# Ascii_of_Main_Board_V1_1.net
KiCad netlist of a schematic drawn in Altium Designer
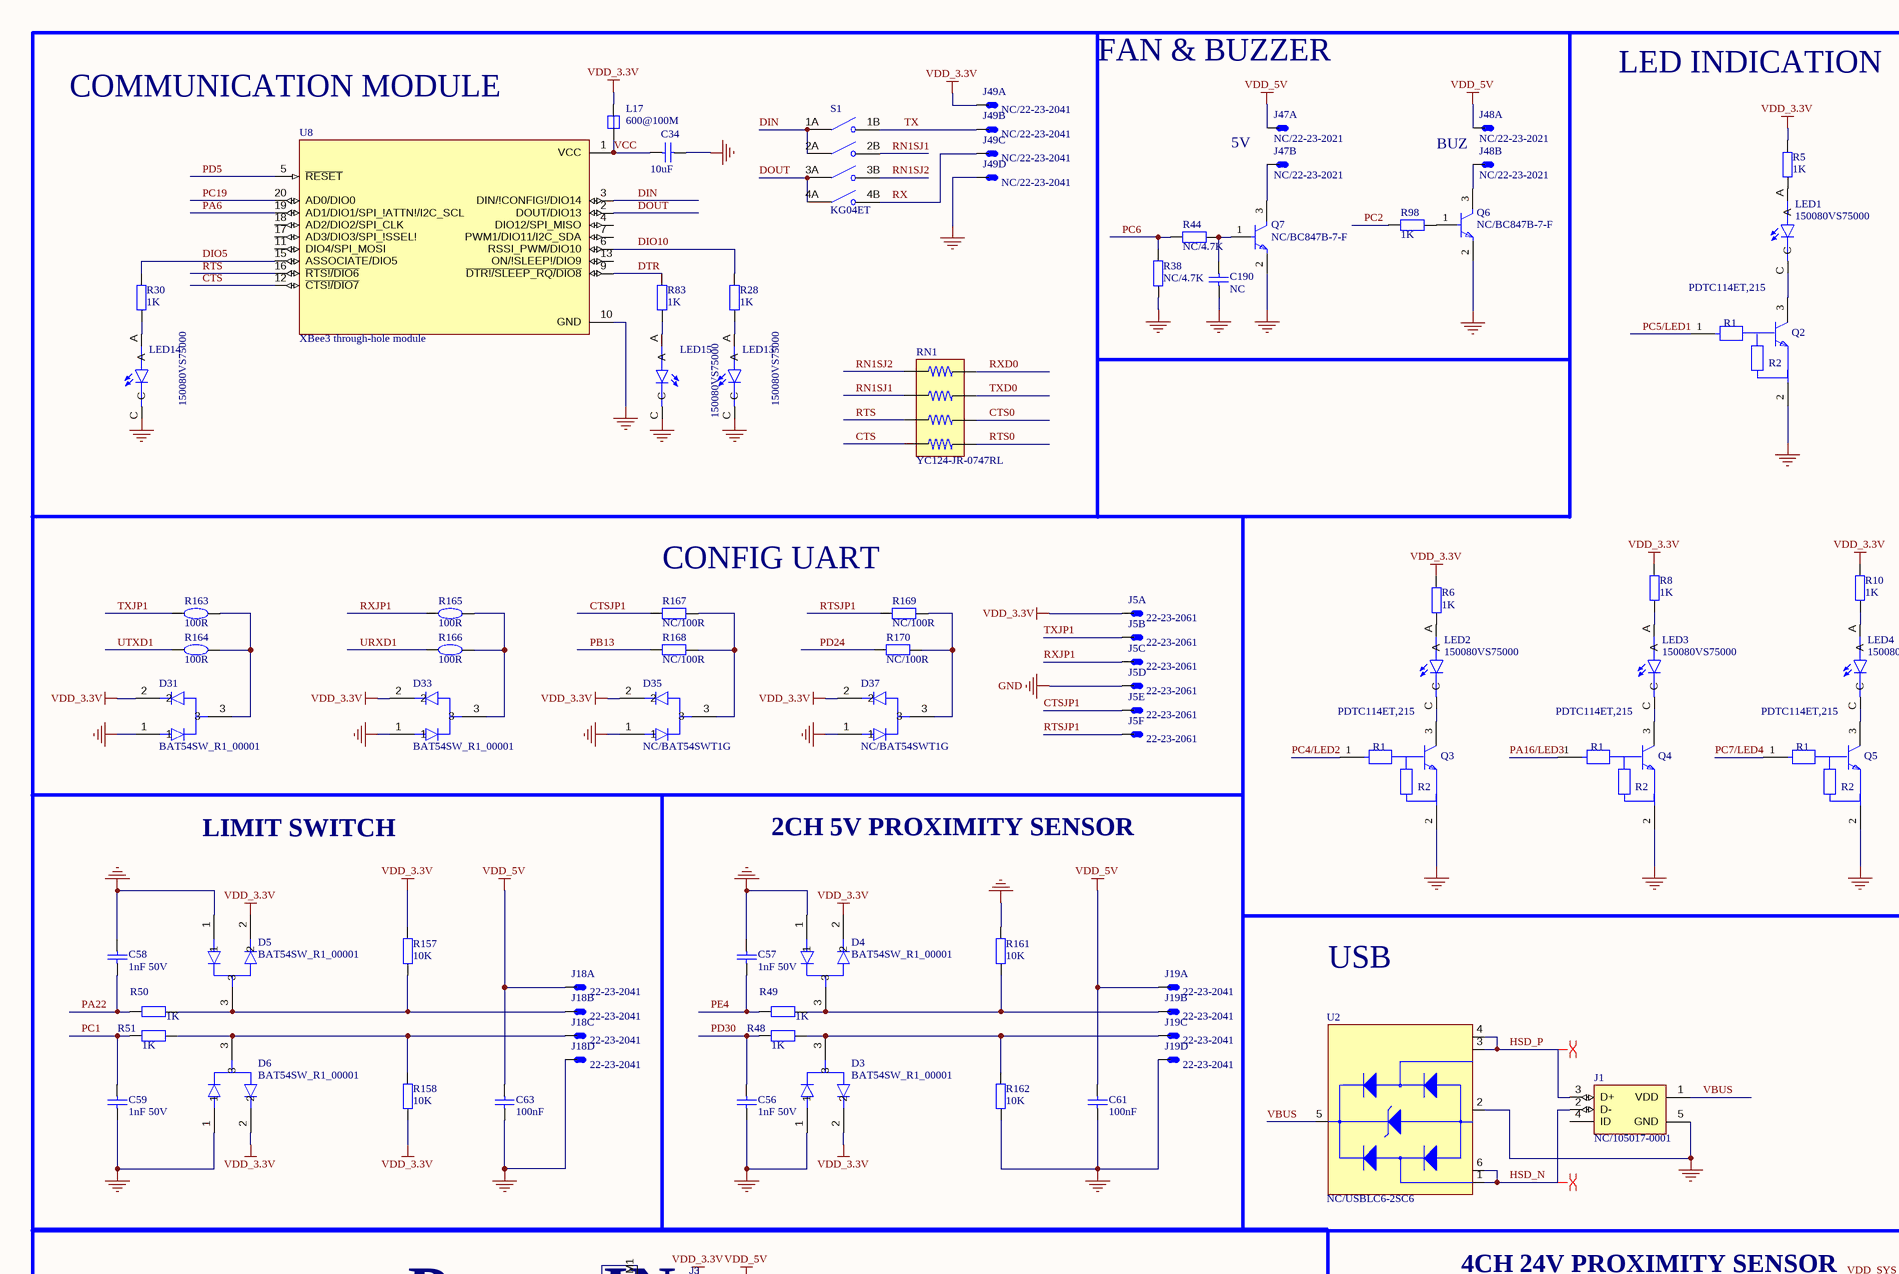
[diagram p0: Ascii of Main Board V1.1.SchDoc, top left]
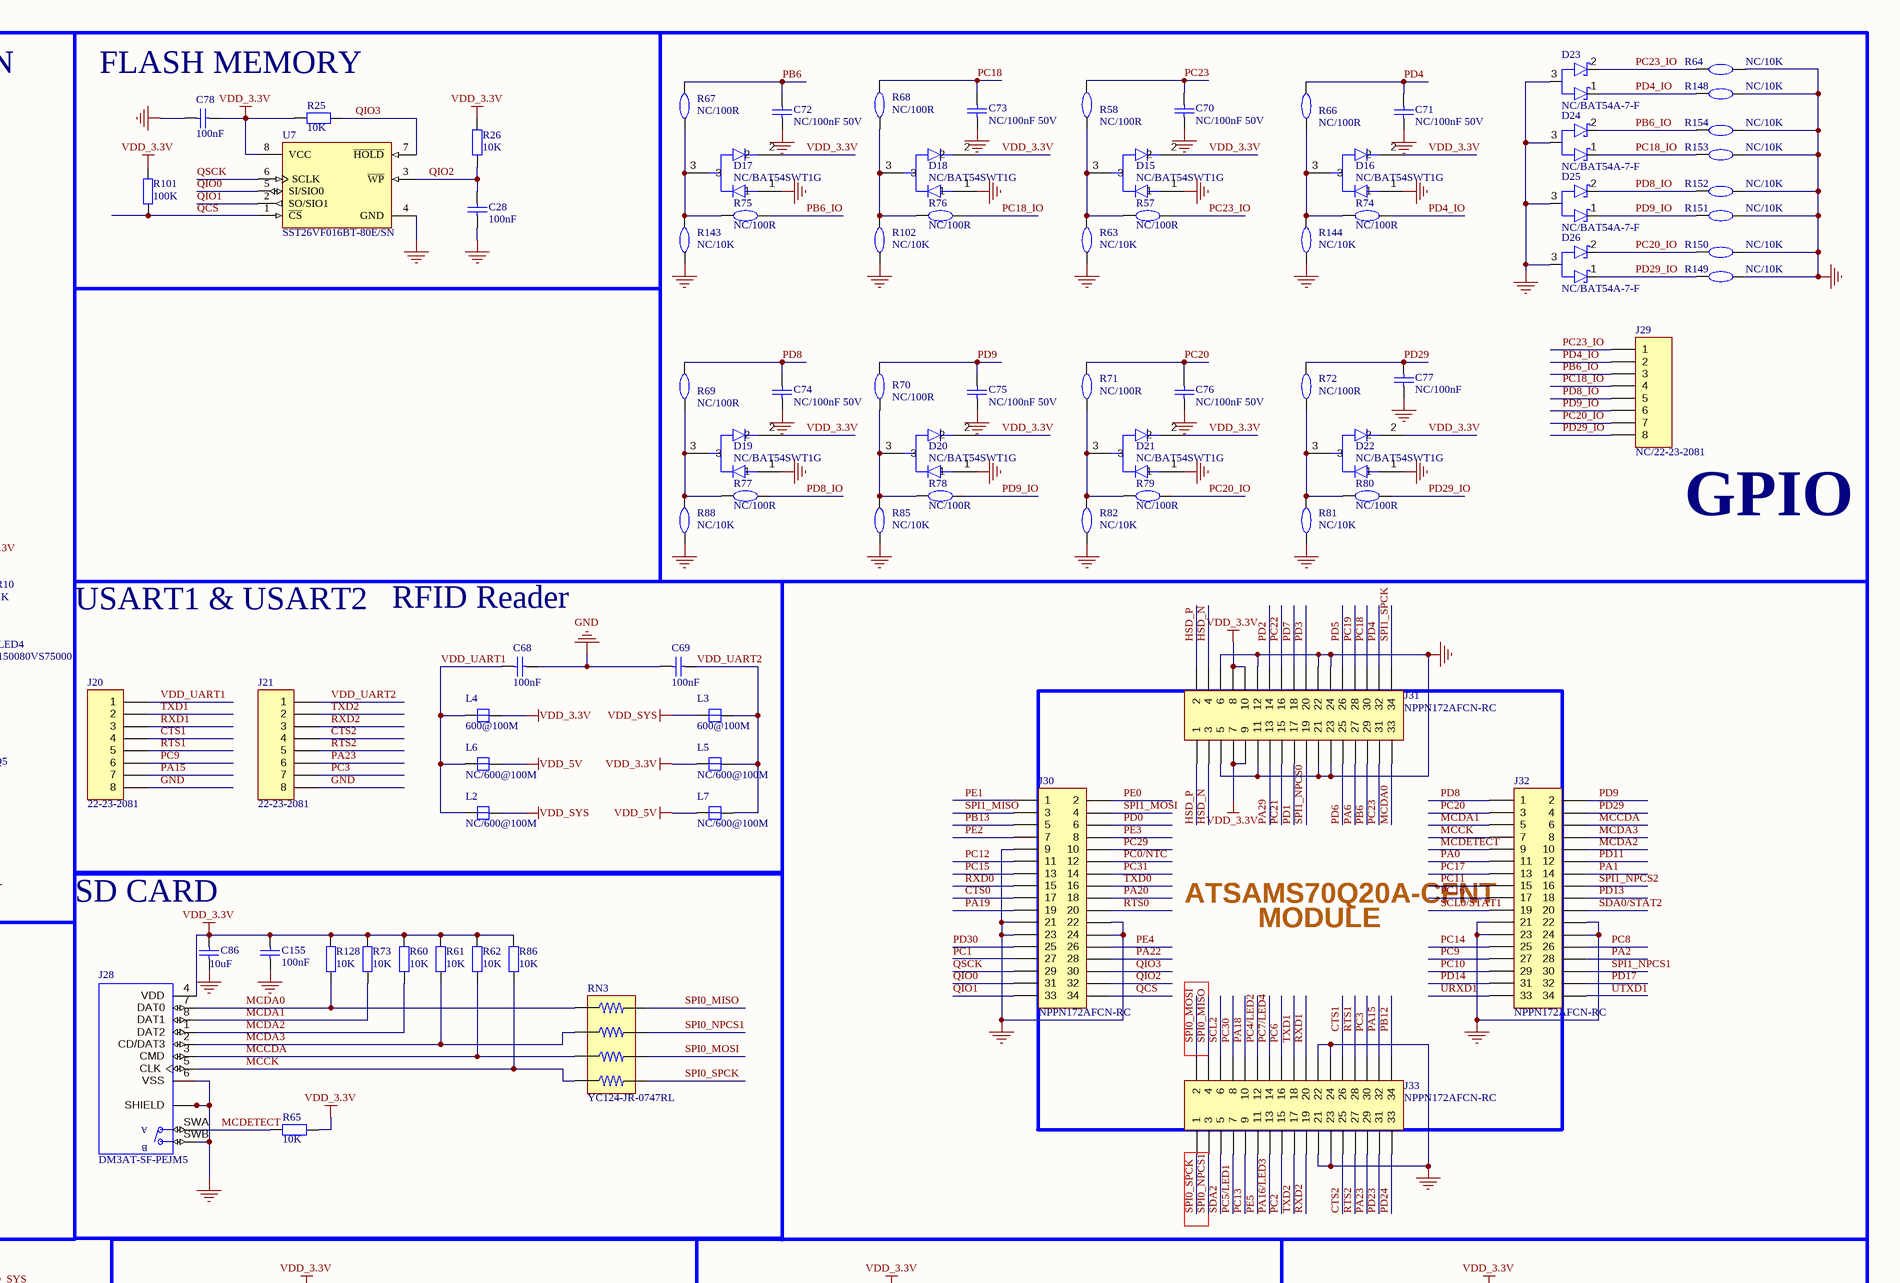
[diagram p1: Ascii of Main Board V1.1.SchDoc, top right]
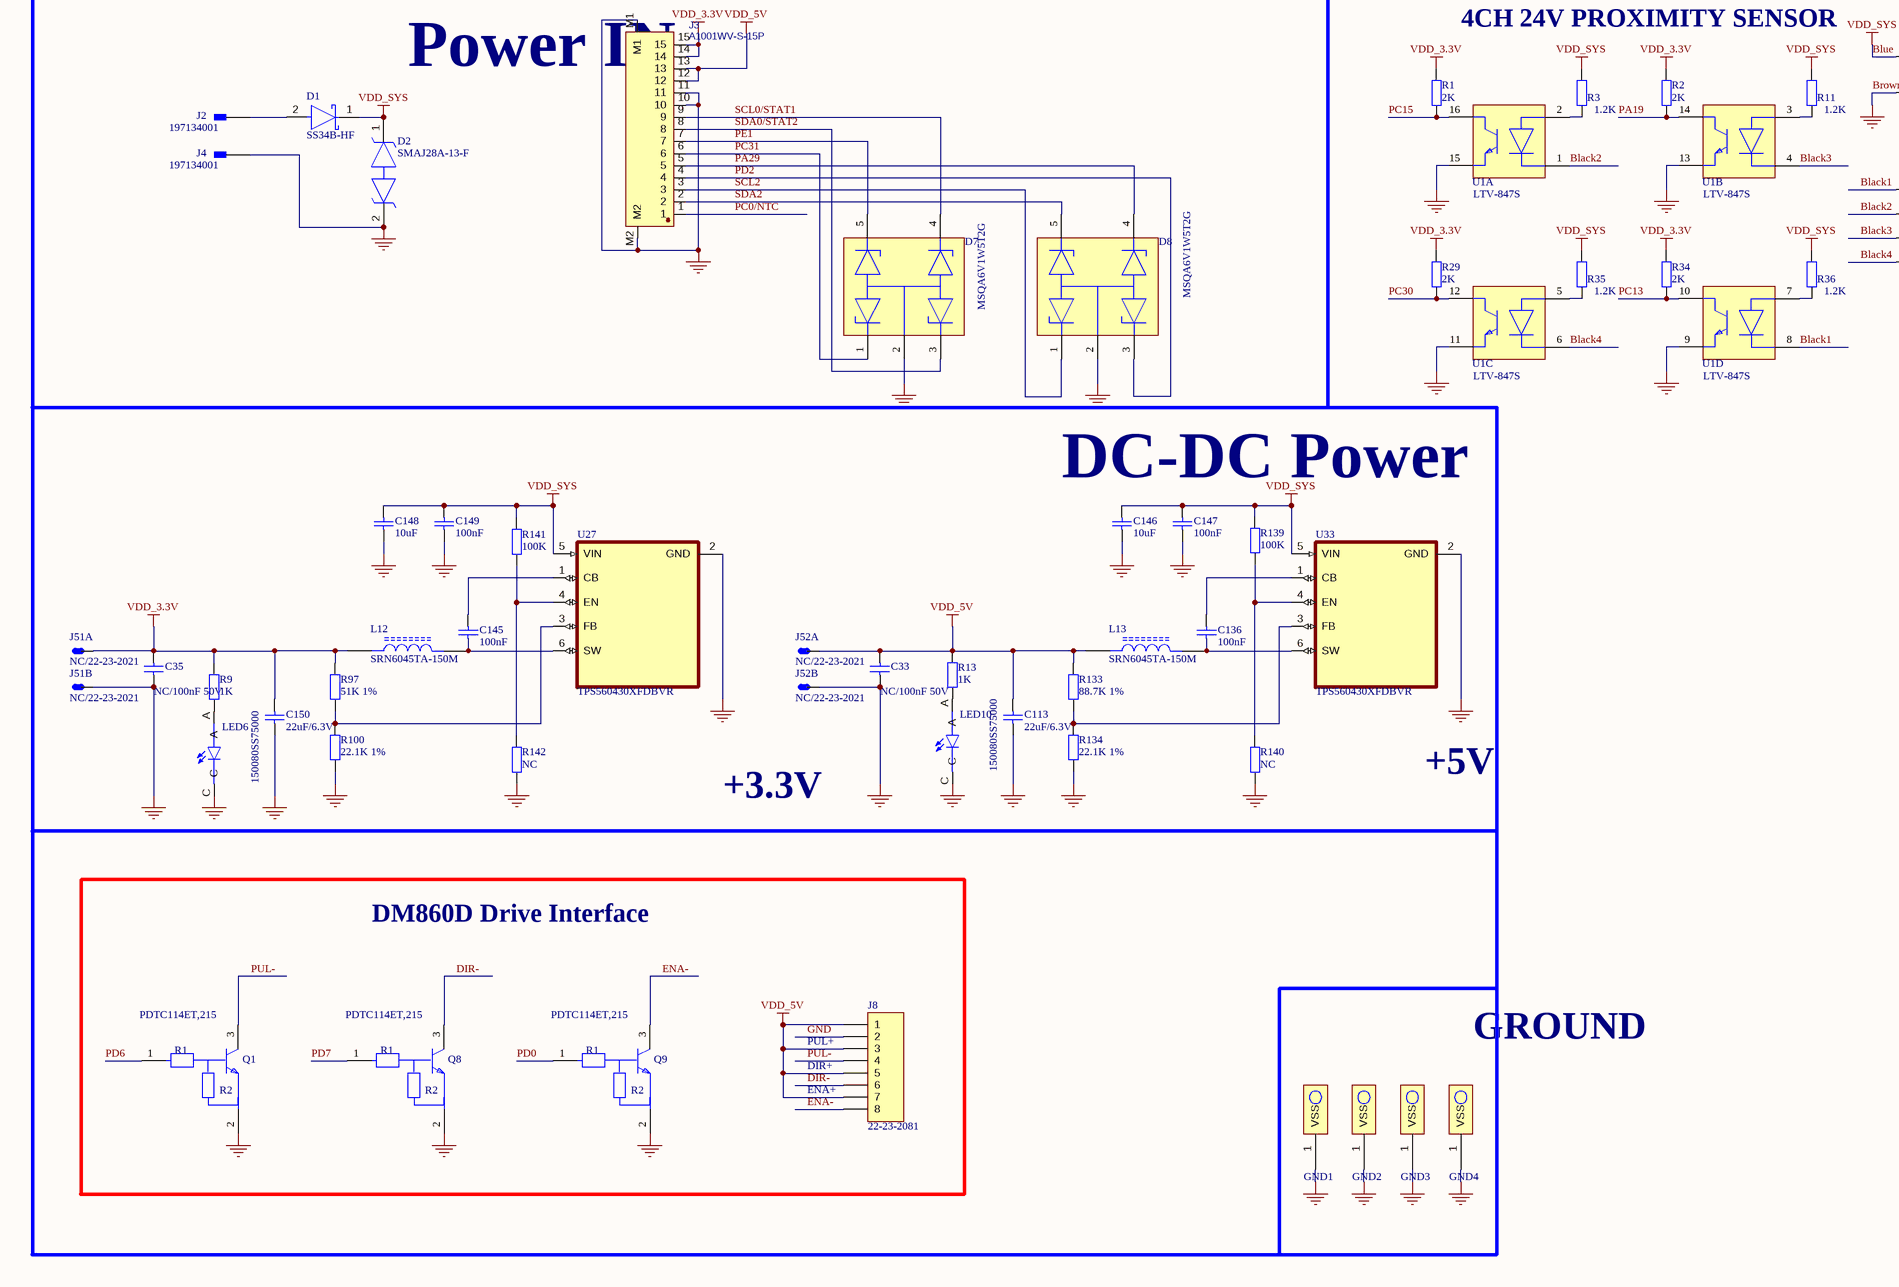
[diagram p2: Ascii of Main Board V1.1.SchDoc, bottom left]
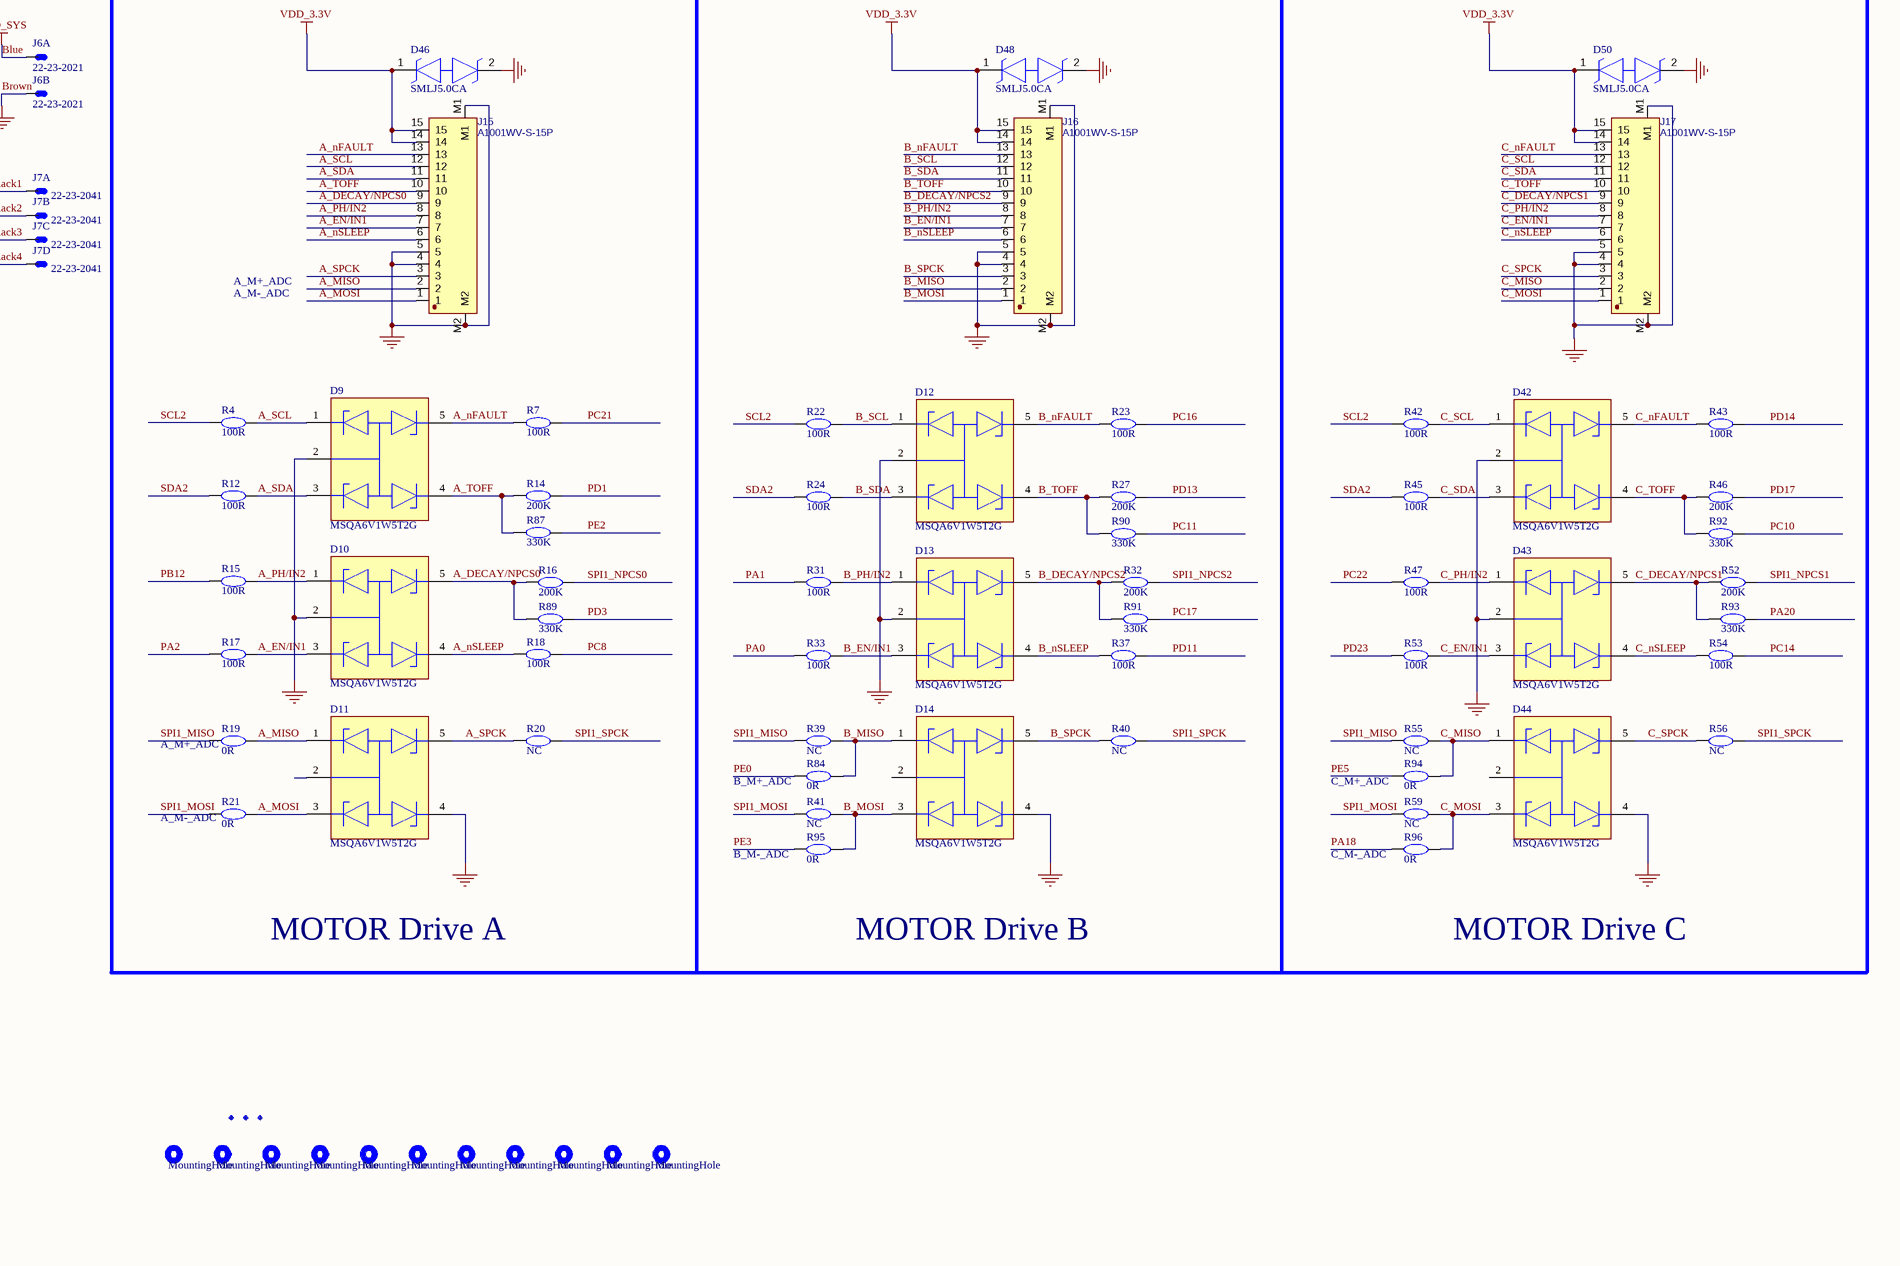
[diagram p3: Ascii of Main Board V1.1.SchDoc, bottom right]

(export (version "E")
  (design (tool "Eeschema 10.0.6"))
  (components
    (comp (ref "C28")
      (value "100nF")
      (footprint "C_0603_1608Metric")
      (description "CAP CER 0.1UF 50V X7R 0603")
      (fields (field (name "PUBLISHER") "Altium Limited"))
      (libsource (lib "Miscellaneous Devices") (part "Cap Semi"))
    )
    (comp (ref "C33")
      (value "NC/100nF 50V")
      (footprint "C_0603_1608Metric")
      (description "08055C103KAT2A")
      (fields (field (name "PUBLISHER") "Altium Limited"))
      (libsource (lib "Miscellaneous Devices") (part "Cap Semi"))
    )
    (comp (ref "C34")
      (value "10uF")
      (footprint "C_1206_3216Metric")
      (description "CAP CER 10UF 50V X5R 1206")
      (fields (field (name "PUBLISHER") "Altium Limited"))
      (libsource (lib "Miscellaneous Devices") (part "Cap Semi"))
    )
    (comp (ref "C35")
      (value "NC/100nF 50V")
      (footprint "C_0603_1608Metric")
      (description "08055C103KAT2A")
      (fields (field (name "PUBLISHER") "Altium Limited"))
      (libsource (lib "Miscellaneous Devices") (part "Cap Semi"))
    )
    (comp (ref "C56")
      (value "1nF 50V")
      (footprint "C_0603_1608Metric")
      (description "CAP CER 1000PF 50V X7R 0603")
      (fields (field (name "PUBLISHER") "Altium Limited"))
      (libsource (lib "Miscellaneous Devices") (part "Cap Semi"))
    )
    (comp (ref "C57")
      (value "1nF 50V")
      (footprint "C_0603_1608Metric")
      (description "CAP CER 1000PF 50V X7R 0603")
      (fields (field (name "PUBLISHER") "Altium Limited"))
      (libsource (lib "Miscellaneous Devices") (part "Cap Semi"))
    )
    (comp (ref "C58")
      (value "1nF 50V")
      (footprint "C_0603_1608Metric")
      (description "CAP CER 1000PF 50V X7R 0603")
      (fields (field (name "PUBLISHER") "Altium Limited"))
      (libsource (lib "Miscellaneous Devices") (part "Cap Semi"))
    )
    (comp (ref "C59")
      (value "1nF 50V")
      (footprint "C_0603_1608Metric")
      (description "CAP CER 1000PF 50V X7R 0603")
      (fields (field (name "PUBLISHER") "Altium Limited"))
      (libsource (lib "Miscellaneous Devices") (part "Cap Semi"))
    )
    (comp (ref "C61")
      (value "100nF")
      (footprint "C_0603_1608Metric")
      (description "CAP CER 0.1UF 50V X7R 0603")
      (fields (field (name "PUBLISHER") "Altium Limited"))
      (libsource (lib "Miscellaneous Devices") (part "Cap Semi"))
    )
    (comp (ref "C63")
      (value "100nF")
      (footprint "C_0603_1608Metric")
      (description "CAP CER 0.1UF 50V X7R 0603")
      (fields (field (name "PUBLISHER") "Altium Limited"))
      (libsource (lib "Miscellaneous Devices") (part "Cap Semi"))
    )
    (comp (ref "C68")
      (value "100nF")
      (footprint "C_0603_1608Metric")
      (description "CAP CER 0.1UF 50V X7R 0603")
      (fields (field (name "PUBLISHER") "Altium Limited"))
      (libsource (lib "Miscellaneous Devices") (part "Cap Semi"))
    )
    (comp (ref "C69")
      (value "100nF")
      (footprint "C_0603_1608Metric")
      (description "CAP CER 0.1UF 50V X7R 0603")
      (fields (field (name "PUBLISHER") "Altium Limited"))
      (libsource (lib "Miscellaneous Devices") (part "Cap Semi"))
    )
    (comp (ref "C70")
      (value "NC/100nF 50V")
      (footprint "C_0603_1608Metric")
      (description "0805J0500104KXT")
      (fields (field (name "PUBLISHER") "Altium Limited"))
      (libsource (lib "Miscellaneous Devices") (part "Cap Semi"))
    )
    (comp (ref "C71")
      (value "NC/100nF 50V")
      (footprint "C_0603_1608Metric")
      (description "0805J0500104KXT")
      (fields (field (name "PUBLISHER") "Altium Limited"))
      (libsource (lib "Miscellaneous Devices") (part "Cap Semi"))
    )
    (comp (ref "C72")
      (value "NC/100nF 50V")
      (footprint "C_0603_1608Metric")
      (description "0805J0500104KXT")
      (fields (field (name "PUBLISHER") "Altium Limited"))
      (libsource (lib "Miscellaneous Devices") (part "Cap Semi"))
    )
    (comp (ref "C73")
      (value "NC/100nF 50V")
      (footprint "C_0603_1608Metric")
      (description "0805J0500104KXT")
      (fields (field (name "PUBLISHER") "Altium Limited"))
      (libsource (lib "Miscellaneous Devices") (part "Cap Semi"))
    )
    (comp (ref "C74")
      (value "NC/100nF 50V")
      (footprint "C_0603_1608Metric")
      (description "0805J0500104KXT")
      (fields (field (name "PUBLISHER") "Altium Limited"))
      (libsource (lib "Miscellaneous Devices") (part "Cap Semi"))
    )
    (comp (ref "C75")
      (value "NC/100nF 50V")
      (footprint "C_0603_1608Metric")
      (description "0805J0500104KXT")
      (fields (field (name "PUBLISHER") "Altium Limited"))
      (libsource (lib "Miscellaneous Devices") (part "Cap Semi"))
    )
    (comp (ref "C76")
      (value "NC/100nF 50V")
      (footprint "C_0603_1608Metric")
      (description "0805J0500104KXT")
      (fields (field (name "PUBLISHER") "Altium Limited"))
      (libsource (lib "Miscellaneous Devices") (part "Cap Semi"))
    )
    (comp (ref "C77")
      (value "NC/100nF")
      (footprint "C_0603_1608Metric")
      (description "0805J0500104KXT")
      (fields (field (name "PUBLISHER") "Altium Limited"))
      (libsource (lib "Miscellaneous Devices") (part "Cap Semi"))
    )
    (comp (ref "C78")
      (value "100nF")
      (footprint "C_0603_1608Metric")
      (description "CAP CER 0.1UF 50V X7R 0603")
      (fields (field (name "PUBLISHER") "Altium Limited"))
      (libsource (lib "Miscellaneous Devices") (part "Cap Semi"))
    )
    (comp (ref "C86")
      (value "10uF")
      (footprint "C_1206_3216Metric")
      (description "CAP CER 10UF 50V X5R 1206")
      (fields (field (name "PUBLISHER") "Altium Limited"))
      (libsource (lib "Miscellaneous Devices") (part "Cap Semi"))
    )
    (comp (ref "C113")
      (value "22uF/6.3V")
      (footprint "C_0805_2012Metric")
      (description "CAP CER 22UF 16V X5R 0805")
      (fields (field (name "PUBLISHER") "Altium Limited"))
      (libsource (lib "Miscellaneous Devices") (part "Cap Semi"))
    )
    (comp (ref "C136")
      (value "100nF")
      (footprint "C_0603_1608Metric")
      (description "CAP CER 0.1UF 50V X7R 0603")
      (fields (field (name "PUBLISHER") "Altium Limited"))
      (libsource (lib "Miscellaneous Devices") (part "Cap Semi"))
    )
    (comp (ref "C145")
      (value "100nF")
      (footprint "C_0603_1608Metric")
      (description "CAP CER 0.1UF 50V X7R 0603")
      (fields (field (name "PUBLISHER") "Altium Limited"))
      (libsource (lib "Miscellaneous Devices") (part "Cap Semi"))
    )
    (comp (ref "C146")
      (value "10uF")
      (footprint "C_1206_3216Metric")
      (description "CAP CER 10UF 50V X5R 1206")
      (fields (field (name "PUBLISHER") "Altium Limited"))
      (libsource (lib "Miscellaneous Devices") (part "Cap Semi"))
    )
    (comp (ref "C147")
      (value "100nF")
      (footprint "C_0603_1608Metric")
      (description "CAP CER 0.1UF 50V X7R 0603")
      (fields (field (name "PUBLISHER") "Altium Limited"))
      (libsource (lib "Miscellaneous Devices") (part "Cap Semi"))
    )
    (comp (ref "C148")
      (value "10uF")
      (footprint "C_1206_3216Metric")
      (description "CAP CER 10UF 50V X5R 1206")
      (fields (field (name "PUBLISHER") "Altium Limited"))
      (libsource (lib "Miscellaneous Devices") (part "Cap Semi"))
    )
    (comp (ref "C149")
      (value "100nF")
      (footprint "C_0603_1608Metric")
      (description "CAP CER 0.1UF 50V X7R 0603")
      (fields (field (name "PUBLISHER") "Altium Limited"))
      (libsource (lib "Miscellaneous Devices") (part "Cap Semi"))
    )
    (comp (ref "C150")
      (value "22uF/6.3V")
      (footprint "C_0805_2012Metric")
      (description "CAP CER 22UF 16V X5R 0805")
      (fields (field (name "PUBLISHER") "Altium Limited"))
      (libsource (lib "Miscellaneous Devices") (part "Cap Semi"))
    )
    (comp (ref "C155")
      (value "100nF")
      (footprint "C_0603_1608Metric")
      (description "CAP CER 0.1UF 50V X7R 0603")
      (fields (field (name "PUBLISHER") "Altium Limited"))
      (libsource (lib "Miscellaneous Devices") (part "Cap Semi"))
    )
    (comp (ref "C190")
      (value "NC")
      (footprint "C_0603_1608Metric")
      (description "DUMMY")
      (fields (field (name "PUBLISHER") "Altium Limited"))
      (libsource (lib "Miscellaneous Devices") (part "Cap Semi"))
    )
    (comp (ref "D1")
      (value "SS34B-HF")
      (footprint "FP-95402-MFG")
      (description "DIODE SCHOTTKY 40V 3A DO214AB")
      (libsource (lib "Altium lib") (part "1d6ec82d83fb6aee721767c19dac4b9"))
    )
    (comp (ref "D2")
      (value "SMAJ28A-13-F")
      (footprint "DIONM7959X262N")
      (description "TVS Diode (Bi-directional)")
      (fields
        (field (name "MANUFACTURER_PART_NUMBER") "SMLJ43CA")
        (field (name "MOUSER PART NUMBER") "652-SMLJ43CA")
      )
      (libsource (lib "SamacSys") (part "SMLJ43CA"))
    )
    (comp (ref "D3")
      (value "BAT54SW_R1_00001")
      (footprint "ONSC-SOT-323-3-419-04_V")
      (description "Diode Array 1 Pair Series Connection Schottky 30V 200mA Surface Mount TO-236-3, SC-59, SOT-23-3")
      (fields (field (name "MF") "ON Semiconductor") (field (name "MP") "BAT54S"))
      (libsource (lib "SamacSys") (part "BAT54S"))
    )
    (comp (ref "D4")
      (value "BAT54SW_R1_00001")
      (footprint "ONSC-SOT-323-3-419-04_V")
      (description "Diode Array 1 Pair Series Connection Schottky 30V 200mA Surface Mount TO-236-3, SC-59, SOT-23-3")
      (fields (field (name "MF") "ON Semiconductor") (field (name "MP") "BAT54S"))
      (libsource (lib "SamacSys") (part "BAT54S"))
    )
    (comp (ref "D5")
      (value "BAT54SW_R1_00001")
      (footprint "ONSC-SOT-323-3-419-04_V")
      (description "Diode Array 1 Pair Series Connection Schottky 30V 200mA Surface Mount TO-236-3, SC-59, SOT-23-3")
      (fields (field (name "MF") "ON Semiconductor") (field (name "MP") "BAT54S"))
      (libsource (lib "SamacSys") (part "BAT54S"))
    )
    (comp (ref "D6")
      (value "BAT54SW_R1_00001")
      (footprint "ONSC-SOT-323-3-419-04_V")
      (description "Diode Array 1 Pair Series Connection Schottky 30V 200mA Surface Mount TO-236-3, SC-59, SOT-23-3")
      (fields (field (name "MF") "ON Semiconductor") (field (name "MP") "BAT54S"))
      (libsource (lib "SamacSys") (part "BAT54S"))
    )
    (comp (ref "D7")
      (value "MSQA6V1W5T2G")
      (footprint "SOT95P280X145-5N")
      (description "Low capacitance unidirectional quadruple ESD protection diode arrays")
      (libsource (lib "") (part "PESD3V3L4UW_1"))
    )
    (comp (ref "D8")
      (value "MSQA6V1W5T2G")
      (footprint "SOT95P280X145-5N")
      (description "Low capacitance unidirectional quadruple ESD protection diode arrays")
      (libsource (lib "") (part "PESD3V3L4UW_1"))
    )
    (comp (ref "D9")
      (value "MSQA6V1W5T2G")
      (footprint "SOT95P280X145-5N")
      (description "Low capacitance unidirectional quadruple ESD protection diode arrays")
      (libsource (lib "SamacSys") (part "PESD3V3L4UW"))
    )
    (comp (ref "D10")
      (value "MSQA6V1W5T2G")
      (footprint "SOT95P280X145-5N")
      (description "Low capacitance unidirectional quadruple ESD protection diode arrays")
      (libsource (lib "SamacSys") (part "PESD3V3L4UW"))
    )
    (comp (ref "D11")
      (value "MSQA6V1W5T2G")
      (footprint "SOT95P280X145-5N")
      (description "Low capacitance unidirectional quadruple ESD protection diode arrays")
      (libsource (lib "SamacSys") (part "PESD3V3L4UW"))
    )
    (comp (ref "D12")
      (value "MSQA6V1W5T2G")
      (footprint "SOT95P280X145-5N")
      (description "Low capacitance unidirectional quadruple ESD protection diode arrays")
      (libsource (lib "SamacSys") (part "PESD3V3L4UW"))
    )
    (comp (ref "D13")
      (value "MSQA6V1W5T2G")
      (footprint "SOT95P280X145-5N")
      (description "Low capacitance unidirectional quadruple ESD protection diode arrays")
      (libsource (lib "SamacSys") (part "PESD3V3L4UW"))
    )
    (comp (ref "D14")
      (value "MSQA6V1W5T2G")
      (footprint "SOT95P280X145-5N")
      (description "Low capacitance unidirectional quadruple ESD protection diode arrays")
      (libsource (lib "SamacSys") (part "PESD3V3L4UW"))
    )
    (comp (ref "D15")
      (value "NC/BAT54SWT1G")
      (footprint "ONSC-SOT-323-3-419-04_V")
      (description "Diode Array 1 Pair Series Connection Schottky 30V 200mA Surface Mount TO-236-3, SC-59, SOT-23-3")
      (fields (field (name "MF") "ON Semiconductor") (field (name "MP") "BAT54S"))
      (libsource (lib "BAT54S") (part "BAT54S"))
    )
    (comp (ref "D16")
      (value "NC/BAT54SWT1G")
      (footprint "ONSC-SOT-323-3-419-04_V")
      (description "Diode Array 1 Pair Series Connection Schottky 30V 200mA Surface Mount TO-236-3, SC-59, SOT-23-3")
      (fields (field (name "MF") "ON Semiconductor") (field (name "MP") "BAT54S"))
      (libsource (lib "BAT54S") (part "BAT54S"))
    )
    (comp (ref "D17")
      (value "NC/BAT54SWT1G")
      (footprint "ONSC-SOT-323-3-419-04_V")
      (description "Diode Array 1 Pair Series Connection Schottky 30V 200mA Surface Mount TO-236-3, SC-59, SOT-23-3")
      (fields (field (name "MF") "ON Semiconductor") (field (name "MP") "BAT54S"))
      (libsource (lib "BAT54S") (part "BAT54S"))
    )
    (comp (ref "D18")
      (value "NC/BAT54SWT1G")
      (footprint "ONSC-SOT-323-3-419-04_V")
      (description "Diode Array 1 Pair Series Connection Schottky 30V 200mA Surface Mount TO-236-3, SC-59, SOT-23-3")
      (fields (field (name "MF") "ON Semiconductor") (field (name "MP") "BAT54S"))
      (libsource (lib "BAT54S") (part "BAT54S"))
    )
    (comp (ref "D19")
      (value "NC/BAT54SWT1G")
      (footprint "ONSC-SOT-323-3-419-04_V")
      (description "Diode Array 1 Pair Series Connection Schottky 30V 200mA Surface Mount TO-236-3, SC-59, SOT-23-3")
      (fields (field (name "MF") "ON Semiconductor") (field (name "MP") "BAT54S"))
      (libsource (lib "BAT54S") (part "BAT54S"))
    )
    (comp (ref "D20")
      (value "NC/BAT54SWT1G")
      (footprint "ONSC-SOT-323-3-419-04_V")
      (description "Diode Array 1 Pair Series Connection Schottky 30V 200mA Surface Mount TO-236-3, SC-59, SOT-23-3")
      (fields (field (name "MF") "ON Semiconductor") (field (name "MP") "BAT54S"))
      (libsource (lib "BAT54S") (part "BAT54S"))
    )
    (comp (ref "D21")
      (value "NC/BAT54SWT1G")
      (footprint "ONSC-SOT-323-3-419-04_V")
      (description "Diode Array 1 Pair Series Connection Schottky 30V 200mA Surface Mount TO-236-3, SC-59, SOT-23-3")
      (fields (field (name "MF") "ON Semiconductor") (field (name "MP") "BAT54S"))
      (libsource (lib "BAT54S") (part "BAT54S"))
    )
    (comp (ref "D22")
      (value "NC/BAT54SWT1G")
      (footprint "ONSC-SOT-323-3-419-04_V")
      (description "Diode Array 1 Pair Series Connection Schottky 30V 200mA Surface Mount TO-236-3, SC-59, SOT-23-3")
      (fields (field (name "MF") "ON Semiconductor") (field (name "MP") "BAT54S"))
      (libsource (lib "BAT54S") (part "BAT54S"))
    )
    (comp (ref "D23")
      (value "NC/BAT54A-7-F")
      (footprint "ONSC-SOT-323-3-419-04_V")
      (description "Diode Array 1 Pair Common Anode Schottky 30V 200mA (DC) Surface Mount TO-236-3, SC-59, SOT-23-3")
      (fields (field (name "MP") "BAT54A-7-F") (field (name "MF") "Diodes Inc."))
      (libsource (lib "SamacSys") (part "BAT54A-7-F"))
    )
    (comp (ref "D24")
      (value "NC/BAT54A-7-F")
      (footprint "ONSC-SOT-323-3-419-04_V")
      (description "Diode Array 1 Pair Common Anode Schottky 30V 200mA (DC) Surface Mount TO-236-3, SC-59, SOT-23-3")
      (fields (field (name "MP") "BAT54A-7-F") (field (name "MF") "Diodes Inc."))
      (libsource (lib "SamacSys") (part "BAT54A-7-F"))
    )
    (comp (ref "D25")
      (value "NC/BAT54A-7-F")
      (footprint "ONSC-SOT-323-3-419-04_V")
      (description "Diode Array 1 Pair Common Anode Schottky 30V 200mA (DC) Surface Mount TO-236-3, SC-59, SOT-23-3")
      (fields (field (name "MP") "BAT54A-7-F") (field (name "MF") "Diodes Inc."))
      (libsource (lib "SamacSys") (part "BAT54A-7-F"))
    )
    (comp (ref "D26")
      (value "NC/BAT54A-7-F")
      (footprint "ONSC-SOT-323-3-419-04_V")
      (description "Diode Array 1 Pair Common Anode Schottky 30V 200mA (DC) Surface Mount TO-236-3, SC-59, SOT-23-3")
      (fields (field (name "MP") "BAT54A-7-F") (field (name "MF") "Diodes Inc."))
      (libsource (lib "SamacSys") (part "BAT54A-7-F"))
    )
    (comp (ref "D31")
      (value "BAT54SW_R1_00001")
      (footprint "ONSC-SOT-323-3-419-04_V")
      (description "Diode Array 1 Pair Series Connection Schottky 30V 200mA Surface Mount TO-236-3, SC-59, SOT-23-3")
      (fields (field (name "MF") "ON Semiconductor") (field (name "MP") "BAT54S"))
      (libsource (lib "SamacSys") (part "BAT54S"))
    )
    (comp (ref "D33")
      (value "BAT54SW_R1_00001")
      (footprint "ONSC-SOT-323-3-419-04_V")
      (description "Diode Array 1 Pair Series Connection Schottky 30V 200mA Surface Mount TO-236-3, SC-59, SOT-23-3")
      (fields (field (name "MF") "ON Semiconductor") (field (name "MP") "BAT54S"))
      (libsource (lib "SamacSys") (part "BAT54S"))
    )
    (comp (ref "D35")
      (value "NC/BAT54SWT1G")
      (footprint "ONSC-SOT-323-3-419-04_V")
      (fields
        (field (name "DIGI-KEY_PART_NUMBER") "BAT54SCT-ND")
        (field (name "MP") "BAT54STA")
        (field (name "MF") "Diodes Inc.")
      )
      (libsource (lib "Zigbee Sch Lib_SJCH") (part "BAT54STA"))
    )
    (comp (ref "D37")
      (value "NC/BAT54SWT1G")
      (footprint "ONSC-SOT-323-3-419-04_V")
      (fields
        (field (name "DIGI-KEY_PART_NUMBER") "BAT54SCT-ND")
        (field (name "MP") "BAT54STA")
        (field (name "MF") "Diodes Inc.")
      )
      (libsource (lib "Zigbee Sch Lib_SJCH") (part "BAT54STA"))
    )
    (comp (ref "D42")
      (value "MSQA6V1W5T2G")
      (footprint "SOT95P280X145-5N")
      (description "Low capacitance unidirectional quadruple ESD protection diode arrays")
      (libsource (lib "SamacSys") (part "PESD3V3L4UW"))
    )
    (comp (ref "D43")
      (value "MSQA6V1W5T2G")
      (footprint "SOT95P280X145-5N")
      (description "Low capacitance unidirectional quadruple ESD protection diode arrays")
      (libsource (lib "SamacSys") (part "PESD3V3L4UW"))
    )
    (comp (ref "D44")
      (value "MSQA6V1W5T2G")
      (footprint "SOT95P280X145-5N")
      (description "Low capacitance unidirectional quadruple ESD protection diode arrays")
      (libsource (lib "SamacSys") (part "PESD3V3L4UW"))
    )
    (comp (ref "D46")
      (value "SMLJ5.0CA")
      (footprint "DIONM7959X262N")
      (description "TVS Diode (Bi-directional)")
      (fields
        (field (name "MANUFACTURER_PART_NUMBER") "SMLJ43CA")
        (field (name "MOUSER PART NUMBER") "652-SMLJ43CA")
      )
      (libsource (lib "SamacSys") (part "SMLJ43CA"))
    )
    (comp (ref "D48")
      (value "SMLJ5.0CA")
      (footprint "DIONM7959X262N")
      (description "TVS Diode (Bi-directional)")
      (fields
        (field (name "MANUFACTURER_PART_NUMBER") "SMLJ43CA")
        (field (name "MOUSER PART NUMBER") "652-SMLJ43CA")
      )
      (libsource (lib "SamacSys") (part "SMLJ43CA"))
    )
    (comp (ref "D50")
      (value "SMLJ5.0CA")
      (footprint "DIONM7959X262N")
      (description "TVS Diode (Bi-directional)")
      (fields
        (field (name "MANUFACTURER_PART_NUMBER") "SMLJ43CA")
        (field (name "MOUSER PART NUMBER") "652-SMLJ43CA")
      )
      (libsource (lib "SamacSys") (part "SMLJ43CA"))
    )
    (comp (ref "Fid1")
      (value "Fiducial mark")
      (footprint "Fiducial_1mm_Mask2mm")
      (description "Fiducial Mark")
      (fields (field (name "PART NUMBER") "Fid-Mark") (field (name "PUBLISHER") "Nordic Semiconductor"))
      (libsource (lib "Altium lib") (part "Fiducial"))
    )
    (comp (ref "Fid2")
      (value "Fiducial mark")
      (footprint "Fiducial_1mm_Mask2mm")
      (description "Fiducial Mark")
      (fields (field (name "PART NUMBER") "Fid-Mark") (field (name "PUBLISHER") "Nordic Semiconductor"))
      (libsource (lib "Altium lib") (part "Fiducial"))
    )
    (comp (ref "Fid3")
      (value "Fiducial mark")
      (footprint "Fiducial_1mm_Mask2mm")
      (description "Fiducial Mark")
      (fields (field (name "PART NUMBER") "Fid-Mark") (field (name "PUBLISHER") "Nordic Semiconductor"))
      (libsource (lib "Altium lib") (part "Fiducial"))
    )
    (comp (ref "GND1")
      (value "Ground Mark")
      (footprint "1X01")
      (libsource (lib "Zigbee Sch Lib_SJCH") (part "Ground Mark"))
    )
    (comp (ref "GND2")
      (value "Ground Mark")
      (footprint "1X01")
      (libsource (lib "Zigbee Sch Lib_SJCH") (part "Ground Mark"))
    )
    (comp (ref "GND3")
      (value "Ground Mark")
      (footprint "1X01")
      (libsource (lib "Zigbee Sch Lib_SJCH") (part "Ground Mark"))
    )
    (comp (ref "GND4")
      (value "Ground Mark")
      (footprint "1X01")
      (libsource (lib "Zigbee Sch Lib_SJCH") (part "Ground Mark"))
    )
    (comp (ref "H1")
      (value "MountingHole")
      (footprint "3,0-PAD")
      (libsource (lib "SamacSys") (part "MountingHole"))
    )
    (comp (ref "H2")
      (value "MountingHole")
      (footprint "3,0-PAD")
      (libsource (lib "SamacSys") (part "MountingHole"))
    )
    (comp (ref "H3")
      (value "MountingHole")
      (footprint "3,0-PAD")
      (libsource (lib "SamacSys") (part "MountingHole"))
    )
    (comp (ref "H4")
      (value "MountingHole")
      (footprint "3,0-PAD")
      (libsource (lib "SamacSys") (part "MountingHole"))
    )
    (comp (ref "H5")
      (value "MountingHole")
      (footprint "3,0-PAD")
      (libsource (lib "SamacSys") (part "MountingHole"))
    )
    (comp (ref "H6")
      (value "MountingHole")
      (footprint "3,0-PAD")
      (libsource (lib "SamacSys") (part "MountingHole"))
    )
    (comp (ref "H7")
      (value "MountingHole")
      (footprint "3,0-PAD")
      (libsource (lib "SamacSys") (part "MountingHole"))
    )
    (comp (ref "H8")
      (value "MountingHole")
      (footprint "3,0-PAD")
      (libsource (lib "SamacSys") (part "MountingHole"))
    )
    (comp (ref "H9")
      (value "MountingHole")
      (footprint "3,0-PAD")
      (libsource (lib "SamacSys") (part "MountingHole"))
    )
    (comp (ref "H10")
      (value "MountingHole")
      (footprint "3,0-PAD")
      (libsource (lib "SamacSys") (part "MountingHole"))
    )
    (comp (ref "H11")
      (value "MountingHole")
      (footprint "3,0-PAD")
      (libsource (lib "SamacSys") (part "MountingHole"))
    )
    (comp (ref "J1")
      (value "NC/105017-0001")
      (footprint "MOLEX_105017-0001")
      (fields (field (name "MP") "105017-0001") (field (name "MF") "Molex"))
      (libsource (lib "SnapEDAsch") (part "105017-0001"))
    )
    (comp (ref "J2")
      (value "197134001")
      (footprint "Crimp male 90 degree 0.25(6.35mm)")
      (description "Flachstecker Typ tyco/Electronics/AMP   Printed Circuit Board Tabs Source: http://www.buerklin.com")
      (fields (field (name "MF") "MF") (field (name "MPN") "MPN") (field (name "LIBRARYNAME") "con-faston"))
      (libsource (lib "SamacSys") (part "PIN3F061.120"))
    )
    (comp (ref "J3")
      (value "A1001WV-S-15P")
      (footprint "SH1.0 1X15P SMT VERTICAL")
      (fields
        (field (name "BOM_SUPPLIER PART") "C519176")
        (field (name "BOM_MANUFACTURER PART") "X2016WRS-10-9TSW")
        (field (name "CONTRIBUTOR") "LCSC")
      )
      (libsource (lib "") (part "1x15P SMT Connector_1"))
    )
    (comp (ref "J4")
      (value "197134001")
      (footprint "Crimp male 90 degree 0.25(6.35mm)")
      (description "Flachstecker Typ tyco/Electronics/AMP   Printed Circuit Board Tabs Source: http://www.buerklin.com")
      (fields (field (name "MF") "MF") (field (name "MPN") "MPN") (field (name "LIBRARYNAME") "con-faston"))
      (libsource (lib "SamacSys") (part "PIN3F061.120"))
    )
    (comp (ref "J5")
      (value "22-23-2061")
      (footprint "22-23-2061:22-23-2061")
      (description "Connector Header Through Hole 6 position 0.100 (2.54mm)")
      (fields (field (name "MF") "Molex"))
      (libsource (lib "SamacSys") (part "22-23-2061"))
    )
    (comp (ref "J6")
      (value "22-23-2021")
      (footprint "22-23-2021")
      (description "Connector Header Through Hole 2 position 0.100 (2.54mm)")
      (fields (field (name "MP") "22232021") (field (name "MF") "Molex"))
      (libsource (lib "SamacSys") (part "22-23-2021"))
    )
    (comp (ref "J7")
      (value "22-23-2041")
      (footprint "22-23-2041")
      (description "Connector Header Through Hole 4 position 0.100 (2.54mm)")
      (fields (field (name "MF") "Molex"))
      (libsource (lib "SamacSys") (part "22-23-2041"))
    )
    (comp (ref "J8")
      (value "22-23-2081")
      (footprint "22-23-2081")
      (description "Header, 8-Pin")
      (fields (field (name "PUBLISHER") "Altium Limited"))
      (libsource (lib "") (part "Header 8_1"))
    )
    (comp (ref "J15")
      (value "A1001WV-S-15P")
      (footprint "SH1.0 1X15P SMT VERTICAL")
      (fields
        (field (name "BOM_SUPPLIER PART") "C519176")
        (field (name "BOM_MANUFACTURER PART") "X2016WRS-10-9TSW")
        (field (name "CONTRIBUTOR") "LCSC")
      )
      (libsource (lib "Altium lib") (part "1x15P SMT Connector"))
    )
    (comp (ref "J16")
      (value "A1001WV-S-15P")
      (footprint "SH1.0 1X15P SMT VERTICAL")
      (fields
        (field (name "BOM_SUPPLIER PART") "C519176")
        (field (name "BOM_MANUFACTURER PART") "X2016WRS-10-9TSW")
        (field (name "CONTRIBUTOR") "LCSC")
      )
      (libsource (lib "Altium lib") (part "1x15P SMT Connector"))
    )
    (comp (ref "J17")
      (value "A1001WV-S-15P")
      (footprint "SH1.0 1X15P SMT VERTICAL")
      (fields
        (field (name "BOM_SUPPLIER PART") "C519176")
        (field (name "BOM_MANUFACTURER PART") "X2016WRS-10-9TSW")
        (field (name "CONTRIBUTOR") "LCSC")
      )
      (libsource (lib "Altium lib") (part "1x15P SMT Connector"))
    )
    (comp (ref "J18")
      (value "22-23-2041")
      (footprint "22-23-2041:22-23-2041")
      (description "Connector Header Through Hole 4 position 0.100 (2.54mm)")
      (fields (field (name "MF") "Molex"))
      (libsource (lib "SamacSys") (part "22-23-2041"))
    )
    (comp (ref "J19")
      (value "22-23-2041")
      (footprint "22-23-2041:22-23-2041")
      (description "Connector Header Through Hole 4 position 0.100 (2.54mm)")
      (fields (field (name "MF") "Molex"))
      (libsource (lib "SamacSys") (part "22-23-2041"))
    )
    (comp (ref "J20")
      (value "22-23-2081")
      (footprint "22-23-2081")
      (description "Header, 8-Pin")
      (fields (field (name "PUBLISHER") "Altium Limited"))
      (libsource (lib "Miscellaneous Connectors") (part "Header 8"))
    )
    (comp (ref "J21")
      (value "22-23-2081")
      (footprint "22-23-2081")
      (description "Header, 8-Pin")
      (fields (field (name "PUBLISHER") "Altium Limited"))
      (libsource (lib "Miscellaneous Connectors") (part "Header 8"))
    )
    (comp (ref "J28")
      (value "DM3AT-SF-PEJM5")
      (footprint "HRS_DM3AT-SF-PEJM5")
      (description "CONN MICRO SD CARD PUSH-PUSH R/A")
      (fields (field (name "MF") "Hirose"))
      (libsource (lib "Zigbee Sch Lib_SJCH") (part "DM3AT-SF-PEJM5"))
    )
    (comp (ref "J29")
      (value "NC/22-23-2081")
      (footprint "22-23-2081")
      (description "Header, 8-Pin")
      (fields (field (name "PUBLISHER") "Altium Limited"))
      (libsource (lib "") (part "Header 8_1"))
    )
    (comp (ref "J30")
      (value "NPPN172AFCN-RC")
      (footprint "HDR-TH_34P-P2.00-V-M-R2-C17-S2.00")
      (description "Header, 17-Pin, Dual row")
      (fields (field (name "PUBLISHER") "Altium Limited"))
      (libsource (lib "") (part "Header 17X2_1"))
    )
    (comp (ref "J31")
      (value "NPPN172AFCN-RC")
      (footprint "HDR-TH_34P-P2.00-V-M-R2-C17-S2.00")
      (description "Header, 17-Pin, Dual row")
      (fields (field (name "PUBLISHER") "Altium Limited"))
      (libsource (lib "Miscellaneous Connectors") (part "Header 17X2"))
    )
    (comp (ref "J32")
      (value "NPPN172AFCN-RC")
      (footprint "HDR-TH_34P-P2.00-V-M-R2-C17-S2.00")
      (description "Header, 17-Pin, Dual row")
      (fields (field (name "PUBLISHER") "Altium Limited"))
      (libsource (lib "") (part "Header 17X2_1"))
    )
    (comp (ref "J33")
      (value "NPPN172AFCN-RC")
      (footprint "HDR-TH_34P-P2.00-V-M-R2-C17-S2.00")
      (description "Header, 17-Pin, Dual row")
      (fields (field (name "PUBLISHER") "Altium Limited"))
      (libsource (lib "Miscellaneous Connectors") (part "Header 17X2"))
    )
    (comp (ref "J47")
      (value "NC/22-23-2021")
      (footprint "22-23-2021:22-23-2021")
      (description "Connector Header Through Hole 2 position 0.100 (2.54mm)")
      (fields (field (name "MP") "22232021") (field (name "MF") "Molex"))
      (libsource (lib "SamacSys") (part "22-23-2021"))
    )
    (comp (ref "J48")
      (value "NC/22-23-2021")
      (footprint "22-23-2021:22-23-2021")
      (description "Connector Header Through Hole 2 position 0.100 (2.54mm)")
      (fields (field (name "MP") "22232021") (field (name "MF") "Molex"))
      (libsource (lib "SamacSys") (part "22-23-2021"))
    )
    (comp (ref "J49")
      (value "NC/22-23-2041")
      (footprint "22-23-2041:22-23-2041")
      (description "Connector Header Through Hole 4 position 0.100 (2.54mm)")
      (fields (field (name "MF") "Molex") (field (name "MP") "22-23-2041"))
      (libsource (lib "SamacSys") (part "22-23-2041"))
    )
    (comp (ref "J51")
      (value "NC/22-23-2021")
      (footprint "22-23-2021:22-23-2021")
      (description "Connector Header Through Hole 2 position 0.100 (2.54mm)")
      (fields (field (name "MP") "22232021") (field (name "MF") "Molex"))
      (libsource (lib "SamacSys") (part "22-23-2021"))
    )
    (comp (ref "J52")
      (value "NC/22-23-2021")
      (footprint "22-23-2021:22-23-2021")
      (description "Connector Header Through Hole 2 position 0.100 (2.54mm)")
      (fields (field (name "MP") "22232021") (field (name "MF") "Molex"))
      (libsource (lib "SamacSys") (part "22-23-2021"))
    )
    (comp (ref "L2")
      (value "NC/600@100M")
      (footprint "L_0603_1608Metric")
      (description "CIM10J601NC")
      (fields (field (name "LIBRARYNAME") "inductors-jwmiller"))
      (libsource (lib "SamacSys") (part "FB-M1331"))
    )
    (comp (ref "L3")
      (value "600@100M")
      (footprint "L_0603_1608Metric")
      (description "BBPY00160808601Y00")
      (fields (field (name "LIBRARYNAME") "inductors-jwmiller"))
      (libsource (lib "SamacSys") (part "FB-M1331"))
    )
    (comp (ref "L4")
      (value "600@100M")
      (footprint "L_0603_1608Metric")
      (description "BBPY00160808601Y00")
      (fields (field (name "LIBRARYNAME") "inductors-jwmiller"))
      (libsource (lib "SamacSys") (part "FB-M1331"))
    )
    (comp (ref "L5")
      (value "NC/600@100M")
      (footprint "L_0603_1608Metric")
      (description "BBPY00160808601Y00")
      (fields (field (name "LIBRARYNAME") "inductors-jwmiller"))
      (libsource (lib "SamacSys") (part "FB-M1331"))
    )
    (comp (ref "L6")
      (value "NC/600@100M")
      (footprint "L_0603_1608Metric")
      (description "BBPY00160808601Y00")
      (fields (field (name "LIBRARYNAME") "inductors-jwmiller"))
      (libsource (lib "SamacSys") (part "FB-M1331"))
    )
    (comp (ref "L7")
      (value "NC/600@100M")
      (footprint "L_0603_1608Metric")
      (description "BBPY00160808601Y00")
      (fields (field (name "LIBRARYNAME") "inductors-jwmiller"))
      (libsource (lib "SamacSys") (part "FB-M1331"))
    )
    (comp (ref "L12")
      (value "SRN6045TA-150M")
      (footprint "IND_SRN6045TA-150M")
      (description "FIXED IND 47UH 1.6A 200 MOHM SMD")
      (libsource (lib "SRN6045TA-150M") (part "SRN6045TA-150M"))
    )
    (comp (ref "L13")
      (value "SRN6045TA-150M")
      (footprint "IND_SRN6045TA-150M")
      (description "FIXED IND 47UH 1.6A 200 MOHM SMD")
      (libsource (lib "SRN6045TA-150M") (part "SRN6045TA-150M"))
    )
    (comp (ref "L17")
      (value "600@100M")
      (footprint "L_0603_1608Metric")
      (description "BBPY00160808601Y00")
      (fields (field (name "LIBRARYNAME") "inductors-jwmiller"))
      (libsource (lib "SamacSys") (part "FB-M1331"))
    )
    (comp (ref "LED1")
      (value "150080VS75000")
      (footprint "LEDC2012X120N")
      (description "LED GREEN CLEAR 0805 SMD")
      (fields (field (name "MF") "Lumex Opto/Components") (field (name "MP") "SML-LXT0805IW-TR"))
      (libsource (lib "SamacSys") (part "SML-LXT0805IW-TR"))
    )
    (comp (ref "LED2")
      (value "150080VS75000")
      (footprint "LEDC2012X120N")
      (description "LED GREEN CLEAR 0805 SMD")
      (fields (field (name "MF") "Lumex Opto/Components") (field (name "MP") "SML-LXT0805IW-TR"))
      (libsource (lib "SamacSys") (part "SML-LXT0805IW-TR"))
    )
    (comp (ref "LED3")
      (value "150080VS75000")
      (footprint "LEDC2012X120N")
      (description "LED GREEN CLEAR 0805 SMD")
      (fields (field (name "MF") "Lumex Opto/Components") (field (name "MP") "SML-LXT0805IW-TR"))
      (libsource (lib "SamacSys") (part "SML-LXT0805IW-TR"))
    )
    (comp (ref "LED4")
      (value "150080VS75000")
      (footprint "LEDC2012X120N")
      (description "LED GREEN CLEAR 0805 SMD")
      (fields (field (name "MF") "Lumex Opto/Components") (field (name "MP") "SML-LXT0805IW-TR"))
      (libsource (lib "SamacSys") (part "SML-LXT0805IW-TR"))
    )
    (comp (ref "LED6")
      (value "150080SS75000")
      (footprint "LEDC2012X120N")
      (description "LED RED CLEAR 0805 SMD")
      (fields (field (name "MF") "Lumex Opto/Components") (field (name "MP") "SML-LXT0805IW-TR"))
      (libsource (lib "SamacSys") (part "SML-LXT0805IW-TR"))
    )
    (comp (ref "LED10")
      (value "150080SS75000")
      (footprint "LEDC2012X120N")
      (description "LED RED CLEAR 0805 SMD")
      (fields (field (name "MF") "Lumex Opto/Components") (field (name "MP") "SML-LXT0805IW-TR"))
      (libsource (lib "SamacSys") (part "SML-LXT0805IW-TR"))
    )
    (comp (ref "LED13")
      (value "150080VS75000")
      (footprint "LEDC2012X120N")
      (description "LED GREEN CLEAR 0805 SMD")
      (fields (field (name "MF") "Lumex Opto/Components") (field (name "MP") "SML-LXT0805IW-TR"))
      (libsource (lib "SamacSys") (part "SML-LXT0805IW-TR"))
    )
    (comp (ref "LED14")
      (value "150080VS75000")
      (footprint "LEDC2012X120N")
      (description "LED GREEN CLEAR 0805 SMD")
      (fields (field (name "MF") "Lumex Opto/Components") (field (name "MP") "SML-LXT0805IW-TR"))
      (libsource (lib "SamacSys") (part "SML-LXT0805IW-TR"))
    )
    (comp (ref "LED15")
      (value "150080VS75000")
      (footprint "LEDC2012X120N")
      (description "LED GREEN CLEAR 0805 SMD")
      (fields (field (name "MF") "Lumex Opto/Components") (field (name "MP") "SML-LXT0805IW-TR"))
      (libsource (lib "SamacSys") (part "SML-LXT0805IW-TR"))
    )
    (comp (ref "Q1")
      (value "PDTC114ET,215")
      (footprint "SOT95P230X110-3N")
      (description "TRANS PREBIAS NPN 250MW TO236AB")
      (libsource (lib "SamacSys") (part "PDTC114ET,215"))
    )
    (comp (ref "Q2")
      (value "PDTC114ET,215")
      (footprint "SOT95P230X110-3N")
      (description "TRANS PREBIAS NPN 250MW TO236AB")
      (libsource (lib "SamacSys") (part "PDTC114ET,215"))
    )
    (comp (ref "Q3")
      (value "PDTC114ET,215")
      (footprint "SOT95P230X110-3N")
      (description "TRANS PREBIAS NPN 250MW TO236AB")
      (libsource (lib "SamacSys") (part "PDTC114ET,215"))
    )
    (comp (ref "Q4")
      (value "PDTC114ET,215")
      (footprint "SOT95P230X110-3N")
      (description "TRANS PREBIAS NPN 250MW TO236AB")
      (libsource (lib "SamacSys") (part "PDTC114ET,215"))
    )
    (comp (ref "Q5")
      (value "PDTC114ET,215")
      (footprint "SOT95P230X110-3N")
      (description "TRANS PREBIAS NPN 250MW TO236AB")
      (libsource (lib "SamacSys") (part "PDTC114ET,215"))
    )
    (comp (ref "Q6")
      (value "NC/BC847B-7-F")
      (footprint "SOT95P230X110-3N")
      (libsource (lib "SamacSys") (part "BC847B-7-F"))
    )
    (comp (ref "Q7")
      (value "NC/BC847B-7-F")
      (footprint "SOT95P230X110-3N")
      (libsource (lib "SamacSys") (part "BC847B-7-F"))
    )
    (comp (ref "Q8")
      (value "PDTC114ET,215")
      (footprint "SOT95P230X110-3N")
      (description "TRANS PREBIAS NPN 250MW TO236AB")
      (libsource (lib "SamacSys") (part "PDTC114ET,215"))
    )
    (comp (ref "Q9")
      (value "PDTC114ET,215")
      (footprint "SOT95P230X110-3N")
      (description "TRANS PREBIAS NPN 250MW TO236AB")
      (libsource (lib "SamacSys") (part "PDTC114ET,215"))
    )
    (comp (ref "R1")
      (value "2K")
      (footprint "R_0603_1608Metric")
      (description "RES SMD 2K OHM 5% 1/10W 0603")
      (fields (field (name "PUBLISHER") "Altium Limited"))
      (libsource (lib "Miscellaneous Devices") (part "Res2"))
    )
    (comp (ref "R2")
      (value "2K")
      (footprint "R_0603_1608Metric")
      (description "RES SMD 2K OHM 5% 1/10W 0603")
      (fields (field (name "PUBLISHER") "Altium Limited"))
      (libsource (lib "Miscellaneous Devices") (part "Res2"))
    )
    (comp (ref "R3")
      (value "1.2K")
      (footprint "R_0603_1608Metric")
      (description "RES 1.2K OHM 5% 1/10W 0603")
      (fields (field (name "PUBLISHER") "Altium Limited"))
      (libsource (lib "Miscellaneous Devices") (part "Res2"))
    )
    (comp (ref "R4")
      (value "100R")
      (footprint "R_0603_1608Metric")
      (description "RES 100 OHM 5% 1/10W 0603")
      (libsource (lib "AT") (part "RES"))
    )
    (comp (ref "R5")
      (value "1K")
      (footprint "R_0603_1608Metric")
      (description "RES 1K OHM 5% 1/10W 0603")
      (fields (field (name "PUBLISHER") "Altium Limited"))
      (libsource (lib "Miscellaneous Devices") (part "Res2"))
    )
    (comp (ref "R6")
      (value "1K")
      (footprint "R_0603_1608Metric")
      (description "RES 1K OHM 5% 1/10W 0603")
      (fields (field (name "PUBLISHER") "Altium Limited"))
      (libsource (lib "Miscellaneous Devices") (part "Res2"))
    )
    (comp (ref "R7")
      (value "100R")
      (footprint "R_0603_1608Metric")
      (description "RES 100 OHM 5% 1/10W 0603")
      (libsource (lib "AT") (part "RES"))
    )
    (comp (ref "R8")
      (value "1K")
      (footprint "R_0603_1608Metric")
      (description "RES 1K OHM 5% 1/10W 0603")
      (fields (field (name "PUBLISHER") "Altium Limited"))
      (libsource (lib "Miscellaneous Devices") (part "Res2"))
    )
    (comp (ref "R9")
      (value "1K")
      (footprint "R_0603_1608Metric")
      (description "RES 1K OHM 5% 1/10W 0603")
      (fields (field (name "PUBLISHER") "Altium Limited"))
      (libsource (lib "Miscellaneous Devices") (part "Res2"))
    )
    (comp (ref "R10")
      (value "1K")
      (footprint "R_0603_1608Metric")
      (description "RES 1K OHM 5% 1/10W 0603")
      (fields (field (name "PUBLISHER") "Altium Limited"))
      (libsource (lib "Miscellaneous Devices") (part "Res2"))
    )
    (comp (ref "R11")
      (value "1.2K")
      (footprint "R_0603_1608Metric")
      (description "RES 1.2K OHM 5% 1/10W 0603")
      (fields (field (name "PUBLISHER") "Altium Limited"))
      (libsource (lib "Miscellaneous Devices") (part "Res2"))
    )
    (comp (ref "R12")
      (value "100R")
      (footprint "R_0603_1608Metric")
      (description "RES 100 OHM 5% 1/10W 0603")
      (libsource (lib "AT") (part "RES"))
    )
    (comp (ref "R13")
      (value "1K")
      (footprint "R_0603_1608Metric")
      (description "RES 1K OHM 5% 1/10W 0603")
      (fields (field (name "PUBLISHER") "Altium Limited"))
      (libsource (lib "Miscellaneous Devices") (part "Res2"))
    )
    (comp (ref "R14")
      (value "200K")
      (footprint "R_0603_1608Metric")
      (description "RES 100 OHM 5% 1/10W 0603")
      (libsource (lib "AT") (part "RES"))
    )
    (comp (ref "R15")
      (value "100R")
      (footprint "R_0603_1608Metric")
      (description "RES 100 OHM 5% 1/10W 0603")
      (libsource (lib "AT") (part "RES"))
    )
    (comp (ref "R16")
      (value "200K")
      (footprint "R_0603_1608Metric")
      (description "RES 100 OHM 5% 1/10W 0603")
      (libsource (lib "AT") (part "RES"))
    )
    (comp (ref "R17")
      (value "100R")
      (footprint "R_0603_1608Metric")
      (description "RES 100 OHM 5% 1/10W 0603")
      (libsource (lib "AT") (part "RES"))
    )
    (comp (ref "R18")
      (value "100R")
      (footprint "R_0603_1608Metric")
      (description "RES 100 OHM 5% 1/10W 0603")
      (libsource (lib "AT") (part "RES"))
    )
    (comp (ref "R19")
      (value "0R")
      (footprint "R_0603_1608Metric")
      (description "RES 0 OHM JUMPER 1/10W 0603")
      (libsource (lib "AT") (part "RES"))
    )
    (comp (ref "R20")
      (value "NC")
      (footprint "R_0603_1608Metric")
      (description "RES 100 OHM 5% 1/10W 0603")
      (libsource (lib "AT") (part "RES"))
    )
    (comp (ref "R21")
      (value "0R")
      (footprint "R_0603_1608Metric")
      (description "RES 0 OHM JUMPER 1/10W 0603")
      (libsource (lib "AT") (part "RES"))
    )
    (comp (ref "R22")
      (value "100R")
      (footprint "R_0603_1608Metric")
      (description "RES 100 OHM 5% 1/10W 0603")
      (libsource (lib "AT") (part "RES"))
    )
    (comp (ref "R23")
      (value "100R")
      (footprint "R_0603_1608Metric")
      (description "RES 100 OHM 5% 1/10W 0603")
      (libsource (lib "AT") (part "RES"))
    )
    (comp (ref "R24")
      (value "100R")
      (footprint "R_0603_1608Metric")
      (description "RES 100 OHM 5% 1/10W 0603")
      (libsource (lib "AT") (part "RES"))
    )
    (comp (ref "R25")
      (value "10K")
      (footprint "R_0603_1608Metric")
      (description "RES 10K OHM 5% 1/10W 0603")
      (fields (field (name "PUBLISHER") "Altium Limited"))
      (libsource (lib "") (part "Res2_3"))
    )
    (comp (ref "R26")
      (value "10K")
      (footprint "R_0603_1608Metric")
      (description "RES 10K OHM 5% 1/10W 0603")
      (fields (field (name "PUBLISHER") "Altium Limited"))
      (libsource (lib "Miscellaneous Devices") (part "Res2"))
    )
    (comp (ref "R27")
      (value "200K")
      (footprint "R_0603_1608Metric")
      (description "RES 100 OHM 5% 1/10W 0603")
      (libsource (lib "AT") (part "RES"))
    )
    (comp (ref "R28")
      (value "1K")
      (footprint "R_0603_1608Metric")
      (description "RES 1K OHM 5% 1/10W 0603")
      (fields (field (name "PUBLISHER") "Altium Limited"))
      (libsource (lib "") (part "Res2_2"))
    )
    (comp (ref "R29")
      (value "2K")
      (footprint "R_0603_1608Metric")
      (description "RES SMD 2K OHM 5% 1/10W 0603")
      (fields (field (name "PUBLISHER") "Altium Limited"))
      (libsource (lib "Miscellaneous Devices") (part "Res2"))
    )
    (comp (ref "R30")
      (value "1K")
      (footprint "R_0603_1608Metric")
      (description "RES 1K OHM 5% 1/10W 0603")
      (fields (field (name "PUBLISHER") "Altium Limited"))
      (libsource (lib "") (part "Res2_2"))
    )
    (comp (ref "R31")
      (value "100R")
      (footprint "R_0603_1608Metric")
      (description "RES 100 OHM 5% 1/10W 0603")
      (libsource (lib "AT") (part "RES"))
    )
    (comp (ref "R32")
      (value "200K")
      (footprint "R_0603_1608Metric")
      (description "RES 100 OHM 5% 1/10W 0603")
      (libsource (lib "AT") (part "RES"))
    )
    (comp (ref "R33")
      (value "100R")
      (footprint "R_0603_1608Metric")
      (description "RES 100 OHM 5% 1/10W 0603")
      (libsource (lib "AT") (part "RES"))
    )
    (comp (ref "R34")
      (value "2K")
      (footprint "R_0603_1608Metric")
      (description "RES SMD 2K OHM 5% 1/10W 0603")
      (fields (field (name "PUBLISHER") "Altium Limited"))
      (libsource (lib "Miscellaneous Devices") (part "Res2"))
    )
    (comp (ref "R35")
      (value "1.2K")
      (footprint "R_0603_1608Metric")
      (description "RES 1.2K OHM 5% 1/10W 0603")
      (fields (field (name "PUBLISHER") "Altium Limited"))
      (libsource (lib "Miscellaneous Devices") (part "Res2"))
    )
    (comp (ref "R36")
      (value "1.2K")
      (footprint "R_0603_1608Metric")
      (description "RES 1.2K OHM 5% 1/10W 0603")
      (fields (field (name "PUBLISHER") "Altium Limited"))
      (libsource (lib "Miscellaneous Devices") (part "Res2"))
    )
    (comp (ref "R37")
      (value "100R")
      (footprint "R_0603_1608Metric")
      (description "RES 100 OHM 5% 1/10W 0603")
      (libsource (lib "AT") (part "RES"))
    )
    (comp (ref "R38")
      (value "NC/4.7K")
      (footprint "R_0603_1608Metric")
      (description "CRCW08054K70FKEA")
      (fields (field (name "PUBLISHER") "Altium Limited"))
      (libsource (lib "Miscellaneous Devices") (part "Res2"))
    )
    (comp (ref "R39")
      (value "NC")
      (footprint "R_0603_1608Metric")
      (description "RES 100 OHM 5% 1/10W 0603")
      (libsource (lib "AT") (part "RES"))
    )
    (comp (ref "R40")
      (value "NC")
      (footprint "R_0603_1608Metric")
      (description "RES 100 OHM 5% 1/10W 0603")
      (libsource (lib "AT") (part "RES"))
    )
    (comp (ref "R41")
      (value "NC")
      (footprint "R_0603_1608Metric")
      (description "RES 100 OHM 5% 1/10W 0603")
      (libsource (lib "AT") (part "RES"))
    )
    (comp (ref "R42")
      (value "100R")
      (footprint "R_0603_1608Metric")
      (description "RES 100 OHM 5% 1/10W 0603")
      (libsource (lib "AT") (part "RES"))
    )
    (comp (ref "R43")
      (value "100R")
      (footprint "R_0603_1608Metric")
      (description "RES 100 OHM 5% 1/10W 0603")
      (libsource (lib "AT") (part "RES"))
    )
    (comp (ref "R44")
      (value "NC/4.7K")
      (footprint "R_0603_1608Metric")
      (description "CRCW08054K70FKEA")
      (fields (field (name "PUBLISHER") "Altium Limited"))
      (libsource (lib "") (part "Res2_3"))
    )
    (comp (ref "R45")
      (value "100R")
      (footprint "R_0603_1608Metric")
      (description "RES 100 OHM 5% 1/10W 0603")
      (libsource (lib "AT") (part "RES"))
    )
    (comp (ref "R46")
      (value "200K")
      (footprint "R_0603_1608Metric")
      (description "RES 100 OHM 5% 1/10W 0603")
      (libsource (lib "AT") (part "RES"))
    )
    (comp (ref "R47")
      (value "100R")
      (footprint "R_0603_1608Metric")
      (description "RES 100 OHM 5% 1/10W 0603")
      (libsource (lib "AT") (part "RES"))
    )
    (comp (ref "R48")
      (value "1K")
      (footprint "R_0603_1608Metric")
      (description "RES 1K OHM 5% 1/10W 0603")
      (fields (field (name "PUBLISHER") "Altium Limited"))
      (libsource (lib "") (part "Res2_1"))
    )
    (comp (ref "R49")
      (value "1K")
      (footprint "R_0603_1608Metric")
      (description "RES 1K OHM 5% 1/10W 0603")
      (fields (field (name "PUBLISHER") "Altium Limited"))
      (libsource (lib "") (part "Res2_1"))
    )
    (comp (ref "R50")
      (value "1K")
      (footprint "R_0603_1608Metric")
      (description "RES 1K OHM 5% 1/10W 0603")
      (fields (field (name "PUBLISHER") "Altium Limited"))
      (libsource (lib "") (part "Res2_1"))
    )
    (comp (ref "R51")
      (value "1K")
      (footprint "R_0603_1608Metric")
      (description "RES 1K OHM 5% 1/10W 0603")
      (fields (field (name "PUBLISHER") "Altium Limited"))
      (libsource (lib "") (part "Res2_1"))
    )
    (comp (ref "R52")
      (value "200K")
      (footprint "R_0603_1608Metric")
      (description "RES 100 OHM 5% 1/10W 0603")
      (libsource (lib "AT") (part "RES"))
    )
    (comp (ref "R53")
      (value "100R")
      (footprint "R_0603_1608Metric")
      (description "RES 100 OHM 5% 1/10W 0603")
      (libsource (lib "AT") (part "RES"))
    )
    (comp (ref "R54")
      (value "100R")
      (footprint "R_0603_1608Metric")
      (description "RES 100 OHM 5% 1/10W 0603")
      (libsource (lib "AT") (part "RES"))
    )
    (comp (ref "R55")
      (value "NC")
      (footprint "R_0603_1608Metric")
      (description "RES 100 OHM 5% 1/10W 0603")
      (libsource (lib "AT") (part "RES"))
    )
    (comp (ref "R56")
      (value "NC")
      (footprint "R_0603_1608Metric")
      (description "RES 100 OHM 5% 1/10W 0603")
      (libsource (lib "AT") (part "RES"))
    )
    (comp (ref "R57")
      (value "NC/100R")
      (footprint "R_0603_1608Metric")
      (description "RES 100 OHM 5% 1/10W 0603")
      (libsource (lib "AT") (part "RES"))
    )
    (comp (ref "R58")
      (value "NC/100R")
      (footprint "R_0603_1608Metric")
      (description "RES 100 OHM 5% 1/10W 0603")
      (libsource (lib "AT") (part "RES"))
    )
    (comp (ref "R59")
      (value "NC")
      (footprint "R_0603_1608Metric")
      (description "RES 100 OHM 5% 1/10W 0603")
      (libsource (lib "AT") (part "RES"))
    )
    (comp (ref "R60")
      (value "10K")
      (footprint "R_0603_1608Metric")
      (description "RES 10K OHM 5% 1/10W 0603")
      (fields (field (name "PUBLISHER") "Altium Limited"))
      (libsource (lib "") (part "Res2_2"))
    )
    (comp (ref "R61")
      (value "10K")
      (footprint "R_0603_1608Metric")
      (description "RES 10K OHM 5% 1/10W 0603")
      (fields (field (name "PUBLISHER") "Altium Limited"))
      (libsource (lib "") (part "Res2_2"))
    )
    (comp (ref "R62")
      (value "10K")
      (footprint "R_0603_1608Metric")
      (description "RES 10K OHM 5% 1/10W 0603")
      (fields (field (name "PUBLISHER") "Altium Limited"))
      (libsource (lib "") (part "Res2_2"))
    )
    (comp (ref "R63")
      (value "NC/10K")
      (footprint "R_0603_1608Metric")
      (description "RC0805FR-071KL")
      (libsource (lib "AT") (part "RES"))
    )
    (comp (ref "R64")
      (value "NC/10K")
      (footprint "R_0603_1608Metric")
      (description "RC0805FR-071KL")
      (libsource (lib "AT") (part "RES"))
    )
    (comp (ref "R65")
      (value "10K")
      (footprint "R_0603_1608Metric")
      (description "RES 10K OHM 5% 1/10W 0603")
      (fields (field (name "PUBLISHER") "Altium Limited"))
      (libsource (lib "") (part "Res2_3"))
    )
    (comp (ref "R66")
      (value "NC/100R")
      (footprint "R_0603_1608Metric")
      (description "RES 100 OHM 5% 1/10W 0603")
      (libsource (lib "AT") (part "RES"))
    )
    (comp (ref "R67")
      (value "NC/100R")
      (footprint "R_0603_1608Metric")
      (description "RES 100 OHM 5% 1/10W 0603")
      (libsource (lib "AT") (part "RES"))
    )
    (comp (ref "R68")
      (value "NC/100R")
      (footprint "R_0603_1608Metric")
      (description "RES 100 OHM 5% 1/10W 0603")
      (libsource (lib "AT") (part "RES"))
    )
    (comp (ref "R69")
      (value "NC/100R")
      (footprint "R_0603_1608Metric")
      (description "RES 100 OHM 5% 1/10W 0603")
      (libsource (lib "AT") (part "RES"))
    )
    (comp (ref "R70")
      (value "NC/100R")
      (footprint "R_0603_1608Metric")
      (description "RES 100 OHM 5% 1/10W 0603")
      (libsource (lib "AT") (part "RES"))
    )
    (comp (ref "R71")
      (value "NC/100R")
      (footprint "R_0603_1608Metric")
      (description "RES 100 OHM 5% 1/10W 0603")
      (libsource (lib "AT") (part "RES"))
    )
    (comp (ref "R72")
      (value "NC/100R")
      (footprint "R_0603_1608Metric")
      (description "RES 100 OHM 5% 1/10W 0603")
      (libsource (lib "AT") (part "RES"))
    )
    (comp (ref "R73")
      (value "10K")
      (footprint "R_0603_1608Metric")
      (description "RES 10K OHM 5% 1/10W 0603")
      (fields (field (name "PUBLISHER") "Altium Limited"))
      (libsource (lib "") (part "Res2_2"))
    )
    (comp (ref "R74")
      (value "NC/100R")
      (footprint "R_0603_1608Metric")
      (description "RES 100 OHM 5% 1/10W 0603")
      (libsource (lib "AT") (part "RES"))
    )
    (comp (ref "R75")
      (value "NC/100R")
      (footprint "R_0603_1608Metric")
      (description "RES 100 OHM 5% 1/10W 0603")
      (libsource (lib "AT") (part "RES"))
    )
    (comp (ref "R76")
      (value "NC/100R")
      (footprint "R_0603_1608Metric")
      (description "RES 100 OHM 5% 1/10W 0603")
      (libsource (lib "AT") (part "RES"))
    )
    (comp (ref "R77")
      (value "NC/100R")
      (footprint "R_0603_1608Metric")
      (description "RES 100 OHM 5% 1/10W 0603")
      (libsource (lib "AT") (part "RES"))
    )
    (comp (ref "R78")
      (value "NC/100R")
      (footprint "R_0603_1608Metric")
      (description "RES 100 OHM 5% 1/10W 0603")
      (libsource (lib "AT") (part "RES"))
    )
    (comp (ref "R79")
      (value "NC/100R")
      (footprint "R_0603_1608Metric")
      (description "RES 100 OHM 5% 1/10W 0603")
      (libsource (lib "AT") (part "RES"))
    )
    (comp (ref "R80")
      (value "NC/100R")
      (footprint "R_0603_1608Metric")
      (description "RES 100 OHM 5% 1/10W 0603")
      (libsource (lib "AT") (part "RES"))
    )
    (comp (ref "R81")
      (value "NC/10K")
      (footprint "R_0603_1608Metric")
      (description "RC0805FR-071KL")
      (libsource (lib "AT") (part "RES"))
    )
    (comp (ref "R82")
      (value "NC/10K")
      (footprint "R_0603_1608Metric")
      (description "RC0805FR-071KL")
      (libsource (lib "AT") (part "RES"))
    )
    (comp (ref "R83")
      (value "1K")
      (footprint "R_0603_1608Metric")
      (description "RES 1K OHM 5% 1/10W 0603")
      (fields (field (name "PUBLISHER") "Altium Limited"))
      (libsource (lib "") (part "Res2_3"))
    )
    (comp (ref "R84")
      (value "0R")
      (footprint "R_0603_1608Metric")
      (description "RES 0 OHM JUMPER 1/10W 0603")
      (libsource (lib "AT") (part "RES"))
    )
    (comp (ref "R85")
      (value "NC/10K")
      (footprint "R_0603_1608Metric")
      (description "RC0805FR-071KL")
      (libsource (lib "AT") (part "RES"))
    )
    (comp (ref "R86")
      (value "10K")
      (footprint "R_0603_1608Metric")
      (description "RES 10K OHM 5% 1/10W 0603")
      (fields (field (name "PUBLISHER") "Altium Limited"))
      (libsource (lib "") (part "Res2_2"))
    )
    (comp (ref "R87")
      (value "330K")
      (footprint "R_0603_1608Metric")
      (description "RES 330K OHM 5% 1/10W 0603")
      (libsource (lib "AT") (part "RES"))
    )
    (comp (ref "R88")
      (value "NC/10K")
      (footprint "R_0603_1608Metric")
      (description "RC0805FR-071KL")
      (libsource (lib "AT") (part "RES"))
    )
    (comp (ref "R89")
      (value "330K")
      (footprint "R_0603_1608Metric")
      (description "RES 330K OHM 5% 1/10W 0603")
      (libsource (lib "AT") (part "RES"))
    )
    (comp (ref "R90")
      (value "330K")
      (footprint "R_0603_1608Metric")
      (description "RES 330K OHM 5% 1/10W 0603")
      (libsource (lib "AT") (part "RES"))
    )
    (comp (ref "R91")
      (value "330K")
      (footprint "R_0603_1608Metric")
      (description "RES 330K OHM 5% 1/10W 0603")
      (libsource (lib "AT") (part "RES"))
    )
    (comp (ref "R92")
      (value "330K")
      (footprint "R_0603_1608Metric")
      (description "RES 330K OHM 5% 1/10W 0603")
      (libsource (lib "AT") (part "RES"))
    )
    (comp (ref "R93")
      (value "330K")
      (footprint "R_0603_1608Metric")
      (description "RES 330K OHM 5% 1/10W 0603")
      (libsource (lib "AT") (part "RES"))
    )
    (comp (ref "R94")
      (value "0R")
      (footprint "R_0603_1608Metric")
      (description "RES 0 OHM JUMPER 1/10W 0603")
      (libsource (lib "AT") (part "RES"))
    )
    (comp (ref "R95")
      (value "0R")
      (footprint "R_0603_1608Metric")
      (description "RES 0 OHM JUMPER 1/10W 0603")
      (libsource (lib "AT") (part "RES"))
    )
    (comp (ref "R96")
      (value "0R")
      (footprint "R_0603_1608Metric")
      (description "RES 0 OHM JUMPER 1/10W 0603")
      (libsource (lib "AT") (part "RES"))
    )
    (comp (ref "R97")
      (value "51K 1%")
      (footprint "R_0603_1608Metric")
      (description "RES 51K OHM 1% 1/10W 0603")
      (fields (field (name "PUBLISHER") "Altium Limited"))
      (libsource (lib "Miscellaneous Devices") (part "Res2"))
    )
    (comp (ref "R98")
      (value "1K")
      (footprint "R_0603_1608Metric")
      (description "RES 1K OHM 5% 1/10W 0603")
      (fields (field (name "PUBLISHER") "Altium Limited"))
      (libsource (lib "") (part "Res2_1"))
    )
    (comp (ref "R100")
      (value "22.1K 1%")
      (footprint "R_0603_1608Metric")
      (description "RES 22.1K OHM 1% 1/10W 0603")
      (fields (field (name "PUBLISHER") "Altium Limited"))
      (libsource (lib "Miscellaneous Devices") (part "Res2"))
    )
    (comp (ref "R101")
      (value "100K")
      (footprint "R_0603_1608Metric")
      (description "RES SMD 100K OHM 5% 1/10W 0603")
      (fields (field (name "PUBLISHER") "Altium Limited"))
      (libsource (lib "Miscellaneous Devices") (part "Res2"))
    )
    (comp (ref "R102")
      (value "NC/10K")
      (footprint "R_0603_1608Metric")
      (description "RC0805FR-071KL")
      (libsource (lib "AT") (part "RES"))
    )
    (comp (ref "R128")
      (value "10K")
      (footprint "R_0603_1608Metric")
      (description "RES 10K OHM 5% 1/10W 0603")
      (fields (field (name "PUBLISHER") "Altium Limited"))
      (libsource (lib "Miscellaneous Devices") (part "Res2"))
    )
    (comp (ref "R133")
      (value "88.7K 1%")
      (footprint "R_0603_1608Metric")
      (description "RES 88.7K OHM 1% 1/10W 0603")
      (fields (field (name "PUBLISHER") "Altium Limited"))
      (libsource (lib "Miscellaneous Devices") (part "Res2"))
    )
    (comp (ref "R134")
      (value "22.1K 1%")
      (footprint "R_0603_1608Metric")
      (description "RES 22.1K OHM 1% 1/10W 0603")
      (fields (field (name "PUBLISHER") "Altium Limited"))
      (libsource (lib "Miscellaneous Devices") (part "Res2"))
    )
    (comp (ref "R139")
      (value "100K")
      (footprint "R_0603_1608Metric")
      (description "RES SMD 100K OHM 5% 1/10W 0603")
      (fields (field (name "PUBLISHER") "Altium Limited"))
      (libsource (lib "Miscellaneous Devices") (part "Res2"))
    )
    (comp (ref "R140")
      (value "NC")
      (footprint "R_0603_1608Metric")
      (description "CRCW0805100KFKEAC")
      (fields (field (name "PUBLISHER") "Altium Limited"))
      (libsource (lib "Miscellaneous Devices") (part "Res2"))
    )
    (comp (ref "R141")
      (value "100K")
      (footprint "R_0603_1608Metric")
      (description "RES SMD 100K OHM 5% 1/10W 0603")
      (fields (field (name "PUBLISHER") "Altium Limited"))
      (libsource (lib "Miscellaneous Devices") (part "Res2"))
    )
    (comp (ref "R142")
      (value "NC")
      (footprint "R_0603_1608Metric")
      (description "CRCW0805100KFKEAC")
      (fields (field (name "PUBLISHER") "Altium Limited"))
      (libsource (lib "Miscellaneous Devices") (part "Res2"))
    )
    (comp (ref "R143")
      (value "NC/10K")
      (footprint "R_0603_1608Metric")
      (description "RC0805FR-071KL")
      (libsource (lib "AT") (part "RES"))
    )
    (comp (ref "R144")
      (value "NC/10K")
      (footprint "R_0603_1608Metric")
      (description "RC0805FR-071KL")
      (libsource (lib "AT") (part "RES"))
    )
    (comp (ref "R148")
      (value "NC/10K")
      (footprint "R_0603_1608Metric")
      (description "RC0805FR-071KL")
      (libsource (lib "AT") (part "RES"))
    )
    (comp (ref "R149")
      (value "NC/10K")
      (footprint "R_0603_1608Metric")
      (description "RC0805FR-071KL")
      (libsource (lib "AT") (part "RES"))
    )
    (comp (ref "R150")
      (value "NC/10K")
      (footprint "R_0603_1608Metric")
      (description "RC0805FR-071KL")
      (libsource (lib "AT") (part "RES"))
    )
    (comp (ref "R151")
      (value "NC/10K")
      (footprint "R_0603_1608Metric")
      (description "RC0805FR-071KL")
      (libsource (lib "AT") (part "RES"))
    )
    (comp (ref "R152")
      (value "NC/10K")
      (footprint "R_0603_1608Metric")
      (description "RC0805FR-071KL")
      (libsource (lib "AT") (part "RES"))
    )
    (comp (ref "R153")
      (value "NC/10K")
      (footprint "R_0603_1608Metric")
      (description "RC0805FR-071KL")
      (libsource (lib "AT") (part "RES"))
    )
    (comp (ref "R154")
      (value "NC/10K")
      (footprint "R_0603_1608Metric")
      (description "RC0805FR-071KL")
      (libsource (lib "AT") (part "RES"))
    )
    (comp (ref "R157")
      (value "10K")
      (footprint "R_0603_1608Metric")
      (description "RES 10K OHM 5% 1/10W 0603")
      (fields (field (name "PUBLISHER") "Altium Limited"))
      (libsource (lib "Miscellaneous Devices") (part "Res2"))
    )
    (comp (ref "R158")
      (value "10K")
      (footprint "R_0603_1608Metric")
      (description "RES 10K OHM 5% 1/10W 0603")
      (fields (field (name "PUBLISHER") "Altium Limited"))
      (libsource (lib "Miscellaneous Devices") (part "Res2"))
    )
    (comp (ref "R161")
      (value "10K")
      (footprint "R_0603_1608Metric")
      (description "RES 10K OHM 5% 1/10W 0603")
      (fields (field (name "PUBLISHER") "Altium Limited"))
      (libsource (lib "Miscellaneous Devices") (part "Res2"))
    )
    (comp (ref "R162")
      (value "10K")
      (footprint "R_0603_1608Metric")
      (description "RES 10K OHM 5% 1/10W 0603")
      (fields (field (name "PUBLISHER") "Altium Limited"))
      (libsource (lib "Miscellaneous Devices") (part "Res2"))
    )
    (comp (ref "R163")
      (value "100R")
      (footprint "R_0603_1608Metric")
      (description "RES 100 OHM 5% 1/10W 0603")
      (libsource (lib "AT") (part "RES"))
    )
    (comp (ref "R164")
      (value "100R")
      (footprint "R_0603_1608Metric")
      (description "RES 100 OHM 5% 1/10W 0603")
      (libsource (lib "AT") (part "RES"))
    )
    (comp (ref "R165")
      (value "100R")
      (footprint "R_0603_1608Metric")
      (description "RES 100 OHM 5% 1/10W 0603")
      (libsource (lib "AT") (part "RES"))
    )
    (comp (ref "R166")
      (value "100R")
      (footprint "R_0603_1608Metric")
      (description "RES 100 OHM 5% 1/10W 0603")
      (libsource (lib "AT") (part "RES"))
    )
    (comp (ref "R167")
      (value "NC/100R")
      (footprint "R_0603_1608Metric")
      (description "RES 100 OHM 5% 1/10W 0603")
      (fields (field (name "PUBLISHER") "Altium Limited"))
      (libsource (lib "") (part "Res2_1"))
    )
    (comp (ref "R168")
      (value "NC/100R")
      (footprint "R_0603_1608Metric")
      (description "RES 100 OHM 5% 1/10W 0603")
      (fields (field (name "PUBLISHER") "Altium Limited"))
      (libsource (lib "") (part "Res2_1"))
    )
    (comp (ref "R169")
      (value "NC/100R")
      (footprint "R_0603_1608Metric")
      (description "RES 100 OHM 5% 1/10W 0603")
      (fields (field (name "PUBLISHER") "Altium Limited"))
      (libsource (lib "") (part "Res2_1"))
    )
    (comp (ref "R170")
      (value "NC/100R")
      (footprint "R_0603_1608Metric")
      (description "RES 100 OHM 5% 1/10W 0603")
      (fields (field (name "PUBLISHER") "Altium Limited"))
      (libsource (lib "") (part "Res2_1"))
    )
    (comp (ref "RN1")
      (value "YC124-JR-0747RL")
      (footprint "RESCAXS50P200X100X55-8N")
      (description "RES ARRAY 4 RES 47 OHM 0804")
      (fields (field (name "MF") "Yageo") (field (name "MP") "TC164-JR-0747RL"))
      (libsource (lib "Zigbee Sch Lib_SJCH") (part "TC164-JR-0747RL"))
    )
    (comp (ref "RN3")
      (value "YC124-JR-0747RL")
      (footprint "RESCAXS50P200X100X55-8N")
      (description "RES ARRAY 4 RES 47 OHM 0804")
      (fields (field (name "MF") "Yageo") (field (name "MP") "TC164-JR-0747RL"))
      (libsource (lib "Zigbee Sch Lib_SJCH") (part "TC164-JR-0747RL"))
    )
    (comp (ref "S1")
      (value "KG04ET")
      (footprint "SW_DS01-254-S-04BE")
      (description "STANDARD DIP SWITCH, 4 POSITIONS")
      (fields (field (name "MP") "DS01-254-S-04BE") (field (name "MF") "CUI Devices"))
      (libsource (lib "SamacSys") (part "4 Position Dip Switch"))
    )
    (comp (ref "U1")
      (value "LTV-847S")
      (footprint "SMD-16 19.84X7.62MM P2.54mm")
      (description "OPTOISOLTR 5KV 4CH TRANS 16-SMD")
      (libsource (lib "Altium lib") (part "LTV-847S"))
    )
    (comp (ref "U2")
      (value "NC/USBLC6-2SC6")
      (footprint "SOT95P280X145-6N")
      (fields (field (name "MP") "USBLC6-2SC6") (field (name "MF") "STMicroelectronics"))
      (libsource (lib "SnapEDAsch") (part "USBLC6-2SC6"))
    )
    (comp (ref "U7")
      (value "SST26VF016BT-80E/SN")
      (footprint "SOIC-8")
      (description "IC FLASH 16MBIT SPI/QUAD 8SOIC")
      (libsource (lib "SamacSys") (part "MX25L6406EM2I-12G"))
    )
    (comp (ref "U8")
      (value "XBee3 through-hole module")
      (footprint "XB3-24Z8PT-J")
      (description "RECEPTACLE STRIP 10P 2.0MM PITCH")
      (fields (field (name "MP") "XB3-24Z8PT-J") (field (name "MF") "Digi International"))
      (libsource (lib "Altium lib") (part "XB3-24Z8PT-J"))
    )
    (comp (ref "U27")
      (value "TPS560430XFDBVR")
      (footprint "SOT95P280X145-6N")
      (description "IC REG BUCK PWM 600MA SOT23-6")
      (libsource (lib "TPS560430XFDBVR") (part "TPS560430XFDBVR"))
    )
    (comp (ref "U33")
      (value "TPS560430XFDBVR")
      (footprint "SOT95P280X145-6N")
      (description "IC REG BUCK PWM 600MA SOT23-6")
      (libsource (lib "TPS560430XFDBVR") (part "TPS560430XFDBVR"))
    )
  )
  (nets
    (net (code "1") (name "/A_DECAY{slash}NPCS0") (class "Default")
      (node (ref "D10") (pin "5") (pinfunction "5_cathode_5") (pintype "passive"))
      (node (ref "J15") (pin "9") (pinfunction "9_9") (pintype "passive"))
      (node (ref "R16") (pin "1") (pinfunction "1_1") (pintype "passive"))
      (node (ref "R89") (pin "1") (pinfunction "1_1") (pintype "passive"))
    )
    (net (code "2") (name "/A_EN{slash}IN1") (class "Default")
      (node (ref "D10") (pin "3") (pinfunction "2_cathode_3") (pintype "passive"))
      (node (ref "J15") (pin "7") (pinfunction "7_7") (pintype "passive"))
      (node (ref "R17") (pin "2") (pinfunction "2_2") (pintype "passive"))
    )
    (net (code "3") (name "/A_MISO") (class "Default")
      (node (ref "D11") (pin "1") (pinfunction "1_cathode_1") (pintype "passive"))
      (node (ref "J15") (pin "2") (pinfunction "2_2") (pintype "passive"))
      (node (ref "R19") (pin "2") (pinfunction "2_2") (pintype "passive"))
    )
    (net (code "4") (name "/A_MOSI") (class "Default")
      (node (ref "D11") (pin "3") (pinfunction "2_cathode_3") (pintype "passive"))
      (node (ref "J15") (pin "1") (pinfunction "1_1") (pintype "passive"))
      (node (ref "R21") (pin "2") (pinfunction "2_2") (pintype "passive"))
    )
    (net (code "5") (name "/A_PH{slash}IN2") (class "Default")
      (node (ref "D10") (pin "1") (pinfunction "1_cathode_1") (pintype "passive"))
      (node (ref "J15") (pin "8") (pinfunction "8_8") (pintype "passive"))
      (node (ref "R15") (pin "2") (pinfunction "2_2") (pintype "passive"))
    )
    (net (code "6") (name "/A_SCL") (class "Default")
      (node (ref "D9") (pin "1") (pinfunction "1_cathode_1") (pintype "passive"))
      (node (ref "J15") (pin "12") (pinfunction "12_12") (pintype "passive"))
      (node (ref "R4") (pin "2") (pinfunction "2_2") (pintype "passive"))
    )
    (net (code "7") (name "/A_SDA") (class "Default")
      (node (ref "D9") (pin "3") (pinfunction "2_cathode_3") (pintype "passive"))
      (node (ref "J15") (pin "11") (pinfunction "11_11") (pintype "passive"))
      (node (ref "R12") (pin "2") (pinfunction "2_2") (pintype "passive"))
    )
    (net (code "8") (name "/A_SPCK") (class "Default")
      (node (ref "D11") (pin "5") (pinfunction "5_cathode_5") (pintype "passive"))
      (node (ref "J15") (pin "3") (pinfunction "3_3") (pintype "passive"))
      (node (ref "R20") (pin "1") (pinfunction "1_1") (pintype "passive"))
    )
    (net (code "9") (name "/A_TOFF") (class "Default")
      (node (ref "D9") (pin "4") (pinfunction "3_cathode_4") (pintype "passive"))
      (node (ref "J15") (pin "10") (pinfunction "10_10") (pintype "passive"))
      (node (ref "R14") (pin "1") (pinfunction "1_1") (pintype "passive"))
      (node (ref "R87") (pin "1") (pinfunction "1_1") (pintype "passive"))
    )
    (net (code "10") (name "/A_nFAULT") (class "Default")
      (node (ref "D9") (pin "5") (pinfunction "5_cathode_5") (pintype "passive"))
      (node (ref "J15") (pin "13") (pinfunction "13_13") (pintype "passive"))
      (node (ref "R7") (pin "1") (pinfunction "1_1") (pintype "passive"))
    )
    (net (code "11") (name "/A_nSLEEP") (class "Default")
      (node (ref "D10") (pin "4") (pinfunction "3_cathode_4") (pintype "passive"))
      (node (ref "J15") (pin "6") (pinfunction "6_6") (pintype "passive"))
      (node (ref "R18") (pin "1") (pinfunction "1_1") (pintype "passive"))
    )
    (net (code "12") (name "/B_DECAY{slash}NPCS2") (class "Default")
      (node (ref "D13") (pin "5") (pinfunction "5_cathode_5") (pintype "passive"))
      (node (ref "J16") (pin "9") (pinfunction "9_9") (pintype "passive"))
      (node (ref "R32") (pin "1") (pinfunction "1_1") (pintype "passive"))
      (node (ref "R91") (pin "1") (pinfunction "1_1") (pintype "passive"))
    )
    (net (code "13") (name "/B_EN{slash}IN1") (class "Default")
      (node (ref "D13") (pin "3") (pinfunction "2_cathode_3") (pintype "passive"))
      (node (ref "J16") (pin "7") (pinfunction "7_7") (pintype "passive"))
      (node (ref "R33") (pin "2") (pinfunction "2_2") (pintype "passive"))
    )
    (net (code "14") (name "/B_MISO") (class "Default")
      (node (ref "D14") (pin "1") (pinfunction "1_cathode_1") (pintype "passive"))
      (node (ref "J16") (pin "2") (pinfunction "2_2") (pintype "passive"))
      (node (ref "R39") (pin "2") (pinfunction "2_2") (pintype "passive"))
      (node (ref "R84") (pin "2") (pinfunction "2_2") (pintype "passive"))
    )
    (net (code "15") (name "/B_MOSI") (class "Default")
      (node (ref "D14") (pin "3") (pinfunction "2_cathode_3") (pintype "passive"))
      (node (ref "J16") (pin "1") (pinfunction "1_1") (pintype "passive"))
      (node (ref "R41") (pin "2") (pinfunction "2_2") (pintype "passive"))
      (node (ref "R95") (pin "2") (pinfunction "2_2") (pintype "passive"))
    )
    (net (code "16") (name "/B_PH{slash}IN2") (class "Default")
      (node (ref "D13") (pin "1") (pinfunction "1_cathode_1") (pintype "passive"))
      (node (ref "J16") (pin "8") (pinfunction "8_8") (pintype "passive"))
      (node (ref "R31") (pin "2") (pinfunction "2_2") (pintype "passive"))
    )
    (net (code "17") (name "/B_SCL") (class "Default")
      (node (ref "D12") (pin "1") (pinfunction "1_cathode_1") (pintype "passive"))
      (node (ref "J16") (pin "12") (pinfunction "12_12") (pintype "passive"))
      (node (ref "R22") (pin "2") (pinfunction "2_2") (pintype "passive"))
    )
    (net (code "18") (name "/B_SDA") (class "Default")
      (node (ref "D12") (pin "3") (pinfunction "2_cathode_3") (pintype "passive"))
      (node (ref "J16") (pin "11") (pinfunction "11_11") (pintype "passive"))
      (node (ref "R24") (pin "2") (pinfunction "2_2") (pintype "passive"))
    )
    (net (code "19") (name "/B_SPCK") (class "Default")
      (node (ref "D14") (pin "5") (pinfunction "5_cathode_5") (pintype "passive"))
      (node (ref "J16") (pin "3") (pinfunction "3_3") (pintype "passive"))
      (node (ref "R40") (pin "1") (pinfunction "1_1") (pintype "passive"))
    )
    (net (code "20") (name "/B_TOFF") (class "Default")
      (node (ref "D12") (pin "4") (pinfunction "3_cathode_4") (pintype "passive"))
      (node (ref "J16") (pin "10") (pinfunction "10_10") (pintype "passive"))
      (node (ref "R27") (pin "1") (pinfunction "1_1") (pintype "passive"))
      (node (ref "R90") (pin "1") (pinfunction "1_1") (pintype "passive"))
    )
    (net (code "21") (name "/B_nFAULT") (class "Default")
      (node (ref "D12") (pin "5") (pinfunction "5_cathode_5") (pintype "passive"))
      (node (ref "J16") (pin "13") (pinfunction "13_13") (pintype "passive"))
      (node (ref "R23") (pin "1") (pinfunction "1_1") (pintype "passive"))
    )
    (net (code "22") (name "/B_nSLEEP") (class "Default")
      (node (ref "D13") (pin "4") (pinfunction "3_cathode_4") (pintype "passive"))
      (node (ref "J16") (pin "6") (pinfunction "6_6") (pintype "passive"))
      (node (ref "R37") (pin "1") (pinfunction "1_1") (pintype "passive"))
    )
    (net (code "23") (name "/Black1") (class "Default")
      (node (ref "J7") (pin "1") (pinfunction "S_1") (pintype "passive"))
      (node (ref "U1") (pin "8") (pinfunction "4_Cathode_8") (pintype "passive"))
    )
    (net (code "24") (name "/Black2") (class "Default")
      (node (ref "J7") (pin "2") (pinfunction "S_2") (pintype "passive"))
      (node (ref "U1") (pin "1") (pinfunction "1_Anode_1") (pintype "passive"))
    )
    (net (code "25") (name "/Black3") (class "Default")
      (node (ref "J7") (pin "3") (pinfunction "S_3") (pintype "passive"))
      (node (ref "U1") (pin "4") (pinfunction "2_Cathode_4") (pintype "passive"))
    )
    (net (code "26") (name "/Black4") (class "Default")
      (node (ref "J7") (pin "4") (pinfunction "S_4") (pintype "passive"))
      (node (ref "U1") (pin "6") (pinfunction "3_Cathode_6") (pintype "passive"))
    )
    (net (code "27") (name "/CTS") (class "Default")
      (node (ref "RN1") (pin "4") (pinfunction "4_4") (pintype "passive"))
      (node (ref "U8") (pin "12") (pinfunction "~{CTS!/DIO7}_12") (pintype "bidirectional"))
    )
    (net (code "28") (name "/CTS0") (class "Default")
      (node (ref "J30") (pin "17") (pinfunction "17_17") (pintype "passive"))
      (node (ref "RN1") (pin "6") (pinfunction "6_6") (pintype "passive"))
    )
    (net (code "29") (name "/CTS1") (class "Default")
      (node (ref "J20") (pin "4") (pinfunction "4_4") (pintype "passive"))
      (node (ref "J33") (pin "26") (pinfunction "26_26") (pintype "passive"))
    )
    (net (code "30") (name "/CTS2") (class "Default")
      (node (ref "J21") (pin "4") (pinfunction "4_4") (pintype "passive"))
      (node (ref "J33") (pin "25") (pinfunction "25_25") (pintype "passive"))
    )
    (net (code "31") (name "/CTSJP1") (class "Default")
      (node (ref "J5") (pin "5") (pinfunction "S_5") (pintype "passive"))
      (node (ref "R167") (pin "1") (pinfunction "1_1") (pintype "passive"))
    )
    (net (code "32") (name "/C_DECAY{slash}NPCS1") (class "Default")
      (node (ref "D43") (pin "5") (pinfunction "5_cathode_5") (pintype "passive"))
      (node (ref "J17") (pin "9") (pinfunction "9_9") (pintype "passive"))
      (node (ref "R52") (pin "1") (pinfunction "1_1") (pintype "passive"))
      (node (ref "R93") (pin "1") (pinfunction "1_1") (pintype "passive"))
    )
    (net (code "33") (name "/C_EN{slash}IN1") (class "Default")
      (node (ref "D43") (pin "3") (pinfunction "2_cathode_3") (pintype "passive"))
      (node (ref "J17") (pin "7") (pinfunction "7_7") (pintype "passive"))
      (node (ref "R53") (pin "2") (pinfunction "2_2") (pintype "passive"))
    )
    (net (code "34") (name "/C_MISO") (class "Default")
      (node (ref "D44") (pin "1") (pinfunction "1_cathode_1") (pintype "passive"))
      (node (ref "J17") (pin "2") (pinfunction "2_2") (pintype "passive"))
      (node (ref "R55") (pin "2") (pinfunction "2_2") (pintype "passive"))
      (node (ref "R94") (pin "2") (pinfunction "2_2") (pintype "passive"))
    )
    (net (code "35") (name "/C_MOSI") (class "Default")
      (node (ref "D44") (pin "3") (pinfunction "2_cathode_3") (pintype "passive"))
      (node (ref "J17") (pin "1") (pinfunction "1_1") (pintype "passive"))
      (node (ref "R59") (pin "2") (pinfunction "2_2") (pintype "passive"))
      (node (ref "R96") (pin "2") (pinfunction "2_2") (pintype "passive"))
    )
    (net (code "36") (name "/C_PH{slash}IN2") (class "Default")
      (node (ref "D43") (pin "1") (pinfunction "1_cathode_1") (pintype "passive"))
      (node (ref "J17") (pin "8") (pinfunction "8_8") (pintype "passive"))
      (node (ref "R47") (pin "2") (pinfunction "2_2") (pintype "passive"))
    )
    (net (code "37") (name "/C_SCL") (class "Default")
      (node (ref "D42") (pin "1") (pinfunction "1_cathode_1") (pintype "passive"))
      (node (ref "J17") (pin "12") (pinfunction "12_12") (pintype "passive"))
      (node (ref "R42") (pin "2") (pinfunction "2_2") (pintype "passive"))
    )
    (net (code "38") (name "/C_SDA") (class "Default")
      (node (ref "D42") (pin "3") (pinfunction "2_cathode_3") (pintype "passive"))
      (node (ref "J17") (pin "11") (pinfunction "11_11") (pintype "passive"))
      (node (ref "R45") (pin "2") (pinfunction "2_2") (pintype "passive"))
    )
    (net (code "39") (name "/C_SPCK") (class "Default")
      (node (ref "D44") (pin "5") (pinfunction "5_cathode_5") (pintype "passive"))
      (node (ref "J17") (pin "3") (pinfunction "3_3") (pintype "passive"))
      (node (ref "R56") (pin "1") (pinfunction "1_1") (pintype "passive"))
    )
    (net (code "40") (name "/C_TOFF") (class "Default")
      (node (ref "D42") (pin "4") (pinfunction "3_cathode_4") (pintype "passive"))
      (node (ref "J17") (pin "10") (pinfunction "10_10") (pintype "passive"))
      (node (ref "R46") (pin "1") (pinfunction "1_1") (pintype "passive"))
      (node (ref "R92") (pin "1") (pinfunction "1_1") (pintype "passive"))
    )
    (net (code "41") (name "/C_nFAULT") (class "Default")
      (node (ref "D42") (pin "5") (pinfunction "5_cathode_5") (pintype "passive"))
      (node (ref "J17") (pin "13") (pinfunction "13_13") (pintype "passive"))
      (node (ref "R43") (pin "1") (pinfunction "1_1") (pintype "passive"))
    )
    (net (code "42") (name "/C_nSLEEP") (class "Default")
      (node (ref "D43") (pin "4") (pinfunction "3_cathode_4") (pintype "passive"))
      (node (ref "J17") (pin "6") (pinfunction "6_6") (pintype "passive"))
      (node (ref "R54") (pin "1") (pinfunction "1_1") (pintype "passive"))
    )
    (net (code "43") (name "/DIN") (class "Default")
      (node (ref "S1") (pin "1A") (pinfunction "COM1_1A") (pintype "passive"))
      (node (ref "S1") (pin "2A") (pinfunction "COM2_2A") (pintype "passive"))
      (node (ref "U8") (pin "3") (pinfunction "DIN/!CONFIG!/DIO14_3") (pintype "bidirectional"))
    )
    (net (code "44") (name "/DIO5") (class "Default")
      (node (ref "R30") (pin "1") (pinfunction "1_1") (pintype "passive"))
      (node (ref "U8") (pin "15") (pinfunction "ASSOCIATE/DIO5_15") (pintype "bidirectional"))
    )
    (net (code "45") (name "/DIO10") (class "Default")
      (node (ref "R28") (pin "1") (pinfunction "1_1") (pintype "passive"))
      (node (ref "U8") (pin "6") (pinfunction "RSSI_PWM/DIO10_6") (pintype "bidirectional"))
    )
    (net (code "46") (name "/DIR-") (class "Default")
      (node (ref "J8") (pin "6") (pinfunction "6_6") (pintype "passive"))
      (node (ref "Q8") (pin "3") (pinfunction "output(collector)_3") (pintype "passive"))
    )
    (net (code "47") (name "/DOUT") (class "Default")
      (node (ref "S1") (pin "3A") (pinfunction "COM3_3A") (pintype "passive"))
      (node (ref "S1") (pin "4A") (pinfunction "COM4_4A") (pintype "passive"))
      (node (ref "U8") (pin "2") (pinfunction "DOUT/DIO13_2") (pintype "bidirectional"))
    )
    (net (code "48") (name "/DTR") (class "Default")
      (node (ref "R83") (pin "1") (pinfunction "1_1") (pintype "passive"))
      (node (ref "U8") (pin "9") (pinfunction "~{DTR!/SLEEP_RQ/DIO8}_9") (pintype "bidirectional"))
    )
    (net (code "49") (name "/ENA-") (class "Default")
      (node (ref "J8") (pin "8") (pinfunction "8_8") (pintype "passive"))
      (node (ref "Q9") (pin "3") (pinfunction "output(collector)_3") (pintype "passive"))
    )
    (net (code "50") (name "/HSD_N") (class "Default")
      (node (ref "J1") (pin "2") (pinfunction "D-_2") (pintype "bidirectional"))
      (node (ref "J31") (pin "3") (pinfunction "3_3") (pintype "passive"))
      (node (ref "J31") (pin "4") (pinfunction "4_4") (pintype "passive"))
      (node (ref "U2") (pin "1") (pinfunction "I/O1_1") (pintype "bidirectional"))
      (node (ref "U2") (pin "6") (pinfunction "I/O1_6") (pintype "bidirectional"))
    )
    (net (code "51") (name "/HSD_P") (class "Default")
      (node (ref "J1") (pin "3") (pinfunction "D+_3") (pintype "bidirectional"))
      (node (ref "J31") (pin "1") (pinfunction "1_1") (pintype "passive"))
      (node (ref "J31") (pin "2") (pinfunction "2_2") (pintype "passive"))
      (node (ref "U2") (pin "3") (pinfunction "I/O2_3") (pintype "bidirectional"))
      (node (ref "U2") (pin "4") (pinfunction "I/O2_4") (pintype "bidirectional"))
    )
    (net (code "52") (name "/MCCDA") (class "Default")
      (node (ref "J28") (pin "3") (pinfunction "CMD_3") (pintype "bidirectional"))
      (node (ref "J32") (pin "6") (pinfunction "6_6") (pintype "passive"))
      (node (ref "R62") (pin "2") (pinfunction "2_2") (pintype "passive"))
      (node (ref "RN3") (pin "3") (pinfunction "3_3") (pintype "passive"))
    )
    (net (code "53") (name "/MCCK") (class "Default")
      (node (ref "J28") (pin "5") (pinfunction "CLK_5") (pintype "bidirectional"))
      (node (ref "J32") (pin "7") (pinfunction "7_7") (pintype "passive"))
      (node (ref "R86") (pin "2") (pinfunction "2_2") (pintype "passive"))
      (node (ref "RN3") (pin "4") (pinfunction "4_4") (pintype "passive"))
    )
    (net (code "54") (name "/MCDA0") (class "Default")
      (node (ref "J28") (pin "7") (pinfunction "DAT0_7") (pintype "bidirectional"))
      (node (ref "J31") (pin "33") (pinfunction "33_33") (pintype "passive"))
      (node (ref "R128") (pin "1") (pinfunction "1_1") (pintype "passive"))
      (node (ref "RN3") (pin "1") (pinfunction "1_1") (pintype "passive"))
    )
    (net (code "55") (name "/MCDA1") (class "Default")
      (node (ref "J28") (pin "8") (pinfunction "DAT1_8") (pintype "bidirectional"))
      (node (ref "J32") (pin "5") (pinfunction "5_5") (pintype "passive"))
      (node (ref "R73") (pin "2") (pinfunction "2_2") (pintype "passive"))
    )
    (net (code "56") (name "/MCDA2") (class "Default")
      (node (ref "J28") (pin "1") (pinfunction "DAT2_1") (pintype "bidirectional"))
      (node (ref "J32") (pin "10") (pinfunction "10_10") (pintype "passive"))
      (node (ref "R60") (pin "2") (pinfunction "2_2") (pintype "passive"))
    )
    (net (code "57") (name "/MCDA3") (class "Default")
      (node (ref "J28") (pin "2") (pinfunction "CD/DAT3_2") (pintype "bidirectional"))
      (node (ref "J32") (pin "8") (pinfunction "8_8") (pintype "passive"))
      (node (ref "R61") (pin "2") (pinfunction "2_2") (pintype "passive"))
      (node (ref "RN3") (pin "2") (pinfunction "2_2") (pintype "passive"))
    )
    (net (code "58") (name "/MCDETECT") (class "Default")
      (node (ref "J28") (pin "SWA") (pinfunction "A_SWA") (pintype "bidirectional"))
      (node (ref "J32") (pin "9") (pinfunction "9_9") (pintype "passive"))
      (node (ref "R65") (pin "2") (pinfunction "2_2") (pintype "passive"))
    )
    (net (code "59") (name "/PA0") (class "Default")
      (node (ref "J32") (pin "11") (pinfunction "11_11") (pintype "passive"))
      (node (ref "R33") (pin "1") (pinfunction "1_1") (pintype "passive"))
    )
    (net (code "60") (name "/PA1") (class "Default")
      (node (ref "J32") (pin "14") (pinfunction "14_14") (pintype "passive"))
      (node (ref "R31") (pin "1") (pinfunction "1_1") (pintype "passive"))
    )
    (net (code "61") (name "/PA2") (class "Default")
      (node (ref "J32") (pin "28") (pinfunction "28_28") (pintype "passive"))
      (node (ref "R17") (pin "1") (pinfunction "1_1") (pintype "passive"))
    )
    (net (code "62") (name "/PA6") (class "Default")
      (node (ref "J31") (pin "27") (pinfunction "27_27") (pintype "passive"))
      (node (ref "U8") (pin "19") (pinfunction "AD1/DIO1/SPI_!ATTN!/I2C_SCL_19") (pintype "bidirectional"))
    )
    (net (code "63") (name "/PA15") (class "Default")
      (node (ref "J20") (pin "7") (pinfunction "7_7") (pintype "passive"))
      (node (ref "J33") (pin "32") (pinfunction "32_32") (pintype "passive"))
    )
    (net (code "64") (name "/PA16{slash}LED3") (class "Default")
      (node (ref "J33") (pin "13") (pinfunction "13_13") (pintype "passive"))
      (node (ref "Q4") (pin "1") (pinfunction "input(base)_1") (pintype "passive"))
    )
    (net (code "65") (name "/PA18") (class "Default")
      (node (ref "J33") (pin "10") (pinfunction "10_10") (pintype "passive"))
      (node (ref "R96") (pin "1") (pinfunction "1_1") (pintype "passive"))
    )
    (net (code "66") (name "/PA19") (class "Default")
      (node (ref "J30") (pin "19") (pinfunction "19_19") (pintype "passive"))
      (node (ref "R2") (pin "1") (pinfunction "1_1") (pintype "passive"))
      (node (ref "U1") (pin "14") (pinfunction "C_14") (pintype "passive"))
    )
    (net (code "67") (name "/PA20") (class "Default")
      (node (ref "J30") (pin "18") (pinfunction "18_18") (pintype "passive"))
      (node (ref "R93") (pin "2") (pinfunction "2_2") (pintype "passive"))
    )
    (net (code "68") (name "/PA22") (class "Default")
      (node (ref "C58") (pin "2") (pinfunction "2_2") (pintype "passive"))
      (node (ref "J30") (pin "28") (pinfunction "28_28") (pintype "passive"))
      (node (ref "R50") (pin "1") (pinfunction "1_1") (pintype "passive"))
    )
    (net (code "69") (name "/PA23") (class "Default")
      (node (ref "J21") (pin "6") (pinfunction "6_6") (pintype "passive"))
      (node (ref "J33") (pin "29") (pinfunction "29_29") (pintype "passive"))
    )
    (net (code "70") (name "/PA29") (class "Default")
      (node (ref "D8") (pin "4") (pinfunction "3_cathode_4") (pintype "passive"))
      (node (ref "J3") (pin "5") (pinfunction "5_5") (pintype "passive"))
      (node (ref "J31") (pin "13") (pinfunction "13_13") (pintype "passive"))
    )
    (net (code "71") (name "/PB6") (class "Default")
      (node (ref "C72") (pin "1") (pinfunction "1_1") (pintype "passive"))
      (node (ref "J31") (pin "29") (pinfunction "29_29") (pintype "passive"))
      (node (ref "R67") (pin "1") (pinfunction "1_1") (pintype "passive"))
    )
    (net (code "72") (name "/PB6_IO") (class "Default")
      (node (ref "D24") (pin "2") (pinfunction "C2_2") (pintype "passive"))
      (node (ref "J29") (pin "3") (pinfunction "3_3") (pintype "passive"))
      (node (ref "R154") (pin "1") (pinfunction "1_1") (pintype "passive"))
      (node (ref "R75") (pin "2") (pinfunction "2_2") (pintype "passive"))
    )
    (net (code "73") (name "/PB12") (class "Default")
      (node (ref "J33") (pin "34") (pinfunction "34_34") (pintype "passive"))
      (node (ref "R15") (pin "1") (pinfunction "1_1") (pintype "passive"))
    )
    (net (code "74") (name "/PB13") (class "Default")
      (node (ref "J30") (pin "5") (pinfunction "5_5") (pintype "passive"))
      (node (ref "R168") (pin "1") (pinfunction "1_1") (pintype "passive"))
    )
    (net (code "75") (name "/PC0{slash}NTC") (class "Default")
      (node (ref "J3") (pin "1") (pinfunction "1_1") (pintype "passive"))
      (node (ref "J30") (pin "12") (pinfunction "12_12") (pintype "passive"))
    )
    (net (code "76") (name "/PC1") (class "Default")
      (node (ref "C59") (pin "2") (pinfunction "2_2") (pintype "passive"))
      (node (ref "J30") (pin "27") (pinfunction "27_27") (pintype "passive"))
      (node (ref "R51") (pin "1") (pinfunction "1_1") (pintype "passive"))
    )
    (net (code "77") (name "/PC2") (class "Default")
      (node (ref "J33") (pin "15") (pinfunction "15_15") (pintype "passive"))
      (node (ref "R98") (pin "1") (pinfunction "1_1") (pintype "passive"))
    )
    (net (code "78") (name "/PC3") (class "Default")
      (node (ref "J21") (pin "7") (pinfunction "7_7") (pintype "passive"))
      (node (ref "J33") (pin "30") (pinfunction "30_30") (pintype "passive"))
    )
    (net (code "79") (name "/PC4{slash}LED2") (class "Default")
      (node (ref "J33") (pin "12") (pinfunction "12_12") (pintype "passive"))
      (node (ref "Q3") (pin "1") (pinfunction "input(base)_1") (pintype "passive"))
    )
    (net (code "80") (name "/PC5{slash}LED1") (class "Default")
      (node (ref "J33") (pin "7") (pinfunction "7_7") (pintype "passive"))
      (node (ref "Q2") (pin "1") (pinfunction "input(base)_1") (pintype "passive"))
    )
    (net (code "81") (name "/PC6") (class "Default")
      (node (ref "J33") (pin "16") (pinfunction "16_16") (pintype "passive"))
      (node (ref "R38") (pin "2") (pinfunction "2_2") (pintype "passive"))
      (node (ref "R44") (pin "2") (pinfunction "2_2") (pintype "passive"))
    )
    (net (code "82") (name "/PC7{slash}LED4") (class "Default")
      (node (ref "J33") (pin "14") (pinfunction "14_14") (pintype "passive"))
      (node (ref "Q5") (pin "1") (pinfunction "input(base)_1") (pintype "passive"))
    )
    (net (code "83") (name "/PC8") (class "Default")
      (node (ref "J32") (pin "26") (pinfunction "26_26") (pintype "passive"))
      (node (ref "R18") (pin "2") (pinfunction "2_2") (pintype "passive"))
    )
    (net (code "84") (name "/PC9") (class "Default")
      (node (ref "J20") (pin "6") (pinfunction "6_6") (pintype "passive"))
      (node (ref "J32") (pin "27") (pinfunction "27_27") (pintype "passive"))
    )
    (net (code "85") (name "/PC10") (class "Default")
      (node (ref "J32") (pin "29") (pinfunction "29_29") (pintype "passive"))
      (node (ref "R92") (pin "2") (pinfunction "2_2") (pintype "passive"))
    )
    (net (code "86") (name "/PC11") (class "Default")
      (node (ref "J32") (pin "15") (pinfunction "15_15") (pintype "passive"))
      (node (ref "R90") (pin "2") (pinfunction "2_2") (pintype "passive"))
    )
    (net (code "87") (name "/PC12") (class "Default")
      (node (ref "J30") (pin "11") (pinfunction "11_11") (pintype "passive"))
    )
    (net (code "88") (name "/PC13") (class "Default")
      (node (ref "J33") (pin "9") (pinfunction "9_9") (pintype "passive"))
      (node (ref "R34") (pin "1") (pinfunction "1_1") (pintype "passive"))
      (node (ref "U1") (pin "10") (pinfunction "C_10") (pintype "passive"))
    )
    (net (code "89") (name "/PC14") (class "Default")
      (node (ref "J32") (pin "25") (pinfunction "25_25") (pintype "passive"))
      (node (ref "R54") (pin "2") (pinfunction "2_2") (pintype "passive"))
    )
    (net (code "90") (name "/PC15") (class "Default")
      (node (ref "J30") (pin "13") (pinfunction "13_13") (pintype "passive"))
      (node (ref "R1") (pin "1") (pinfunction "1_1") (pintype "passive"))
      (node (ref "U1") (pin "16") (pinfunction "C_16") (pintype "passive"))
    )
    (net (code "91") (name "/PC16") (class "Default")
      (node (ref "J32") (pin "17") (pinfunction "17_17") (pintype "passive"))
      (node (ref "R23") (pin "2") (pinfunction "2_2") (pintype "passive"))
    )
    (net (code "92") (name "/PC17") (class "Default")
      (node (ref "J32") (pin "13") (pinfunction "13_13") (pintype "passive"))
      (node (ref "R91") (pin "2") (pinfunction "2_2") (pintype "passive"))
    )
    (net (code "93") (name "/PC18") (class "Default")
      (node (ref "C73") (pin "1") (pinfunction "1_1") (pintype "passive"))
      (node (ref "J31") (pin "30") (pinfunction "30_30") (pintype "passive"))
      (node (ref "R68") (pin "1") (pinfunction "1_1") (pintype "passive"))
    )
    (net (code "94") (name "/PC18_IO") (class "Default")
      (node (ref "D24") (pin "1") (pinfunction "C1_1") (pintype "passive"))
      (node (ref "J29") (pin "4") (pinfunction "4_4") (pintype "passive"))
      (node (ref "R153") (pin "1") (pinfunction "1_1") (pintype "passive"))
      (node (ref "R76") (pin "2") (pinfunction "2_2") (pintype "passive"))
    )
    (net (code "95") (name "/PC19") (class "Default")
      (node (ref "J31") (pin "28") (pinfunction "28_28") (pintype "passive"))
      (node (ref "U8") (pin "20") (pinfunction "AD0/DIO0_20") (pintype "bidirectional"))
    )
    (net (code "96") (name "/PC20") (class "Default")
      (node (ref "C76") (pin "1") (pinfunction "1_1") (pintype "passive"))
      (node (ref "J32") (pin "3") (pinfunction "3_3") (pintype "passive"))
      (node (ref "R71") (pin "1") (pinfunction "1_1") (pintype "passive"))
    )
    (net (code "97") (name "/PC20_IO") (class "Default")
      (node (ref "D26") (pin "2") (pinfunction "C2_2") (pintype "passive"))
      (node (ref "J29") (pin "7") (pinfunction "7_7") (pintype "passive"))
      (node (ref "R150") (pin "1") (pinfunction "1_1") (pintype "passive"))
      (node (ref "R79") (pin "2") (pinfunction "2_2") (pintype "passive"))
    )
    (net (code "98") (name "/PC21") (class "Default")
      (node (ref "J31") (pin "15") (pinfunction "15_15") (pintype "passive"))
      (node (ref "R7") (pin "2") (pinfunction "2_2") (pintype "passive"))
    )
    (net (code "99") (name "/PC22") (class "Default")
      (node (ref "J31") (pin "16") (pinfunction "16_16") (pintype "passive"))
      (node (ref "R47") (pin "1") (pinfunction "1_1") (pintype "passive"))
    )
    (net (code "100") (name "/PC23") (class "Default")
      (node (ref "C70") (pin "1") (pinfunction "1_1") (pintype "passive"))
      (node (ref "J31") (pin "31") (pinfunction "31_31") (pintype "passive"))
      (node (ref "R58") (pin "1") (pinfunction "1_1") (pintype "passive"))
    )
    (net (code "101") (name "/PC23_IO") (class "Default")
      (node (ref "D23") (pin "2") (pinfunction "C2_2") (pintype "passive"))
      (node (ref "J29") (pin "1") (pinfunction "1_1") (pintype "passive"))
      (node (ref "R57") (pin "2") (pinfunction "2_2") (pintype "passive"))
      (node (ref "R64") (pin "1") (pinfunction "1_1") (pintype "passive"))
    )
    (net (code "102") (name "/PC29") (class "Default")
      (node (ref "J30") (pin "10") (pinfunction "10_10") (pintype "passive"))
    )
    (net (code "103") (name "/PC30") (class "Default")
      (node (ref "J33") (pin "8") (pinfunction "8_8") (pintype "passive"))
      (node (ref "R29") (pin "1") (pinfunction "1_1") (pintype "passive"))
      (node (ref "U1") (pin "12") (pinfunction "C_12") (pintype "passive"))
    )
    (net (code "104") (name "/PC31") (class "Default")
      (node (ref "D7") (pin "1") (pinfunction "1_cathode_1") (pintype "passive"))
      (node (ref "J3") (pin "6") (pinfunction "6_6") (pintype "passive"))
      (node (ref "J30") (pin "14") (pinfunction "14_14") (pintype "passive"))
    )
    (net (code "105") (name "/PD0") (class "Default")
      (node (ref "J30") (pin "6") (pinfunction "6_6") (pintype "passive"))
      (node (ref "Q9") (pin "1") (pinfunction "input(base)_1") (pintype "passive"))
    )
    (net (code "106") (name "/PD1") (class "Default")
      (node (ref "J31") (pin "17") (pinfunction "17_17") (pintype "passive"))
      (node (ref "R14") (pin "2") (pinfunction "2_2") (pintype "passive"))
    )
    (net (code "107") (name "/PD2") (class "Default")
      (node (ref "D8") (pin "3") (pinfunction "2_cathode_3") (pintype "passive"))
      (node (ref "J3") (pin "4") (pinfunction "4_4") (pintype "passive"))
      (node (ref "J31") (pin "14") (pinfunction "14_14") (pintype "passive"))
    )
    (net (code "108") (name "/PD3") (class "Default")
      (node (ref "J31") (pin "20") (pinfunction "20_20") (pintype "passive"))
      (node (ref "R89") (pin "2") (pinfunction "2_2") (pintype "passive"))
    )
    (net (code "109") (name "/PD4") (class "Default")
      (node (ref "C71") (pin "1") (pinfunction "1_1") (pintype "passive"))
      (node (ref "J31") (pin "32") (pinfunction "32_32") (pintype "passive"))
      (node (ref "R66") (pin "1") (pinfunction "1_1") (pintype "passive"))
    )
    (net (code "110") (name "/PD4_IO") (class "Default")
      (node (ref "D23") (pin "1") (pinfunction "C1_1") (pintype "passive"))
      (node (ref "J29") (pin "2") (pinfunction "2_2") (pintype "passive"))
      (node (ref "R148") (pin "1") (pinfunction "1_1") (pintype "passive"))
      (node (ref "R74") (pin "2") (pinfunction "2_2") (pintype "passive"))
    )
    (net (code "111") (name "/PD5") (class "Default")
      (node (ref "J31") (pin "26") (pinfunction "26_26") (pintype "passive"))
      (node (ref "U8") (pin "5") (pinfunction "~{RESET}_5") (pintype "input"))
    )
    (net (code "112") (name "/PD6") (class "Default")
      (node (ref "J31") (pin "25") (pinfunction "25_25") (pintype "passive"))
      (node (ref "Q1") (pin "1") (pinfunction "input(base)_1") (pintype "passive"))
    )
    (net (code "113") (name "/PD7") (class "Default")
      (node (ref "J31") (pin "18") (pinfunction "18_18") (pintype "passive"))
      (node (ref "Q8") (pin "1") (pinfunction "input(base)_1") (pintype "passive"))
    )
    (net (code "114") (name "/PD8") (class "Default")
      (node (ref "C74") (pin "1") (pinfunction "1_1") (pintype "passive"))
      (node (ref "J32") (pin "1") (pinfunction "1_1") (pintype "passive"))
      (node (ref "R69") (pin "1") (pinfunction "1_1") (pintype "passive"))
    )
    (net (code "115") (name "/PD8_IO") (class "Default")
      (node (ref "D25") (pin "2") (pinfunction "C2_2") (pintype "passive"))
      (node (ref "J29") (pin "5") (pinfunction "5_5") (pintype "passive"))
      (node (ref "R152") (pin "1") (pinfunction "1_1") (pintype "passive"))
      (node (ref "R77") (pin "2") (pinfunction "2_2") (pintype "passive"))
    )
    (net (code "116") (name "/PD9") (class "Default")
      (node (ref "C75") (pin "1") (pinfunction "1_1") (pintype "passive"))
      (node (ref "J32") (pin "2") (pinfunction "2_2") (pintype "passive"))
      (node (ref "R70") (pin "1") (pinfunction "1_1") (pintype "passive"))
    )
    (net (code "117") (name "/PD9_IO") (class "Default")
      (node (ref "D25") (pin "1") (pinfunction "C1_1") (pintype "passive"))
      (node (ref "J29") (pin "6") (pinfunction "6_6") (pintype "passive"))
      (node (ref "R151") (pin "1") (pinfunction "1_1") (pintype "passive"))
      (node (ref "R78") (pin "2") (pinfunction "2_2") (pintype "passive"))
    )
    (net (code "118") (name "/PD11") (class "Default")
      (node (ref "J32") (pin "12") (pinfunction "12_12") (pintype "passive"))
      (node (ref "R37") (pin "2") (pinfunction "2_2") (pintype "passive"))
    )
    (net (code "119") (name "/PD13") (class "Default")
      (node (ref "J32") (pin "18") (pinfunction "18_18") (pintype "passive"))
      (node (ref "R27") (pin "2") (pinfunction "2_2") (pintype "passive"))
    )
    (net (code "120") (name "/PD14") (class "Default")
      (node (ref "J32") (pin "31") (pinfunction "31_31") (pintype "passive"))
      (node (ref "R43") (pin "2") (pinfunction "2_2") (pintype "passive"))
    )
    (net (code "121") (name "/PD17") (class "Default")
      (node (ref "J32") (pin "32") (pinfunction "32_32") (pintype "passive"))
      (node (ref "R46") (pin "2") (pinfunction "2_2") (pintype "passive"))
    )
    (net (code "122") (name "/PD23") (class "Default")
      (node (ref "J33") (pin "31") (pinfunction "31_31") (pintype "passive"))
      (node (ref "R53") (pin "1") (pinfunction "1_1") (pintype "passive"))
    )
    (net (code "123") (name "/PD24") (class "Default")
      (node (ref "J33") (pin "33") (pinfunction "33_33") (pintype "passive"))
      (node (ref "R170") (pin "1") (pinfunction "1_1") (pintype "passive"))
    )
    (net (code "124") (name "/PD29") (class "Default")
      (node (ref "C77") (pin "1") (pinfunction "1_1") (pintype "passive"))
      (node (ref "J32") (pin "4") (pinfunction "4_4") (pintype "passive"))
      (node (ref "R72") (pin "1") (pinfunction "1_1") (pintype "passive"))
    )
    (net (code "125") (name "/PD29_IO") (class "Default")
      (node (ref "D26") (pin "1") (pinfunction "C1_1") (pintype "passive"))
      (node (ref "J29") (pin "8") (pinfunction "8_8") (pintype "passive"))
      (node (ref "R149") (pin "1") (pinfunction "1_1") (pintype "passive"))
      (node (ref "R80") (pin "2") (pinfunction "2_2") (pintype "passive"))
    )
    (net (code "126") (name "/PD30") (class "Default")
      (node (ref "C56") (pin "2") (pinfunction "2_2") (pintype "passive"))
      (node (ref "J30") (pin "25") (pinfunction "25_25") (pintype "passive"))
      (node (ref "R48") (pin "1") (pinfunction "1_1") (pintype "passive"))
    )
    (net (code "127") (name "/PE0") (class "Default")
      (node (ref "J30") (pin "2") (pinfunction "2_2") (pintype "passive"))
      (node (ref "R84") (pin "1") (pinfunction "1_1") (pintype "passive"))
    )
    (net (code "128") (name "/PE1") (class "Default")
      (node (ref "D7") (pin "5") (pinfunction "5_cathode_5") (pintype "passive"))
      (node (ref "J3") (pin "7") (pinfunction "7_7") (pintype "passive"))
      (node (ref "J30") (pin "1") (pinfunction "1_1") (pintype "passive"))
    )
    (net (code "129") (name "/PE2") (class "Default")
      (node (ref "J30") (pin "7") (pinfunction "7_7") (pintype "passive"))
      (node (ref "R87") (pin "2") (pinfunction "2_2") (pintype "passive"))
    )
    (net (code "130") (name "/PE3") (class "Default")
      (node (ref "J30") (pin "8") (pinfunction "8_8") (pintype "passive"))
      (node (ref "R95") (pin "1") (pinfunction "1_1") (pintype "passive"))
    )
    (net (code "131") (name "/PE4") (class "Default")
      (node (ref "C57") (pin "2") (pinfunction "2_2") (pintype "passive"))
      (node (ref "J30") (pin "26") (pinfunction "26_26") (pintype "passive"))
      (node (ref "R49") (pin "1") (pinfunction "1_1") (pintype "passive"))
    )
    (net (code "132") (name "/PE5") (class "Default")
      (node (ref "J33") (pin "11") (pinfunction "11_11") (pintype "passive"))
      (node (ref "R94") (pin "1") (pinfunction "1_1") (pintype "passive"))
    )
    (net (code "133") (name "/PUL-") (class "Default")
      (node (ref "J8") (pin "4") (pinfunction "4_4") (pintype "passive"))
      (node (ref "Q1") (pin "3") (pinfunction "output(collector)_3") (pintype "passive"))
    )
    (net (code "134") (name "/QCS") (class "Default")
      (node (ref "J30") (pin "34") (pinfunction "34_34") (pintype "passive"))
      (node (ref "R101") (pin "1") (pinfunction "1_1") (pintype "passive"))
      (node (ref "U7") (pin "1") (pinfunction "~{CS}_1") (pintype "input"))
    )
    (net (code "135") (name "/QIO0") (class "Default")
      (node (ref "J30") (pin "31") (pinfunction "31_31") (pintype "passive"))
      (node (ref "U7") (pin "5") (pinfunction "SI/SIO0_5") (pintype "bidirectional"))
    )
    (net (code "136") (name "/QIO1") (class "Default")
      (node (ref "J30") (pin "33") (pinfunction "33_33") (pintype "passive"))
      (node (ref "U7") (pin "2") (pinfunction "SO/SIO1_2") (pintype "output"))
    )
    (net (code "137") (name "/QIO2") (class "Default")
      (node (ref "C28") (pin "2") (pinfunction "2_2") (pintype "passive"))
      (node (ref "J30") (pin "32") (pinfunction "32_32") (pintype "passive"))
      (node (ref "R26") (pin "1") (pinfunction "1_1") (pintype "passive"))
      (node (ref "U7") (pin "3") (pinfunction "~{WP}_3") (pintype "input"))
    )
    (net (code "138") (name "/QIO3") (class "Default")
      (node (ref "J30") (pin "30") (pinfunction "30_30") (pintype "passive"))
      (node (ref "R25") (pin "1") (pinfunction "1_1") (pintype "passive"))
      (node (ref "U7") (pin "7") (pinfunction "~{HOLD}_7") (pintype "input"))
    )
    (net (code "139") (name "/QSCK") (class "Default")
      (node (ref "J30") (pin "29") (pinfunction "29_29") (pintype "passive"))
      (node (ref "U7") (pin "6") (pinfunction "SCLK_6") (pintype "input"))
    )
    (net (code "140") (name "/RN1SJ1") (class "Default")
      (node (ref "RN1") (pin "2") (pinfunction "2_2") (pintype "passive"))
      (node (ref "S1") (pin "2B") (pinfunction "NO2_2B") (pintype "passive"))
    )
    (net (code "141") (name "/RN1SJ2") (class "Default")
      (node (ref "RN1") (pin "1") (pinfunction "1_1") (pintype "passive"))
      (node (ref "S1") (pin "3B") (pinfunction "NO3_3B") (pintype "passive"))
    )
    (net (code "142") (name "/RTS") (class "Default")
      (node (ref "RN1") (pin "3") (pinfunction "3_3") (pintype "passive"))
      (node (ref "U8") (pin "16") (pinfunction "~{RTS!/DIO6}_16") (pintype "bidirectional"))
    )
    (net (code "143") (name "/RTS0") (class "Default")
      (node (ref "J30") (pin "20") (pinfunction "20_20") (pintype "passive"))
      (node (ref "RN1") (pin "5") (pinfunction "5_5") (pintype "passive"))
    )
    (net (code "144") (name "/RTS1") (class "Default")
      (node (ref "J20") (pin "5") (pinfunction "5_5") (pintype "passive"))
      (node (ref "J33") (pin "28") (pinfunction "28_28") (pintype "passive"))
    )
    (net (code "145") (name "/RTS2") (class "Default")
      (node (ref "J21") (pin "5") (pinfunction "5_5") (pintype "passive"))
      (node (ref "J33") (pin "27") (pinfunction "27_27") (pintype "passive"))
    )
    (net (code "146") (name "/RTSJP1") (class "Default")
      (node (ref "J5") (pin "6") (pinfunction "S_6") (pintype "passive"))
      (node (ref "R169") (pin "1") (pinfunction "1_1") (pintype "passive"))
    )
    (net (code "147") (name "/RX") (class "Default")
      (node (ref "J49") (pin "3") (pinfunction "S_3") (pintype "passive"))
      (node (ref "S1") (pin "4B") (pinfunction "NO4_4B") (pintype "passive"))
    )
    (net (code "148") (name "/RXD0") (class "Default")
      (node (ref "J30") (pin "15") (pinfunction "15_15") (pintype "passive"))
      (node (ref "RN1") (pin "8") (pinfunction "8_8") (pintype "passive"))
    )
    (net (code "149") (name "/RXD1") (class "Default")
      (node (ref "J20") (pin "3") (pinfunction "3_3") (pintype "passive"))
      (node (ref "J33") (pin "20") (pinfunction "20_20") (pintype "passive"))
    )
    (net (code "150") (name "/RXD2") (class "Default")
      (node (ref "J21") (pin "3") (pinfunction "3_3") (pintype "passive"))
      (node (ref "J33") (pin "19") (pinfunction "19_19") (pintype "passive"))
    )
    (net (code "151") (name "/RXJP1") (class "Default")
      (node (ref "J5") (pin "3") (pinfunction "S_3") (pintype "passive"))
      (node (ref "R165") (pin "1") (pinfunction "1_1") (pintype "passive"))
    )
    (net (code "152") (name "/SCL0{slash}STAT1") (class "Default")
      (node (ref "D7") (pin "4") (pinfunction "3_cathode_4") (pintype "passive"))
      (node (ref "J3") (pin "9") (pinfunction "9_9") (pintype "passive"))
      (node (ref "J32") (pin "19") (pinfunction "19_19") (pintype "passive"))
    )
    (net (code "153") (name "/SCL2") (class "Default")
      (node (ref "D8") (pin "1") (pinfunction "1_cathode_1") (pintype "passive"))
      (node (ref "J3") (pin "3") (pinfunction "3_3") (pintype "passive"))
      (node (ref "J33") (pin "6") (pinfunction "6_6") (pintype "passive"))
      (node (ref "R22") (pin "1") (pinfunction "1_1") (pintype "passive"))
      (node (ref "R4") (pin "1") (pinfunction "1_1") (pintype "passive"))
      (node (ref "R42") (pin "1") (pinfunction "1_1") (pintype "passive"))
    )
    (net (code "154") (name "/SDA0{slash}STAT2") (class "Default")
      (node (ref "D7") (pin "3") (pinfunction "2_cathode_3") (pintype "passive"))
      (node (ref "J3") (pin "8") (pinfunction "8_8") (pintype "passive"))
      (node (ref "J32") (pin "20") (pinfunction "20_20") (pintype "passive"))
    )
    (net (code "155") (name "/SDA2") (class "Default")
      (node (ref "D8") (pin "5") (pinfunction "5_cathode_5") (pintype "passive"))
      (node (ref "J3") (pin "2") (pinfunction "2_2") (pintype "passive"))
      (node (ref "J33") (pin "5") (pinfunction "5_5") (pintype "passive"))
      (node (ref "R12") (pin "1") (pinfunction "1_1") (pintype "passive"))
      (node (ref "R24") (pin "1") (pinfunction "1_1") (pintype "passive"))
      (node (ref "R45") (pin "1") (pinfunction "1_1") (pintype "passive"))
    )
    (net (code "156") (name "/SPI0_MISO") (class "Default")
      (node (ref "J33") (pin "4") (pinfunction "4_4") (pintype "passive"))
      (node (ref "RN3") (pin "8") (pinfunction "8_8") (pintype "passive"))
    )
    (net (code "157") (name "/SPI0_MOSI") (class "Default")
      (node (ref "J33") (pin "2") (pinfunction "2_2") (pintype "passive"))
      (node (ref "RN3") (pin "6") (pinfunction "6_6") (pintype "passive"))
    )
    (net (code "158") (name "/SPI0_NPCS1") (class "Default")
      (node (ref "J33") (pin "3") (pinfunction "3_3") (pintype "passive"))
      (node (ref "RN3") (pin "7") (pinfunction "7_7") (pintype "passive"))
    )
    (net (code "159") (name "/SPI0_SPCK") (class "Default")
      (node (ref "J33") (pin "1") (pinfunction "1_1") (pintype "passive"))
      (node (ref "RN3") (pin "5") (pinfunction "5_5") (pintype "passive"))
    )
    (net (code "160") (name "/SPI1_MISO") (class "Default")
      (node (ref "J30") (pin "3") (pinfunction "3_3") (pintype "passive"))
      (node (ref "R19") (pin "1") (pinfunction "1_1") (pintype "passive"))
      (node (ref "R39") (pin "1") (pinfunction "1_1") (pintype "passive"))
      (node (ref "R55") (pin "1") (pinfunction "1_1") (pintype "passive"))
    )
    (net (code "161") (name "/SPI1_MOSI") (class "Default")
      (node (ref "J30") (pin "4") (pinfunction "4_4") (pintype "passive"))
      (node (ref "R21") (pin "1") (pinfunction "1_1") (pintype "passive"))
      (node (ref "R41") (pin "1") (pinfunction "1_1") (pintype "passive"))
      (node (ref "R59") (pin "1") (pinfunction "1_1") (pintype "passive"))
    )
    (net (code "162") (name "/SPI1_NPCS0") (class "Default")
      (node (ref "J31") (pin "19") (pinfunction "19_19") (pintype "passive"))
      (node (ref "R16") (pin "2") (pinfunction "2_2") (pintype "passive"))
    )
    (net (code "163") (name "/SPI1_NPCS1") (class "Default")
      (node (ref "J32") (pin "30") (pinfunction "30_30") (pintype "passive"))
      (node (ref "R52") (pin "2") (pinfunction "2_2") (pintype "passive"))
    )
    (net (code "164") (name "/SPI1_NPCS2") (class "Default")
      (node (ref "J32") (pin "16") (pinfunction "16_16") (pintype "passive"))
      (node (ref "R32") (pin "2") (pinfunction "2_2") (pintype "passive"))
    )
    (net (code "165") (name "/SPI1_SPCK") (class "Default")
      (node (ref "J31") (pin "34") (pinfunction "34_34") (pintype "passive"))
      (node (ref "R20") (pin "2") (pinfunction "2_2") (pintype "passive"))
      (node (ref "R40") (pin "2") (pinfunction "2_2") (pintype "passive"))
      (node (ref "R56") (pin "2") (pinfunction "2_2") (pintype "passive"))
    )
    (net (code "166") (name "/TX") (class "Default")
      (node (ref "J49") (pin "2") (pinfunction "S_2") (pintype "passive"))
      (node (ref "S1") (pin "1B") (pinfunction "NO1_1B") (pintype "passive"))
    )
    (net (code "167") (name "/TXD0") (class "Default")
      (node (ref "J30") (pin "16") (pinfunction "16_16") (pintype "passive"))
      (node (ref "RN1") (pin "7") (pinfunction "7_7") (pintype "passive"))
    )
    (net (code "168") (name "/TXD1") (class "Default")
      (node (ref "J20") (pin "2") (pinfunction "2_2") (pintype "passive"))
      (node (ref "J33") (pin "18") (pinfunction "18_18") (pintype "passive"))
    )
    (net (code "169") (name "/TXD2") (class "Default")
      (node (ref "J21") (pin "2") (pinfunction "2_2") (pintype "passive"))
      (node (ref "J33") (pin "17") (pinfunction "17_17") (pintype "passive"))
    )
    (net (code "170") (name "/TXJP1") (class "Default")
      (node (ref "J5") (pin "2") (pinfunction "S_2") (pintype "passive"))
      (node (ref "R163") (pin "1") (pinfunction "1_1") (pintype "passive"))
    )
    (net (code "171") (name "/URXD1") (class "Default")
      (node (ref "J32") (pin "33") (pinfunction "33_33") (pintype "passive"))
      (node (ref "R166") (pin "1") (pinfunction "1_1") (pintype "passive"))
    )
    (net (code "172") (name "/UTXD1") (class "Default")
      (node (ref "J32") (pin "34") (pinfunction "34_34") (pintype "passive"))
      (node (ref "R164") (pin "1") (pinfunction "1_1") (pintype "passive"))
    )
    (net (code "173") (name "/VBUS") (class "Default")
      (node (ref "J1") (pin "1") (pinfunction "VDD_1") (pintype "power_in"))
      (node (ref "U2") (pin "5") (pinfunction "VBUS_5") (pintype "power_in"))
    )
    (net (code "174") (name "/VCC") (class "Default")
      (node (ref "C34") (pin "2") (pinfunction "2_2") (pintype "passive"))
      (node (ref "L17") (pin "1") (pinfunction "1_1") (pintype "passive"))
      (node (ref "U8") (pin "1") (pinfunction "VCC_1") (pintype "power_in"))
    )
    (net (code "175") (name "/VDD_UART1") (class "Default")
      (node (ref "C68") (pin "1") (pinfunction "1_1") (pintype "passive"))
      (node (ref "J20") (pin "1") (pinfunction "1_1") (pintype "passive"))
      (node (ref "L2") (pin "1") (pinfunction "1_1") (pintype "passive"))
      (node (ref "L4") (pin "1") (pinfunction "1_1") (pintype "passive"))
      (node (ref "L6") (pin "1") (pinfunction "1_1") (pintype "passive"))
    )
    (net (code "176") (name "/VDD_UART2") (class "Default")
      (node (ref "C69") (pin "2") (pinfunction "2_2") (pintype "passive"))
      (node (ref "J21") (pin "1") (pinfunction "1_1") (pintype "passive"))
      (node (ref "L3") (pin "2") (pinfunction "2_2") (pintype "passive"))
      (node (ref "L5") (pin "2") (pinfunction "2_2") (pintype "passive"))
      (node (ref "L7") (pin "2") (pinfunction "2_2") (pintype "passive"))
    )
    (net (code "177") (name "GND") (class "Default")
      (node (ref "C113") (pin "1") (pinfunction "1_1") (pintype "passive"))
      (node (ref "C146") (pin "2") (pinfunction "2_2") (pintype "passive"))
      (node (ref "C147") (pin "2") (pinfunction "2_2") (pintype "passive"))
      (node (ref "C148") (pin "2") (pinfunction "2_2") (pintype "passive"))
      (node (ref "C149") (pin "2") (pinfunction "2_2") (pintype "passive"))
      (node (ref "C150") (pin "1") (pinfunction "1_1") (pintype "passive"))
      (node (ref "C155") (pin "1") (pinfunction "1_1") (pintype "passive"))
      (node (ref "C190") (pin "1") (pinfunction "1_1") (pintype "passive"))
      (node (ref "C28") (pin "1") (pinfunction "1_1") (pintype "passive"))
      (node (ref "C33") (pin "1") (pinfunction "1_1") (pintype "passive"))
      (node (ref "C34") (pin "1") (pinfunction "1_1") (pintype "passive"))
      (node (ref "C35") (pin "1") (pinfunction "1_1") (pintype "passive"))
      (node (ref "C56") (pin "1") (pinfunction "1_1") (pintype "passive"))
      (node (ref "C57") (pin "1") (pinfunction "1_1") (pintype "passive"))
      (node (ref "C58") (pin "1") (pinfunction "1_1") (pintype "passive"))
      (node (ref "C59") (pin "1") (pinfunction "1_1") (pintype "passive"))
      (node (ref "C61") (pin "1") (pinfunction "1_1") (pintype "passive"))
      (node (ref "C63") (pin "1") (pinfunction "1_1") (pintype "passive"))
      (node (ref "C68") (pin "2") (pinfunction "2_2") (pintype "passive"))
      (node (ref "C69") (pin "1") (pinfunction "1_1") (pintype "passive"))
      (node (ref "C70") (pin "2") (pinfunction "2_2") (pintype "passive"))
      (node (ref "C71") (pin "2") (pinfunction "2_2") (pintype "passive"))
      (node (ref "C72") (pin "2") (pinfunction "2_2") (pintype "passive"))
      (node (ref "C73") (pin "2") (pinfunction "2_2") (pintype "passive"))
      (node (ref "C74") (pin "2") (pinfunction "2_2") (pintype "passive"))
      (node (ref "C75") (pin "2") (pinfunction "2_2") (pintype "passive"))
      (node (ref "C76") (pin "2") (pinfunction "2_2") (pintype "passive"))
      (node (ref "C77") (pin "2") (pinfunction "2_2") (pintype "passive"))
      (node (ref "C78") (pin "1") (pinfunction "1_1") (pintype "passive"))
      (node (ref "C86") (pin "1") (pinfunction "1_1") (pintype "passive"))
      (node (ref "D10") (pin "2") (pinfunction "common_anode_2") (pintype "passive"))
      (node (ref "D11") (pin "4") (pinfunction "3_cathode_4") (pintype "passive"))
      (node (ref "D12") (pin "2") (pinfunction "common_anode_2") (pintype "passive"))
      (node (ref "D13") (pin "2") (pinfunction "common_anode_2") (pintype "passive"))
      (node (ref "D14") (pin "4") (pinfunction "3_cathode_4") (pintype "passive"))
      (node (ref "D15") (pin "1") (pinfunction "1_1") (pintype "passive"))
      (node (ref "D16") (pin "1") (pinfunction "1_1") (pintype "passive"))
      (node (ref "D17") (pin "1") (pinfunction "1_1") (pintype "passive"))
      (node (ref "D18") (pin "1") (pinfunction "1_1") (pintype "passive"))
      (node (ref "D19") (pin "1") (pinfunction "1_1") (pintype "passive"))
      (node (ref "D2") (pin "2") (pinfunction "2_2") (pintype "passive"))
      (node (ref "D20") (pin "1") (pinfunction "1_1") (pintype "passive"))
      (node (ref "D21") (pin "1") (pinfunction "1_1") (pintype "passive"))
      (node (ref "D22") (pin "1") (pinfunction "1_1") (pintype "passive"))
      (node (ref "D23") (pin "3") (pinfunction "CA_3") (pintype "passive"))
      (node (ref "D24") (pin "3") (pinfunction "CA_3") (pintype "passive"))
      (node (ref "D25") (pin "3") (pinfunction "CA_3") (pintype "passive"))
      (node (ref "D26") (pin "3") (pinfunction "CA_3") (pintype "passive"))
      (node (ref "D3") (pin "1") (pinfunction "1_1") (pintype "passive"))
      (node (ref "D31") (pin "1") (pinfunction "1_1") (pintype "passive"))
      (node (ref "D33") (pin "1") (pinfunction "1_1") (pintype "passive"))
      (node (ref "D35") (pin "1") (pinfunction "1_1") (pintype "passive"))
      (node (ref "D37") (pin "1") (pinfunction "1_1") (pintype "passive"))
      (node (ref "D4") (pin "1") (pinfunction "1_1") (pintype "passive"))
      (node (ref "D42") (pin "2") (pinfunction "common_anode_2") (pintype "passive"))
      (node (ref "D43") (pin "2") (pinfunction "common_anode_2") (pintype "passive"))
      (node (ref "D44") (pin "4") (pinfunction "3_cathode_4") (pintype "passive"))
      (node (ref "D46") (pin "2") (pinfunction "2_2") (pintype "passive"))
      (node (ref "D48") (pin "2") (pinfunction "2_2") (pintype "passive"))
      (node (ref "D5") (pin "1") (pinfunction "1_1") (pintype "passive"))
      (node (ref "D50") (pin "2") (pinfunction "2_2") (pintype "passive"))
      (node (ref "D6") (pin "1") (pinfunction "1_1") (pintype "passive"))
      (node (ref "D7") (pin "2") (pinfunction "common_anode_2") (pintype "passive"))
      (node (ref "D8") (pin "2") (pinfunction "common_anode_2") (pintype "passive"))
      (node (ref "D9") (pin "2") (pinfunction "common_anode_2") (pintype "passive"))
      (node (ref "GND1") (pin "1") (pinfunction "VSS_1") (pintype "passive"))
      (node (ref "GND2") (pin "1") (pinfunction "VSS_1") (pintype "passive"))
      (node (ref "GND3") (pin "1") (pinfunction "VSS_1") (pintype "passive"))
      (node (ref "GND4") (pin "1") (pinfunction "VSS_1") (pintype "passive"))
      (node (ref "J1") (pin "5") (pinfunction "GND_5") (pintype "power_in"))
      (node (ref "J15") (pin "4") (pinfunction "4_4") (pintype "passive"))
      (node (ref "J15") (pin "5") (pinfunction "5_5") (pintype "passive"))
      (node (ref "J15") (pin "M1") (pinfunction "M1_M1") (pintype "passive"))
      (node (ref "J15") (pin "M2") (pinfunction "M2_M2") (pintype "passive"))
      (node (ref "J16") (pin "4") (pinfunction "4_4") (pintype "passive"))
      (node (ref "J16") (pin "5") (pinfunction "5_5") (pintype "passive"))
      (node (ref "J16") (pin "M1") (pinfunction "M1_M1") (pintype "passive"))
      (node (ref "J16") (pin "M2") (pinfunction "M2_M2") (pintype "passive"))
      (node (ref "J17") (pin "4") (pinfunction "4_4") (pintype "passive"))
      (node (ref "J17") (pin "5") (pinfunction "5_5") (pintype "passive"))
      (node (ref "J17") (pin "M1") (pinfunction "M1_M1") (pintype "passive"))
      (node (ref "J17") (pin "M2") (pinfunction "M2_M2") (pintype "passive"))
      (node (ref "J18") (pin "4") (pinfunction "S_4") (pintype "passive"))
      (node (ref "J19") (pin "4") (pinfunction "S_4") (pintype "passive"))
      (node (ref "J20") (pin "8") (pinfunction "8_8") (pintype "passive"))
      (node (ref "J21") (pin "8") (pinfunction "8_8") (pintype "passive"))
      (node (ref "J28") (pin "6") (pinfunction "VSS_6") (pintype "power_in"))
      (node (ref "J28") (pin "P1") (pinfunction "SHIELD_P1") (pintype "passive"))
      (node (ref "J28") (pin "P2") (pinfunction "SHIELD_P2") (pintype "passive"))
      (node (ref "J28") (pin "P3") (pinfunction "SHIELD_P3") (pintype "passive"))
      (node (ref "J28") (pin "P4") (pinfunction "SHIELD_P4") (pintype "passive"))
      (node (ref "J28") (pin "SWB") (pinfunction "B_SWB") (pintype "bidirectional"))
      (node (ref "J3") (pin "10") (pinfunction "10_10") (pintype "passive"))
      (node (ref "J3") (pin "11") (pinfunction "11_11") (pintype "passive"))
      (node (ref "J3") (pin "M1") (pinfunction "M1_M1") (pintype "passive"))
      (node (ref "J3") (pin "M2") (pinfunction "M2_M2") (pintype "passive"))
      (node (ref "J30") (pin "21") (pinfunction "21_21") (pintype "passive"))
      (node (ref "J30") (pin "22") (pinfunction "22_22") (pintype "passive"))
      (node (ref "J30") (pin "23") (pinfunction "23_23") (pintype "passive"))
      (node (ref "J30") (pin "24") (pinfunction "24_24") (pintype "passive"))
      (node (ref "J30") (pin "9") (pinfunction "9_9") (pintype "passive"))
      (node (ref "J31") (pin "11") (pinfunction "11_11") (pintype "passive"))
      (node (ref "J31") (pin "12") (pinfunction "12_12") (pintype "passive"))
      (node (ref "J31") (pin "21") (pinfunction "21_21") (pintype "passive"))
      (node (ref "J31") (pin "22") (pinfunction "22_22") (pintype "passive"))
      (node (ref "J31") (pin "23") (pinfunction "23_23") (pintype "passive"))
      (node (ref "J31") (pin "24") (pinfunction "24_24") (pintype "passive"))
      (node (ref "J31") (pin "5") (pinfunction "5_5") (pintype "passive"))
      (node (ref "J31") (pin "6") (pinfunction "6_6") (pintype "passive"))
      (node (ref "J32") (pin "21") (pinfunction "21_21") (pintype "passive"))
      (node (ref "J32") (pin "22") (pinfunction "22_22") (pintype "passive"))
      (node (ref "J32") (pin "23") (pinfunction "23_23") (pintype "passive"))
      (node (ref "J32") (pin "24") (pinfunction "24_24") (pintype "passive"))
      (node (ref "J33") (pin "21") (pinfunction "21_21") (pintype "passive"))
      (node (ref "J33") (pin "22") (pinfunction "22_22") (pintype "passive"))
      (node (ref "J33") (pin "23") (pinfunction "23_23") (pintype "passive"))
      (node (ref "J33") (pin "24") (pinfunction "24_24") (pintype "passive"))
      (node (ref "J4") (pin "1") (pinfunction "1_1") (pintype "passive"))
      (node (ref "J49") (pin "4") (pinfunction "S_4") (pintype "passive"))
      (node (ref "J5") (pin "4") (pinfunction "S_4") (pintype "passive"))
      (node (ref "J51") (pin "2") (pinfunction "S_2") (pintype "passive"))
      (node (ref "J52") (pin "2") (pinfunction "S_2") (pintype "passive"))
      (node (ref "J6") (pin "2") (pinfunction "S_2") (pintype "passive"))
      (node (ref "J8") (pin "2") (pinfunction "2_2") (pintype "passive"))
      (node (ref "LED10") (pin "C") (pinfunction "C_C") (pintype "passive"))
      (node (ref "LED13") (pin "C") (pinfunction "C_C") (pintype "passive"))
      (node (ref "LED14") (pin "C") (pinfunction "C_C") (pintype "passive"))
      (node (ref "LED15") (pin "C") (pinfunction "C_C") (pintype "passive"))
      (node (ref "LED6") (pin "C") (pinfunction "C_C") (pintype "passive"))
      (node (ref "Q1") (pin "2") (pinfunction "GND(emitter)_2") (pintype "passive"))
      (node (ref "Q2") (pin "2") (pinfunction "GND(emitter)_2") (pintype "passive"))
      (node (ref "Q3") (pin "2") (pinfunction "GND(emitter)_2") (pintype "passive"))
      (node (ref "Q4") (pin "2") (pinfunction "GND(emitter)_2") (pintype "passive"))
      (node (ref "Q5") (pin "2") (pinfunction "GND(emitter)_2") (pintype "passive"))
      (node (ref "Q6") (pin "2") (pinfunction "E_2") (pintype "passive"))
      (node (ref "Q7") (pin "2") (pinfunction "E_2") (pintype "passive"))
      (node (ref "Q8") (pin "2") (pinfunction "GND(emitter)_2") (pintype "passive"))
      (node (ref "Q9") (pin "2") (pinfunction "GND(emitter)_2") (pintype "passive"))
      (node (ref "R100") (pin "1") (pinfunction "1_1") (pintype "passive"))
      (node (ref "R102") (pin "2") (pinfunction "2_2") (pintype "passive"))
      (node (ref "R134") (pin "1") (pinfunction "1_1") (pintype "passive"))
      (node (ref "R140") (pin "1") (pinfunction "1_1") (pintype "passive"))
      (node (ref "R142") (pin "1") (pinfunction "1_1") (pintype "passive"))
      (node (ref "R143") (pin "2") (pinfunction "2_2") (pintype "passive"))
      (node (ref "R144") (pin "2") (pinfunction "2_2") (pintype "passive"))
      (node (ref "R148") (pin "2") (pinfunction "2_2") (pintype "passive"))
      (node (ref "R149") (pin "2") (pinfunction "2_2") (pintype "passive"))
      (node (ref "R150") (pin "2") (pinfunction "2_2") (pintype "passive"))
      (node (ref "R151") (pin "2") (pinfunction "2_2") (pintype "passive"))
      (node (ref "R152") (pin "2") (pinfunction "2_2") (pintype "passive"))
      (node (ref "R153") (pin "2") (pinfunction "2_2") (pintype "passive"))
      (node (ref "R154") (pin "2") (pinfunction "2_2") (pintype "passive"))
      (node (ref "R161") (pin "2") (pinfunction "2_2") (pintype "passive"))
      (node (ref "R162") (pin "1") (pinfunction "1_1") (pintype "passive"))
      (node (ref "R38") (pin "1") (pinfunction "1_1") (pintype "passive"))
      (node (ref "R63") (pin "2") (pinfunction "2_2") (pintype "passive"))
      (node (ref "R64") (pin "2") (pinfunction "2_2") (pintype "passive"))
      (node (ref "R81") (pin "2") (pinfunction "2_2") (pintype "passive"))
      (node (ref "R82") (pin "2") (pinfunction "2_2") (pintype "passive"))
      (node (ref "R85") (pin "2") (pinfunction "2_2") (pintype "passive"))
      (node (ref "R88") (pin "2") (pinfunction "2_2") (pintype "passive"))
      (node (ref "U1") (pin "11") (pinfunction "E_11") (pintype "passive"))
      (node (ref "U1") (pin "13") (pinfunction "E_13") (pintype "passive"))
      (node (ref "U1") (pin "15") (pinfunction "E_15") (pintype "passive"))
      (node (ref "U1") (pin "9") (pinfunction "E_9") (pintype "passive"))
      (node (ref "U2") (pin "2") (pinfunction "GND_2") (pintype "power_in"))
      (node (ref "U27") (pin "2") (pinfunction "GND_2") (pintype "power_in"))
      (node (ref "U33") (pin "2") (pinfunction "GND_2") (pintype "power_in"))
      (node (ref "U7") (pin "4") (pinfunction "GND_4") (pintype "power_in"))
      (node (ref "U8") (pin "10") (pinfunction "GND_10") (pintype "power_in"))
    )
    (net (code "178") (name "Net-(D1-A)") (class "Default")
      (node (ref "D1") (pin "2") (pinfunction "A_2") (pintype "passive"))
      (node (ref "J2") (pin "1") (pinfunction "1_1") (pintype "passive"))
    )
    (net (code "179") (name "Net-(D15-Pad3)") (class "Default")
      (node (ref "D15") (pin "3") (pinfunction "3_3") (pintype "passive"))
      (node (ref "R57") (pin "1") (pinfunction "1_1") (pintype "passive"))
      (node (ref "R58") (pin "2") (pinfunction "2_2") (pintype "passive"))
      (node (ref "R63") (pin "1") (pinfunction "1_1") (pintype "passive"))
    )
    (net (code "180") (name "Net-(D16-Pad3)") (class "Default")
      (node (ref "D16") (pin "3") (pinfunction "3_3") (pintype "passive"))
      (node (ref "R144") (pin "1") (pinfunction "1_1") (pintype "passive"))
      (node (ref "R66") (pin "2") (pinfunction "2_2") (pintype "passive"))
      (node (ref "R74") (pin "1") (pinfunction "1_1") (pintype "passive"))
    )
    (net (code "181") (name "Net-(D17-Pad3)") (class "Default")
      (node (ref "D17") (pin "3") (pinfunction "3_3") (pintype "passive"))
      (node (ref "R143") (pin "1") (pinfunction "1_1") (pintype "passive"))
      (node (ref "R67") (pin "2") (pinfunction "2_2") (pintype "passive"))
      (node (ref "R75") (pin "1") (pinfunction "1_1") (pintype "passive"))
    )
    (net (code "182") (name "Net-(D18-Pad3)") (class "Default")
      (node (ref "D18") (pin "3") (pinfunction "3_3") (pintype "passive"))
      (node (ref "R102") (pin "1") (pinfunction "1_1") (pintype "passive"))
      (node (ref "R68") (pin "2") (pinfunction "2_2") (pintype "passive"))
      (node (ref "R76") (pin "1") (pinfunction "1_1") (pintype "passive"))
    )
    (net (code "183") (name "Net-(D19-Pad3)") (class "Default")
      (node (ref "D19") (pin "3") (pinfunction "3_3") (pintype "passive"))
      (node (ref "R69") (pin "2") (pinfunction "2_2") (pintype "passive"))
      (node (ref "R77") (pin "1") (pinfunction "1_1") (pintype "passive"))
      (node (ref "R88") (pin "1") (pinfunction "1_1") (pintype "passive"))
    )
    (net (code "184") (name "Net-(D20-Pad3)") (class "Default")
      (node (ref "D20") (pin "3") (pinfunction "3_3") (pintype "passive"))
      (node (ref "R70") (pin "2") (pinfunction "2_2") (pintype "passive"))
      (node (ref "R78") (pin "1") (pinfunction "1_1") (pintype "passive"))
      (node (ref "R85") (pin "1") (pinfunction "1_1") (pintype "passive"))
    )
    (net (code "185") (name "Net-(D21-Pad3)") (class "Default")
      (node (ref "D21") (pin "3") (pinfunction "3_3") (pintype "passive"))
      (node (ref "R71") (pin "2") (pinfunction "2_2") (pintype "passive"))
      (node (ref "R79") (pin "1") (pinfunction "1_1") (pintype "passive"))
      (node (ref "R82") (pin "1") (pinfunction "1_1") (pintype "passive"))
    )
    (net (code "186") (name "Net-(D22-Pad3)") (class "Default")
      (node (ref "D22") (pin "3") (pinfunction "3_3") (pintype "passive"))
      (node (ref "R72") (pin "2") (pinfunction "2_2") (pintype "passive"))
      (node (ref "R80") (pin "1") (pinfunction "1_1") (pintype "passive"))
      (node (ref "R81") (pin "1") (pinfunction "1_1") (pintype "passive"))
    )
    (net (code "187") (name "Net-(D31-Pad3)") (class "Default")
      (node (ref "D31") (pin "3") (pinfunction "3_3") (pintype "passive"))
      (node (ref "R163") (pin "2") (pinfunction "2_2") (pintype "passive"))
      (node (ref "R164") (pin "2") (pinfunction "2_2") (pintype "passive"))
    )
    (net (code "188") (name "Net-(D33-Pad3)") (class "Default")
      (node (ref "D33") (pin "3") (pinfunction "3_3") (pintype "passive"))
      (node (ref "R165") (pin "2") (pinfunction "2_2") (pintype "passive"))
      (node (ref "R166") (pin "2") (pinfunction "2_2") (pintype "passive"))
    )
    (net (code "189") (name "Net-(D35-Pad3)") (class "Default")
      (node (ref "D35") (pin "3") (pinfunction "3_3") (pintype "passive"))
      (node (ref "R167") (pin "2") (pinfunction "2_2") (pintype "passive"))
      (node (ref "R168") (pin "2") (pinfunction "2_2") (pintype "passive"))
    )
    (net (code "190") (name "Net-(D37-Pad3)") (class "Default")
      (node (ref "D37") (pin "3") (pinfunction "3_3") (pintype "passive"))
      (node (ref "R169") (pin "2") (pinfunction "2_2") (pintype "passive"))
      (node (ref "R170") (pin "2") (pinfunction "2_2") (pintype "passive"))
    )
    (net (code "191") (name "Net-(J18B-S)") (class "Default")
      (node (ref "D5") (pin "3") (pinfunction "3_3") (pintype "passive"))
      (node (ref "J18") (pin "2") (pinfunction "S_2") (pintype "passive"))
      (node (ref "R157") (pin "1") (pinfunction "1_1") (pintype "passive"))
      (node (ref "R50") (pin "2") (pinfunction "2_2") (pintype "passive"))
    )
    (net (code "192") (name "Net-(J18C-S)") (class "Default")
      (node (ref "D6") (pin "3") (pinfunction "3_3") (pintype "passive"))
      (node (ref "J18") (pin "3") (pinfunction "S_3") (pintype "passive"))
      (node (ref "R158") (pin "2") (pinfunction "2_2") (pintype "passive"))
      (node (ref "R51") (pin "2") (pinfunction "2_2") (pintype "passive"))
    )
    (net (code "193") (name "Net-(J19B-S)") (class "Default")
      (node (ref "D4") (pin "3") (pinfunction "3_3") (pintype "passive"))
      (node (ref "J19") (pin "2") (pinfunction "S_2") (pintype "passive"))
      (node (ref "R161") (pin "1") (pinfunction "1_1") (pintype "passive"))
      (node (ref "R49") (pin "2") (pinfunction "2_2") (pintype "passive"))
    )
    (net (code "194") (name "Net-(J19C-S)") (class "Default")
      (node (ref "D3") (pin "3") (pinfunction "3_3") (pintype "passive"))
      (node (ref "J19") (pin "3") (pinfunction "S_3") (pintype "passive"))
      (node (ref "R162") (pin "2") (pinfunction "2_2") (pintype "passive"))
      (node (ref "R48") (pin "2") (pinfunction "2_2") (pintype "passive"))
    )
    (net (code "195") (name "Net-(J47B-S)") (class "Default")
      (node (ref "J47") (pin "2") (pinfunction "S_2") (pintype "passive"))
      (node (ref "Q7") (pin "3") (pinfunction "C_3") (pintype "passive"))
    )
    (net (code "196") (name "Net-(J48B-S)") (class "Default")
      (node (ref "J48") (pin "2") (pinfunction "S_2") (pintype "passive"))
      (node (ref "Q6") (pin "3") (pinfunction "C_3") (pintype "passive"))
    )
    (net (code "197") (name "Net-(LED1-PadA)") (class "Default")
      (node (ref "LED1") (pin "A") (pinfunction "A_A") (pintype "passive"))
      (node (ref "R5") (pin "1") (pinfunction "1_1") (pintype "passive"))
    )
    (net (code "198") (name "Net-(LED2-PadA)") (class "Default")
      (node (ref "LED2") (pin "A") (pinfunction "A_A") (pintype "passive"))
      (node (ref "R6") (pin "1") (pinfunction "1_1") (pintype "passive"))
    )
    (net (code "199") (name "Net-(LED3-PadA)") (class "Default")
      (node (ref "LED3") (pin "A") (pinfunction "A_A") (pintype "passive"))
      (node (ref "R8") (pin "1") (pinfunction "1_1") (pintype "passive"))
    )
    (net (code "200") (name "Net-(LED4-PadA)") (class "Default")
      (node (ref "LED4") (pin "A") (pinfunction "A_A") (pintype "passive"))
      (node (ref "R10") (pin "1") (pinfunction "1_1") (pintype "passive"))
    )
    (net (code "201") (name "Net-(LED6-PadA)") (class "Default")
      (node (ref "LED6") (pin "A") (pinfunction "A_A") (pintype "passive"))
      (node (ref "R9") (pin "1") (pinfunction "1_1") (pintype "passive"))
    )
    (net (code "202") (name "Net-(LED10-PadA)") (class "Default")
      (node (ref "LED10") (pin "A") (pinfunction "A_A") (pintype "passive"))
      (node (ref "R13") (pin "1") (pinfunction "1_1") (pintype "passive"))
    )
    (net (code "203") (name "Net-(LED13-PadA)") (class "Default")
      (node (ref "LED13") (pin "A") (pinfunction "A_A") (pintype "passive"))
      (node (ref "R28") (pin "2") (pinfunction "2_2") (pintype "passive"))
    )
    (net (code "204") (name "Net-(LED14-PadA)") (class "Default")
      (node (ref "LED14") (pin "A") (pinfunction "A_A") (pintype "passive"))
      (node (ref "R30") (pin "2") (pinfunction "2_2") (pintype "passive"))
    )
    (net (code "205") (name "Net-(LED15-PadA)") (class "Default")
      (node (ref "LED15") (pin "A") (pinfunction "A_A") (pintype "passive"))
      (node (ref "R83") (pin "2") (pinfunction "2_2") (pintype "passive"))
    )
    (net (code "206") (name "Net-(Q2-output(collector))") (class "Default")
      (node (ref "LED1") (pin "C") (pinfunction "C_C") (pintype "passive"))
      (node (ref "Q2") (pin "3") (pinfunction "output(collector)_3") (pintype "passive"))
    )
    (net (code "207") (name "Net-(Q3-output(collector))") (class "Default")
      (node (ref "LED2") (pin "C") (pinfunction "C_C") (pintype "passive"))
      (node (ref "Q3") (pin "3") (pinfunction "output(collector)_3") (pintype "passive"))
    )
    (net (code "208") (name "Net-(Q4-output(collector))") (class "Default")
      (node (ref "LED3") (pin "C") (pinfunction "C_C") (pintype "passive"))
      (node (ref "Q4") (pin "3") (pinfunction "output(collector)_3") (pintype "passive"))
    )
    (net (code "209") (name "Net-(Q5-output(collector))") (class "Default")
      (node (ref "LED4") (pin "C") (pinfunction "C_C") (pintype "passive"))
      (node (ref "Q5") (pin "3") (pinfunction "output(collector)_3") (pintype "passive"))
    )
    (net (code "210") (name "Net-(Q6-B)") (class "Default")
      (node (ref "Q6") (pin "1") (pinfunction "B_1") (pintype "passive"))
      (node (ref "R98") (pin "2") (pinfunction "2_2") (pintype "passive"))
    )
    (net (code "211") (name "Net-(Q7-B)") (class "Default")
      (node (ref "C190") (pin "2") (pinfunction "2_2") (pintype "passive"))
      (node (ref "Q7") (pin "1") (pinfunction "B_1") (pintype "passive"))
      (node (ref "R44") (pin "1") (pinfunction "1_1") (pintype "passive"))
    )
    (net (code "212") (name "Net-(U1A-1_Cathode)") (class "Default")
      (node (ref "R3") (pin "1") (pinfunction "1_1") (pintype "passive"))
      (node (ref "U1") (pin "2") (pinfunction "1_Cathode_2") (pintype "passive"))
    )
    (net (code "213") (name "Net-(U1B-2_Anode)") (class "Default")
      (node (ref "R11") (pin "1") (pinfunction "1_1") (pintype "passive"))
      (node (ref "U1") (pin "3") (pinfunction "2_Anode_3") (pintype "passive"))
    )
    (net (code "214") (name "Net-(U1C-3_Anode)") (class "Default")
      (node (ref "R35") (pin "1") (pinfunction "1_1") (pintype "passive"))
      (node (ref "U1") (pin "5") (pinfunction "3_Anode_5") (pintype "passive"))
    )
    (net (code "215") (name "Net-(U1D-4_Anode)") (class "Default")
      (node (ref "R36") (pin "1") (pinfunction "1_1") (pintype "passive"))
      (node (ref "U1") (pin "7") (pinfunction "4_Anode_7") (pintype "passive"))
    )
    (net (code "216") (name "Net-(U27-CB)") (class "Default")
      (node (ref "C145") (pin "1") (pinfunction "1_1") (pintype "passive"))
      (node (ref "U27") (pin "1") (pinfunction "CB_1") (pintype "bidirectional"))
    )
    (net (code "217") (name "Net-(U27-EN)") (class "Default")
      (node (ref "R141") (pin "1") (pinfunction "1_1") (pintype "passive"))
      (node (ref "R142") (pin "2") (pinfunction "2_2") (pintype "passive"))
      (node (ref "U27") (pin "4") (pinfunction "EN_4") (pintype "bidirectional"))
    )
    (net (code "218") (name "Net-(U27-FB)") (class "Default")
      (node (ref "R100") (pin "2") (pinfunction "2_2") (pintype "passive"))
      (node (ref "R97") (pin "1") (pinfunction "1_1") (pintype "passive"))
      (node (ref "U27") (pin "3") (pinfunction "FB_3") (pintype "bidirectional"))
    )
    (net (code "219") (name "Net-(U27-SW)") (class "Default")
      (node (ref "C145") (pin "2") (pinfunction "2_2") (pintype "passive"))
      (node (ref "L12") (pin "2") (pinfunction "2_2") (pintype "passive"))
      (node (ref "U27") (pin "6") (pinfunction "SW_6") (pintype "bidirectional"))
    )
    (net (code "220") (name "Net-(U33-CB)") (class "Default")
      (node (ref "C136") (pin "1") (pinfunction "1_1") (pintype "passive"))
      (node (ref "U33") (pin "1") (pinfunction "CB_1") (pintype "bidirectional"))
    )
    (net (code "221") (name "Net-(U33-EN)") (class "Default")
      (node (ref "R139") (pin "1") (pinfunction "1_1") (pintype "passive"))
      (node (ref "R140") (pin "2") (pinfunction "2_2") (pintype "passive"))
      (node (ref "U33") (pin "4") (pinfunction "EN_4") (pintype "bidirectional"))
    )
    (net (code "222") (name "Net-(U33-FB)") (class "Default")
      (node (ref "R133") (pin "1") (pinfunction "1_1") (pintype "passive"))
      (node (ref "R134") (pin "2") (pinfunction "2_2") (pintype "passive"))
      (node (ref "U33") (pin "3") (pinfunction "FB_3") (pintype "bidirectional"))
    )
    (net (code "223") (name "Net-(U33-SW)") (class "Default")
      (node (ref "C136") (pin "2") (pinfunction "2_2") (pintype "passive"))
      (node (ref "L13") (pin "2") (pinfunction "2_2") (pintype "passive"))
      (node (ref "U33") (pin "6") (pinfunction "SW_6") (pintype "bidirectional"))
    )
    (net (code "224") (name "VDD_3.3V") (class "Default")
      (node (ref "C150") (pin "2") (pinfunction "2_2") (pintype "passive"))
      (node (ref "C155") (pin "2") (pinfunction "2_2") (pintype "passive"))
      (node (ref "C35") (pin "2") (pinfunction "2_2") (pintype "passive"))
      (node (ref "C78") (pin "2") (pinfunction "2_2") (pintype "passive"))
      (node (ref "C86") (pin "2") (pinfunction "2_2") (pintype "passive"))
      (node (ref "D15") (pin "2") (pinfunction "2_2") (pintype "passive"))
      (node (ref "D16") (pin "2") (pinfunction "2_2") (pintype "passive"))
      (node (ref "D17") (pin "2") (pinfunction "2_2") (pintype "passive"))
      (node (ref "D18") (pin "2") (pinfunction "2_2") (pintype "passive"))
      (node (ref "D19") (pin "2") (pinfunction "2_2") (pintype "passive"))
      (node (ref "D20") (pin "2") (pinfunction "2_2") (pintype "passive"))
      (node (ref "D21") (pin "2") (pinfunction "2_2") (pintype "passive"))
      (node (ref "D22") (pin "2") (pinfunction "2_2") (pintype "passive"))
      (node (ref "D3") (pin "2") (pinfunction "2_2") (pintype "passive"))
      (node (ref "D31") (pin "2") (pinfunction "2_2") (pintype "passive"))
      (node (ref "D33") (pin "2") (pinfunction "2_2") (pintype "passive"))
      (node (ref "D35") (pin "2") (pinfunction "2_2") (pintype "passive"))
      (node (ref "D37") (pin "2") (pinfunction "2_2") (pintype "passive"))
      (node (ref "D4") (pin "2") (pinfunction "2_2") (pintype "passive"))
      (node (ref "D46") (pin "1") (pinfunction "1_1") (pintype "passive"))
      (node (ref "D48") (pin "1") (pinfunction "1_1") (pintype "passive"))
      (node (ref "D5") (pin "2") (pinfunction "2_2") (pintype "passive"))
      (node (ref "D50") (pin "1") (pinfunction "1_1") (pintype "passive"))
      (node (ref "D6") (pin "2") (pinfunction "2_2") (pintype "passive"))
      (node (ref "J15") (pin "14") (pinfunction "14_14") (pintype "passive"))
      (node (ref "J15") (pin "15") (pinfunction "15_15") (pintype "passive"))
      (node (ref "J16") (pin "14") (pinfunction "14_14") (pintype "passive"))
      (node (ref "J16") (pin "15") (pinfunction "15_15") (pintype "passive"))
      (node (ref "J17") (pin "14") (pinfunction "14_14") (pintype "passive"))
      (node (ref "J17") (pin "15") (pinfunction "15_15") (pintype "passive"))
      (node (ref "J28") (pin "4") (pinfunction "VDD_4") (pintype "power_in"))
      (node (ref "J3") (pin "14") (pinfunction "14_14") (pintype "passive"))
      (node (ref "J3") (pin "15") (pinfunction "15_15") (pintype "passive"))
      (node (ref "J31") (pin "10") (pinfunction "10_10") (pintype "passive"))
      (node (ref "J31") (pin "7") (pinfunction "7_7") (pintype "passive"))
      (node (ref "J31") (pin "8") (pinfunction "8_8") (pintype "passive"))
      (node (ref "J31") (pin "9") (pinfunction "9_9") (pintype "passive"))
      (node (ref "J49") (pin "1") (pinfunction "S_1") (pintype "passive"))
      (node (ref "J5") (pin "1") (pinfunction "S_1") (pintype "passive"))
      (node (ref "J51") (pin "1") (pinfunction "S_1") (pintype "passive"))
      (node (ref "L12") (pin "1") (pinfunction "1_1") (pintype "passive"))
      (node (ref "L17") (pin "2") (pinfunction "2_2") (pintype "passive"))
      (node (ref "L4") (pin "2") (pinfunction "2_2") (pintype "passive"))
      (node (ref "L5") (pin "1") (pinfunction "1_1") (pintype "passive"))
      (node (ref "R1") (pin "2") (pinfunction "2_2") (pintype "passive"))
      (node (ref "R10") (pin "2") (pinfunction "2_2") (pintype "passive"))
      (node (ref "R101") (pin "2") (pinfunction "2_2") (pintype "passive"))
      (node (ref "R128") (pin "2") (pinfunction "2_2") (pintype "passive"))
      (node (ref "R157") (pin "2") (pinfunction "2_2") (pintype "passive"))
      (node (ref "R158") (pin "1") (pinfunction "1_1") (pintype "passive"))
      (node (ref "R2") (pin "2") (pinfunction "2_2") (pintype "passive"))
      (node (ref "R25") (pin "2") (pinfunction "2_2") (pintype "passive"))
      (node (ref "R26") (pin "2") (pinfunction "2_2") (pintype "passive"))
      (node (ref "R29") (pin "2") (pinfunction "2_2") (pintype "passive"))
      (node (ref "R34") (pin "2") (pinfunction "2_2") (pintype "passive"))
      (node (ref "R5") (pin "2") (pinfunction "2_2") (pintype "passive"))
      (node (ref "R6") (pin "2") (pinfunction "2_2") (pintype "passive"))
      (node (ref "R60") (pin "1") (pinfunction "1_1") (pintype "passive"))
      (node (ref "R61") (pin "1") (pinfunction "1_1") (pintype "passive"))
      (node (ref "R62") (pin "1") (pinfunction "1_1") (pintype "passive"))
      (node (ref "R65") (pin "1") (pinfunction "1_1") (pintype "passive"))
      (node (ref "R73") (pin "1") (pinfunction "1_1") (pintype "passive"))
      (node (ref "R8") (pin "2") (pinfunction "2_2") (pintype "passive"))
      (node (ref "R86") (pin "1") (pinfunction "1_1") (pintype "passive"))
      (node (ref "R9") (pin "2") (pinfunction "2_2") (pintype "passive"))
      (node (ref "R97") (pin "2") (pinfunction "2_2") (pintype "passive"))
      (node (ref "U7") (pin "8") (pinfunction "VCC_8") (pintype "power_in"))
    )
    (net (code "225") (name "VDD_5V") (class "Default")
      (node (ref "C113") (pin "2") (pinfunction "2_2") (pintype "passive"))
      (node (ref "C33") (pin "2") (pinfunction "2_2") (pintype "passive"))
      (node (ref "C61") (pin "2") (pinfunction "2_2") (pintype "passive"))
      (node (ref "C63") (pin "2") (pinfunction "2_2") (pintype "passive"))
      (node (ref "J18") (pin "1") (pinfunction "S_1") (pintype "passive"))
      (node (ref "J19") (pin "1") (pinfunction "S_1") (pintype "passive"))
      (node (ref "J3") (pin "12") (pinfunction "12_12") (pintype "passive"))
      (node (ref "J3") (pin "13") (pinfunction "13_13") (pintype "passive"))
      (node (ref "J47") (pin "1") (pinfunction "S_1") (pintype "passive"))
      (node (ref "J48") (pin "1") (pinfunction "S_1") (pintype "passive"))
      (node (ref "J52") (pin "1") (pinfunction "S_1") (pintype "passive"))
      (node (ref "J8") (pin "1") (pinfunction "1_1") (pintype "passive"))
      (node (ref "J8") (pin "3") (pinfunction "3_3") (pintype "passive"))
      (node (ref "J8") (pin "5") (pinfunction "5_5") (pintype "passive"))
      (node (ref "J8") (pin "7") (pinfunction "7_7") (pintype "passive"))
      (node (ref "L13") (pin "1") (pinfunction "1_1") (pintype "passive"))
      (node (ref "L6") (pin "2") (pinfunction "2_2") (pintype "passive"))
      (node (ref "L7") (pin "1") (pinfunction "1_1") (pintype "passive"))
      (node (ref "R13") (pin "2") (pinfunction "2_2") (pintype "passive"))
      (node (ref "R133") (pin "2") (pinfunction "2_2") (pintype "passive"))
    )
    (net (code "226") (name "VDD_SYS") (class "Default")
      (node (ref "C146") (pin "1") (pinfunction "1_1") (pintype "passive"))
      (node (ref "C147") (pin "1") (pinfunction "1_1") (pintype "passive"))
      (node (ref "C148") (pin "1") (pinfunction "1_1") (pintype "passive"))
      (node (ref "C149") (pin "1") (pinfunction "1_1") (pintype "passive"))
      (node (ref "D1") (pin "1") (pinfunction "C_1") (pintype "passive"))
      (node (ref "D2") (pin "1") (pinfunction "1_1") (pintype "passive"))
      (node (ref "J6") (pin "1") (pinfunction "S_1") (pintype "passive"))
      (node (ref "L2") (pin "2") (pinfunction "2_2") (pintype "passive"))
      (node (ref "L3") (pin "1") (pinfunction "1_1") (pintype "passive"))
      (node (ref "R11") (pin "2") (pinfunction "2_2") (pintype "passive"))
      (node (ref "R139") (pin "2") (pinfunction "2_2") (pintype "passive"))
      (node (ref "R141") (pin "2") (pinfunction "2_2") (pintype "passive"))
      (node (ref "R3") (pin "2") (pinfunction "2_2") (pintype "passive"))
      (node (ref "R35") (pin "2") (pinfunction "2_2") (pintype "passive"))
      (node (ref "R36") (pin "2") (pinfunction "2_2") (pintype "passive"))
      (node (ref "U27") (pin "5") (pinfunction "VIN_5") (pintype "input"))
      (node (ref "U33") (pin "5") (pinfunction "VIN_5") (pintype "input"))
    )
    (net (code "227") (name "unconnected-(D11-common_anode-Pad2)") (class "Default")
      (node (ref "D11") (pin "2") (pinfunction "common_anode_2") (pintype "passive"))
    )
    (net (code "228") (name "unconnected-(D14-common_anode-Pad2)") (class "Default")
      (node (ref "D14") (pin "2") (pinfunction "common_anode_2") (pintype "passive"))
    )
    (net (code "229") (name "unconnected-(D44-common_anode-Pad2)") (class "Default")
      (node (ref "D44") (pin "2") (pinfunction "common_anode_2") (pintype "passive"))
    )
    (net (code "230") (name "unconnected-(J1-ID-Pad4)") (class "Default")
      (node (ref "J1") (pin "4") (pinfunction "ID_4") (pintype "passive"))
    )
    (net (code "231") (name "unconnected-(U8-AD2{slash}DIO2{slash}SPI_CLK-Pad18)") (class "Default")
      (node (ref "U8") (pin "18") (pinfunction "AD2/DIO2/SPI_CLK_18") (pintype "bidirectional"))
    )
    (net (code "232") (name "unconnected-(U8-AD3{slash}DIO3{slash}SPI_!SSEL!-Pad17)") (class "Default")
      (node (ref "U8") (pin "17") (pinfunction "AD3/DIO3/SPI_!SSEL!_17") (pintype "bidirectional"))
    )
    (net (code "233") (name "unconnected-(U8-DIO4{slash}SPI_MOSI-Pad11)") (class "Default")
      (node (ref "U8") (pin "11") (pinfunction "DIO4/SPI_MOSI_11") (pintype "bidirectional"))
    )
    (net (code "234") (name "unconnected-(U8-DIO12{slash}SPI_MISO-Pad4)") (class "Default")
      (node (ref "U8") (pin "4") (pinfunction "DIO12/SPI_MISO_4") (pintype "bidirectional"))
    )
    (net (code "235") (name "unconnected-(U8-ON{slash}!SLEEP!{slash}DIO9-Pad13)") (class "Default")
      (node (ref "U8") (pin "13") (pinfunction "ON/!SLEEP!/DIO9_13") (pintype "bidirectional"))
    )
    (net (code "236") (name "unconnected-(U8-PWM1{slash}DIO11{slash}I2C_SDA-Pad7)") (class "Default")
      (node (ref "U8") (pin "7") (pinfunction "PWM1/DIO11/I2C_SDA_7") (pintype "bidirectional"))
    )
  )
)
